# LEDSubMatrixHighDensity.net
KiCad netlist of a schematic drawn in EAGLE
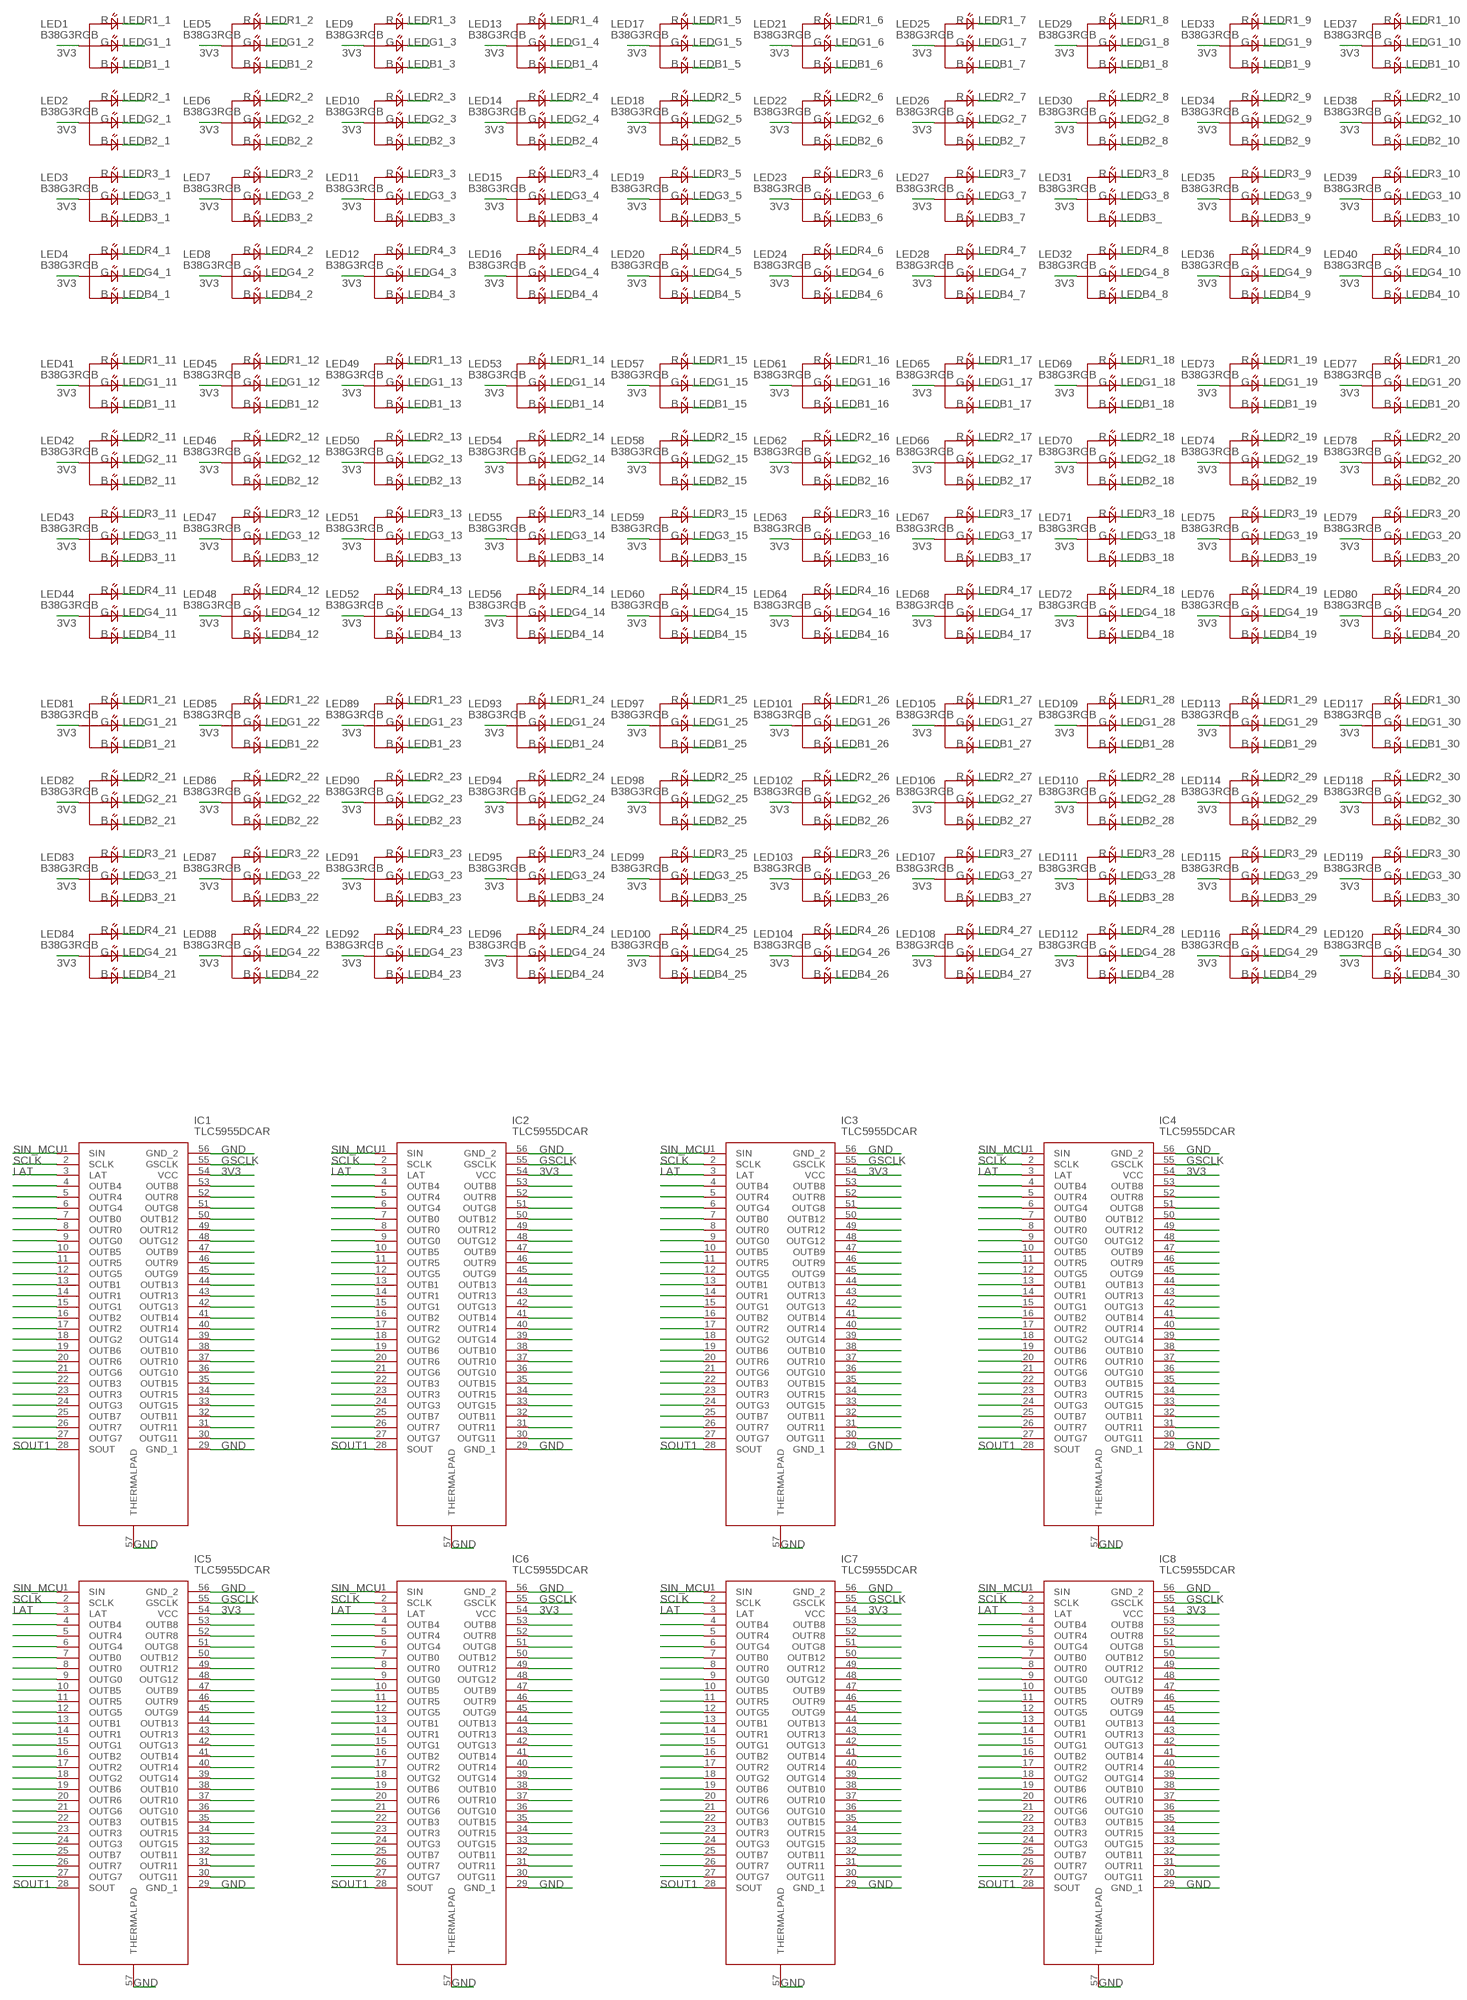
[diagram p0: schematic, sheet 1]

(export (version "E")
  (design (tool "Eeschema 10.0.6"))
  (components
    (comp (ref "IC1")
      (value "TLC5955DCAR")
      (footprint "eagle-import:SOP50P810X120-57N")
      (fields (field (name "MOUSER_PART_NUMBER") "595-TLC5955DCAR"))
      (libsource (lib "eagle-import") (part "TLC5955DCAR"))
    )
    (comp (ref "IC2")
      (value "TLC5955DCAR")
      (footprint "eagle-import:SOP50P810X120-57N")
      (fields (field (name "MOUSER_PART_NUMBER") "595-TLC5955DCAR"))
      (libsource (lib "eagle-import") (part "TLC5955DCAR"))
    )
    (comp (ref "IC3")
      (value "TLC5955DCAR")
      (footprint "eagle-import:SOP50P810X120-57N")
      (fields (field (name "MOUSER_PART_NUMBER") "595-TLC5955DCAR"))
      (libsource (lib "eagle-import") (part "TLC5955DCAR"))
    )
    (comp (ref "IC4")
      (value "TLC5955DCAR")
      (footprint "eagle-import:SOP50P810X120-57N")
      (fields (field (name "MOUSER_PART_NUMBER") "595-TLC5955DCAR"))
      (libsource (lib "eagle-import") (part "TLC5955DCAR"))
    )
    (comp (ref "IC5")
      (value "TLC5955DCAR")
      (footprint "eagle-import:SOP50P810X120-57N")
      (fields (field (name "MOUSER_PART_NUMBER") "595-TLC5955DCAR"))
      (libsource (lib "eagle-import") (part "TLC5955DCAR"))
    )
    (comp (ref "IC6")
      (value "TLC5955DCAR")
      (footprint "eagle-import:SOP50P810X120-57N")
      (fields (field (name "MOUSER_PART_NUMBER") "595-TLC5955DCAR"))
      (libsource (lib "eagle-import") (part "TLC5955DCAR"))
    )
    (comp (ref "IC7")
      (value "TLC5955DCAR")
      (footprint "eagle-import:SOP50P810X120-57N")
      (fields (field (name "MOUSER_PART_NUMBER") "595-TLC5955DCAR"))
      (libsource (lib "eagle-import") (part "TLC5955DCAR"))
    )
    (comp (ref "IC8")
      (value "TLC5955DCAR")
      (footprint "eagle-import:SOP50P810X120-57N")
      (fields (field (name "MOUSER_PART_NUMBER") "595-TLC5955DCAR"))
      (libsource (lib "eagle-import") (part "TLC5955DCAR"))
    )
    (comp (ref "LED1")
      (value "B38G3RGB")
      (footprint "eagle-import:B38G3RGB")
      (fields
        (field (name "ARROW_PART_NUMBER") "SML-LX0606IGC-TR")
        (field (name "MOUSER_PART_NUMBER") "696-SML-0606IGCTR")
      )
      (libsource (lib "eagle-import") (part "B38G3RGB"))
    )
    (comp (ref "LED2")
      (value "B38G3RGB")
      (footprint "eagle-import:B38G3RGB")
      (fields
        (field (name "ARROW_PART_NUMBER") "SML-LX0606IGC-TR")
        (field (name "MOUSER_PART_NUMBER") "696-SML-0606IGCTR")
      )
      (libsource (lib "eagle-import") (part "B38G3RGB"))
    )
    (comp (ref "LED3")
      (value "B38G3RGB")
      (footprint "eagle-import:B38G3RGB")
      (fields
        (field (name "ARROW_PART_NUMBER") "SML-LX0606IGC-TR")
        (field (name "MOUSER_PART_NUMBER") "696-SML-0606IGCTR")
      )
      (libsource (lib "eagle-import") (part "B38G3RGB"))
    )
    (comp (ref "LED4")
      (value "B38G3RGB")
      (footprint "eagle-import:B38G3RGB")
      (fields
        (field (name "ARROW_PART_NUMBER") "SML-LX0606IGC-TR")
        (field (name "MOUSER_PART_NUMBER") "696-SML-0606IGCTR")
      )
      (libsource (lib "eagle-import") (part "B38G3RGB"))
    )
    (comp (ref "LED5")
      (value "B38G3RGB")
      (footprint "eagle-import:B38G3RGB")
      (fields
        (field (name "ARROW_PART_NUMBER") "SML-LX0606IGC-TR")
        (field (name "MOUSER_PART_NUMBER") "696-SML-0606IGCTR")
      )
      (libsource (lib "eagle-import") (part "B38G3RGB"))
    )
    (comp (ref "LED6")
      (value "B38G3RGB")
      (footprint "eagle-import:B38G3RGB")
      (fields
        (field (name "ARROW_PART_NUMBER") "SML-LX0606IGC-TR")
        (field (name "MOUSER_PART_NUMBER") "696-SML-0606IGCTR")
      )
      (libsource (lib "eagle-import") (part "B38G3RGB"))
    )
    (comp (ref "LED7")
      (value "B38G3RGB")
      (footprint "eagle-import:B38G3RGB")
      (fields
        (field (name "ARROW_PART_NUMBER") "SML-LX0606IGC-TR")
        (field (name "MOUSER_PART_NUMBER") "696-SML-0606IGCTR")
      )
      (libsource (lib "eagle-import") (part "B38G3RGB"))
    )
    (comp (ref "LED8")
      (value "B38G3RGB")
      (footprint "eagle-import:B38G3RGB")
      (fields
        (field (name "ARROW_PART_NUMBER") "SML-LX0606IGC-TR")
        (field (name "MOUSER_PART_NUMBER") "696-SML-0606IGCTR")
      )
      (libsource (lib "eagle-import") (part "B38G3RGB"))
    )
    (comp (ref "LED9")
      (value "B38G3RGB")
      (footprint "eagle-import:B38G3RGB")
      (fields
        (field (name "ARROW_PART_NUMBER") "SML-LX0606IGC-TR")
        (field (name "MOUSER_PART_NUMBER") "696-SML-0606IGCTR")
      )
      (libsource (lib "eagle-import") (part "B38G3RGB"))
    )
    (comp (ref "LED10")
      (value "B38G3RGB")
      (footprint "eagle-import:B38G3RGB")
      (fields
        (field (name "ARROW_PART_NUMBER") "SML-LX0606IGC-TR")
        (field (name "MOUSER_PART_NUMBER") "696-SML-0606IGCTR")
      )
      (libsource (lib "eagle-import") (part "B38G3RGB"))
    )
    (comp (ref "LED11")
      (value "B38G3RGB")
      (footprint "eagle-import:B38G3RGB")
      (fields
        (field (name "ARROW_PART_NUMBER") "SML-LX0606IGC-TR")
        (field (name "MOUSER_PART_NUMBER") "696-SML-0606IGCTR")
      )
      (libsource (lib "eagle-import") (part "B38G3RGB"))
    )
    (comp (ref "LED12")
      (value "B38G3RGB")
      (footprint "eagle-import:B38G3RGB")
      (fields
        (field (name "ARROW_PART_NUMBER") "SML-LX0606IGC-TR")
        (field (name "MOUSER_PART_NUMBER") "696-SML-0606IGCTR")
      )
      (libsource (lib "eagle-import") (part "B38G3RGB"))
    )
    (comp (ref "LED13")
      (value "B38G3RGB")
      (footprint "eagle-import:B38G3RGB")
      (fields
        (field (name "ARROW_PART_NUMBER") "SML-LX0606IGC-TR")
        (field (name "MOUSER_PART_NUMBER") "696-SML-0606IGCTR")
      )
      (libsource (lib "eagle-import") (part "B38G3RGB"))
    )
    (comp (ref "LED14")
      (value "B38G3RGB")
      (footprint "eagle-import:B38G3RGB")
      (fields
        (field (name "ARROW_PART_NUMBER") "SML-LX0606IGC-TR")
        (field (name "MOUSER_PART_NUMBER") "696-SML-0606IGCTR")
      )
      (libsource (lib "eagle-import") (part "B38G3RGB"))
    )
    (comp (ref "LED15")
      (value "B38G3RGB")
      (footprint "eagle-import:B38G3RGB")
      (fields
        (field (name "ARROW_PART_NUMBER") "SML-LX0606IGC-TR")
        (field (name "MOUSER_PART_NUMBER") "696-SML-0606IGCTR")
      )
      (libsource (lib "eagle-import") (part "B38G3RGB"))
    )
    (comp (ref "LED16")
      (value "B38G3RGB")
      (footprint "eagle-import:B38G3RGB")
      (fields
        (field (name "ARROW_PART_NUMBER") "SML-LX0606IGC-TR")
        (field (name "MOUSER_PART_NUMBER") "696-SML-0606IGCTR")
      )
      (libsource (lib "eagle-import") (part "B38G3RGB"))
    )
    (comp (ref "LED17")
      (value "B38G3RGB")
      (footprint "eagle-import:B38G3RGB")
      (fields
        (field (name "ARROW_PART_NUMBER") "SML-LX0606IGC-TR")
        (field (name "MOUSER_PART_NUMBER") "696-SML-0606IGCTR")
      )
      (libsource (lib "eagle-import") (part "B38G3RGB"))
    )
    (comp (ref "LED18")
      (value "B38G3RGB")
      (footprint "eagle-import:B38G3RGB")
      (fields
        (field (name "ARROW_PART_NUMBER") "SML-LX0606IGC-TR")
        (field (name "MOUSER_PART_NUMBER") "696-SML-0606IGCTR")
      )
      (libsource (lib "eagle-import") (part "B38G3RGB"))
    )
    (comp (ref "LED19")
      (value "B38G3RGB")
      (footprint "eagle-import:B38G3RGB")
      (fields
        (field (name "ARROW_PART_NUMBER") "SML-LX0606IGC-TR")
        (field (name "MOUSER_PART_NUMBER") "696-SML-0606IGCTR")
      )
      (libsource (lib "eagle-import") (part "B38G3RGB"))
    )
    (comp (ref "LED20")
      (value "B38G3RGB")
      (footprint "eagle-import:B38G3RGB")
      (fields
        (field (name "ARROW_PART_NUMBER") "SML-LX0606IGC-TR")
        (field (name "MOUSER_PART_NUMBER") "696-SML-0606IGCTR")
      )
      (libsource (lib "eagle-import") (part "B38G3RGB"))
    )
    (comp (ref "LED21")
      (value "B38G3RGB")
      (footprint "eagle-import:B38G3RGB")
      (fields
        (field (name "ARROW_PART_NUMBER") "SML-LX0606IGC-TR")
        (field (name "MOUSER_PART_NUMBER") "696-SML-0606IGCTR")
      )
      (libsource (lib "eagle-import") (part "B38G3RGB"))
    )
    (comp (ref "LED22")
      (value "B38G3RGB")
      (footprint "eagle-import:B38G3RGB")
      (fields
        (field (name "ARROW_PART_NUMBER") "SML-LX0606IGC-TR")
        (field (name "MOUSER_PART_NUMBER") "696-SML-0606IGCTR")
      )
      (libsource (lib "eagle-import") (part "B38G3RGB"))
    )
    (comp (ref "LED23")
      (value "B38G3RGB")
      (footprint "eagle-import:B38G3RGB")
      (fields
        (field (name "ARROW_PART_NUMBER") "SML-LX0606IGC-TR")
        (field (name "MOUSER_PART_NUMBER") "696-SML-0606IGCTR")
      )
      (libsource (lib "eagle-import") (part "B38G3RGB"))
    )
    (comp (ref "LED24")
      (value "B38G3RGB")
      (footprint "eagle-import:B38G3RGB")
      (fields
        (field (name "ARROW_PART_NUMBER") "SML-LX0606IGC-TR")
        (field (name "MOUSER_PART_NUMBER") "696-SML-0606IGCTR")
      )
      (libsource (lib "eagle-import") (part "B38G3RGB"))
    )
    (comp (ref "LED25")
      (value "B38G3RGB")
      (footprint "eagle-import:B38G3RGB")
      (fields
        (field (name "ARROW_PART_NUMBER") "SML-LX0606IGC-TR")
        (field (name "MOUSER_PART_NUMBER") "696-SML-0606IGCTR")
      )
      (libsource (lib "eagle-import") (part "B38G3RGB"))
    )
    (comp (ref "LED26")
      (value "B38G3RGB")
      (footprint "eagle-import:B38G3RGB")
      (fields
        (field (name "ARROW_PART_NUMBER") "SML-LX0606IGC-TR")
        (field (name "MOUSER_PART_NUMBER") "696-SML-0606IGCTR")
      )
      (libsource (lib "eagle-import") (part "B38G3RGB"))
    )
    (comp (ref "LED27")
      (value "B38G3RGB")
      (footprint "eagle-import:B38G3RGB")
      (fields
        (field (name "ARROW_PART_NUMBER") "SML-LX0606IGC-TR")
        (field (name "MOUSER_PART_NUMBER") "696-SML-0606IGCTR")
      )
      (libsource (lib "eagle-import") (part "B38G3RGB"))
    )
    (comp (ref "LED28")
      (value "B38G3RGB")
      (footprint "eagle-import:B38G3RGB")
      (fields
        (field (name "ARROW_PART_NUMBER") "SML-LX0606IGC-TR")
        (field (name "MOUSER_PART_NUMBER") "696-SML-0606IGCTR")
      )
      (libsource (lib "eagle-import") (part "B38G3RGB"))
    )
    (comp (ref "LED29")
      (value "B38G3RGB")
      (footprint "eagle-import:B38G3RGB")
      (fields
        (field (name "ARROW_PART_NUMBER") "SML-LX0606IGC-TR")
        (field (name "MOUSER_PART_NUMBER") "696-SML-0606IGCTR")
      )
      (libsource (lib "eagle-import") (part "B38G3RGB"))
    )
    (comp (ref "LED30")
      (value "B38G3RGB")
      (footprint "eagle-import:B38G3RGB")
      (fields
        (field (name "ARROW_PART_NUMBER") "SML-LX0606IGC-TR")
        (field (name "MOUSER_PART_NUMBER") "696-SML-0606IGCTR")
      )
      (libsource (lib "eagle-import") (part "B38G3RGB"))
    )
    (comp (ref "LED31")
      (value "B38G3RGB")
      (footprint "eagle-import:B38G3RGB")
      (fields
        (field (name "ARROW_PART_NUMBER") "SML-LX0606IGC-TR")
        (field (name "MOUSER_PART_NUMBER") "696-SML-0606IGCTR")
      )
      (libsource (lib "eagle-import") (part "B38G3RGB"))
    )
    (comp (ref "LED32")
      (value "B38G3RGB")
      (footprint "eagle-import:B38G3RGB")
      (fields
        (field (name "ARROW_PART_NUMBER") "SML-LX0606IGC-TR")
        (field (name "MOUSER_PART_NUMBER") "696-SML-0606IGCTR")
      )
      (libsource (lib "eagle-import") (part "B38G3RGB"))
    )
    (comp (ref "LED33")
      (value "B38G3RGB")
      (footprint "eagle-import:B38G3RGB")
      (fields
        (field (name "ARROW_PART_NUMBER") "SML-LX0606IGC-TR")
        (field (name "MOUSER_PART_NUMBER") "696-SML-0606IGCTR")
      )
      (libsource (lib "eagle-import") (part "B38G3RGB"))
    )
    (comp (ref "LED34")
      (value "B38G3RGB")
      (footprint "eagle-import:B38G3RGB")
      (fields
        (field (name "ARROW_PART_NUMBER") "SML-LX0606IGC-TR")
        (field (name "MOUSER_PART_NUMBER") "696-SML-0606IGCTR")
      )
      (libsource (lib "eagle-import") (part "B38G3RGB"))
    )
    (comp (ref "LED35")
      (value "B38G3RGB")
      (footprint "eagle-import:B38G3RGB")
      (fields
        (field (name "ARROW_PART_NUMBER") "SML-LX0606IGC-TR")
        (field (name "MOUSER_PART_NUMBER") "696-SML-0606IGCTR")
      )
      (libsource (lib "eagle-import") (part "B38G3RGB"))
    )
    (comp (ref "LED36")
      (value "B38G3RGB")
      (footprint "eagle-import:B38G3RGB")
      (fields
        (field (name "ARROW_PART_NUMBER") "SML-LX0606IGC-TR")
        (field (name "MOUSER_PART_NUMBER") "696-SML-0606IGCTR")
      )
      (libsource (lib "eagle-import") (part "B38G3RGB"))
    )
    (comp (ref "LED37")
      (value "B38G3RGB")
      (footprint "eagle-import:B38G3RGB")
      (fields
        (field (name "ARROW_PART_NUMBER") "SML-LX0606IGC-TR")
        (field (name "MOUSER_PART_NUMBER") "696-SML-0606IGCTR")
      )
      (libsource (lib "eagle-import") (part "B38G3RGB"))
    )
    (comp (ref "LED38")
      (value "B38G3RGB")
      (footprint "eagle-import:B38G3RGB")
      (fields
        (field (name "ARROW_PART_NUMBER") "SML-LX0606IGC-TR")
        (field (name "MOUSER_PART_NUMBER") "696-SML-0606IGCTR")
      )
      (libsource (lib "eagle-import") (part "B38G3RGB"))
    )
    (comp (ref "LED39")
      (value "B38G3RGB")
      (footprint "eagle-import:B38G3RGB")
      (fields
        (field (name "ARROW_PART_NUMBER") "SML-LX0606IGC-TR")
        (field (name "MOUSER_PART_NUMBER") "696-SML-0606IGCTR")
      )
      (libsource (lib "eagle-import") (part "B38G3RGB"))
    )
    (comp (ref "LED40")
      (value "B38G3RGB")
      (footprint "eagle-import:B38G3RGB")
      (fields
        (field (name "ARROW_PART_NUMBER") "SML-LX0606IGC-TR")
        (field (name "MOUSER_PART_NUMBER") "696-SML-0606IGCTR")
      )
      (libsource (lib "eagle-import") (part "B38G3RGB"))
    )
    (comp (ref "LED41")
      (value "B38G3RGB")
      (footprint "eagle-import:B38G3RGB")
      (fields
        (field (name "ARROW_PART_NUMBER") "SML-LX0606IGC-TR")
        (field (name "MOUSER_PART_NUMBER") "696-SML-0606IGCTR")
      )
      (libsource (lib "eagle-import") (part "B38G3RGB"))
    )
    (comp (ref "LED42")
      (value "B38G3RGB")
      (footprint "eagle-import:B38G3RGB")
      (fields
        (field (name "ARROW_PART_NUMBER") "SML-LX0606IGC-TR")
        (field (name "MOUSER_PART_NUMBER") "696-SML-0606IGCTR")
      )
      (libsource (lib "eagle-import") (part "B38G3RGB"))
    )
    (comp (ref "LED43")
      (value "B38G3RGB")
      (footprint "eagle-import:B38G3RGB")
      (fields
        (field (name "ARROW_PART_NUMBER") "SML-LX0606IGC-TR")
        (field (name "MOUSER_PART_NUMBER") "696-SML-0606IGCTR")
      )
      (libsource (lib "eagle-import") (part "B38G3RGB"))
    )
    (comp (ref "LED44")
      (value "B38G3RGB")
      (footprint "eagle-import:B38G3RGB")
      (fields
        (field (name "ARROW_PART_NUMBER") "SML-LX0606IGC-TR")
        (field (name "MOUSER_PART_NUMBER") "696-SML-0606IGCTR")
      )
      (libsource (lib "eagle-import") (part "B38G3RGB"))
    )
    (comp (ref "LED45")
      (value "B38G3RGB")
      (footprint "eagle-import:B38G3RGB")
      (fields
        (field (name "ARROW_PART_NUMBER") "SML-LX0606IGC-TR")
        (field (name "MOUSER_PART_NUMBER") "696-SML-0606IGCTR")
      )
      (libsource (lib "eagle-import") (part "B38G3RGB"))
    )
    (comp (ref "LED46")
      (value "B38G3RGB")
      (footprint "eagle-import:B38G3RGB")
      (fields
        (field (name "ARROW_PART_NUMBER") "SML-LX0606IGC-TR")
        (field (name "MOUSER_PART_NUMBER") "696-SML-0606IGCTR")
      )
      (libsource (lib "eagle-import") (part "B38G3RGB"))
    )
    (comp (ref "LED47")
      (value "B38G3RGB")
      (footprint "eagle-import:B38G3RGB")
      (fields
        (field (name "ARROW_PART_NUMBER") "SML-LX0606IGC-TR")
        (field (name "MOUSER_PART_NUMBER") "696-SML-0606IGCTR")
      )
      (libsource (lib "eagle-import") (part "B38G3RGB"))
    )
    (comp (ref "LED48")
      (value "B38G3RGB")
      (footprint "eagle-import:B38G3RGB")
      (fields
        (field (name "ARROW_PART_NUMBER") "SML-LX0606IGC-TR")
        (field (name "MOUSER_PART_NUMBER") "696-SML-0606IGCTR")
      )
      (libsource (lib "eagle-import") (part "B38G3RGB"))
    )
    (comp (ref "LED49")
      (value "B38G3RGB")
      (footprint "eagle-import:B38G3RGB")
      (fields
        (field (name "ARROW_PART_NUMBER") "SML-LX0606IGC-TR")
        (field (name "MOUSER_PART_NUMBER") "696-SML-0606IGCTR")
      )
      (libsource (lib "eagle-import") (part "B38G3RGB"))
    )
    (comp (ref "LED50")
      (value "B38G3RGB")
      (footprint "eagle-import:B38G3RGB")
      (fields
        (field (name "ARROW_PART_NUMBER") "SML-LX0606IGC-TR")
        (field (name "MOUSER_PART_NUMBER") "696-SML-0606IGCTR")
      )
      (libsource (lib "eagle-import") (part "B38G3RGB"))
    )
    (comp (ref "LED51")
      (value "B38G3RGB")
      (footprint "eagle-import:B38G3RGB")
      (fields
        (field (name "ARROW_PART_NUMBER") "SML-LX0606IGC-TR")
        (field (name "MOUSER_PART_NUMBER") "696-SML-0606IGCTR")
      )
      (libsource (lib "eagle-import") (part "B38G3RGB"))
    )
    (comp (ref "LED52")
      (value "B38G3RGB")
      (footprint "eagle-import:B38G3RGB")
      (fields
        (field (name "ARROW_PART_NUMBER") "SML-LX0606IGC-TR")
        (field (name "MOUSER_PART_NUMBER") "696-SML-0606IGCTR")
      )
      (libsource (lib "eagle-import") (part "B38G3RGB"))
    )
    (comp (ref "LED53")
      (value "B38G3RGB")
      (footprint "eagle-import:B38G3RGB")
      (fields
        (field (name "ARROW_PART_NUMBER") "SML-LX0606IGC-TR")
        (field (name "MOUSER_PART_NUMBER") "696-SML-0606IGCTR")
      )
      (libsource (lib "eagle-import") (part "B38G3RGB"))
    )
    (comp (ref "LED54")
      (value "B38G3RGB")
      (footprint "eagle-import:B38G3RGB")
      (fields
        (field (name "ARROW_PART_NUMBER") "SML-LX0606IGC-TR")
        (field (name "MOUSER_PART_NUMBER") "696-SML-0606IGCTR")
      )
      (libsource (lib "eagle-import") (part "B38G3RGB"))
    )
    (comp (ref "LED55")
      (value "B38G3RGB")
      (footprint "eagle-import:B38G3RGB")
      (fields
        (field (name "ARROW_PART_NUMBER") "SML-LX0606IGC-TR")
        (field (name "MOUSER_PART_NUMBER") "696-SML-0606IGCTR")
      )
      (libsource (lib "eagle-import") (part "B38G3RGB"))
    )
    (comp (ref "LED56")
      (value "B38G3RGB")
      (footprint "eagle-import:B38G3RGB")
      (fields
        (field (name "ARROW_PART_NUMBER") "SML-LX0606IGC-TR")
        (field (name "MOUSER_PART_NUMBER") "696-SML-0606IGCTR")
      )
      (libsource (lib "eagle-import") (part "B38G3RGB"))
    )
    (comp (ref "LED57")
      (value "B38G3RGB")
      (footprint "eagle-import:B38G3RGB")
      (fields
        (field (name "ARROW_PART_NUMBER") "SML-LX0606IGC-TR")
        (field (name "MOUSER_PART_NUMBER") "696-SML-0606IGCTR")
      )
      (libsource (lib "eagle-import") (part "B38G3RGB"))
    )
    (comp (ref "LED58")
      (value "B38G3RGB")
      (footprint "eagle-import:B38G3RGB")
      (fields
        (field (name "ARROW_PART_NUMBER") "SML-LX0606IGC-TR")
        (field (name "MOUSER_PART_NUMBER") "696-SML-0606IGCTR")
      )
      (libsource (lib "eagle-import") (part "B38G3RGB"))
    )
    (comp (ref "LED59")
      (value "B38G3RGB")
      (footprint "eagle-import:B38G3RGB")
      (fields
        (field (name "ARROW_PART_NUMBER") "SML-LX0606IGC-TR")
        (field (name "MOUSER_PART_NUMBER") "696-SML-0606IGCTR")
      )
      (libsource (lib "eagle-import") (part "B38G3RGB"))
    )
    (comp (ref "LED60")
      (value "B38G3RGB")
      (footprint "eagle-import:B38G3RGB")
      (fields
        (field (name "ARROW_PART_NUMBER") "SML-LX0606IGC-TR")
        (field (name "MOUSER_PART_NUMBER") "696-SML-0606IGCTR")
      )
      (libsource (lib "eagle-import") (part "B38G3RGB"))
    )
    (comp (ref "LED61")
      (value "B38G3RGB")
      (footprint "eagle-import:B38G3RGB")
      (fields
        (field (name "ARROW_PART_NUMBER") "SML-LX0606IGC-TR")
        (field (name "MOUSER_PART_NUMBER") "696-SML-0606IGCTR")
      )
      (libsource (lib "eagle-import") (part "B38G3RGB"))
    )
    (comp (ref "LED62")
      (value "B38G3RGB")
      (footprint "eagle-import:B38G3RGB")
      (fields
        (field (name "ARROW_PART_NUMBER") "SML-LX0606IGC-TR")
        (field (name "MOUSER_PART_NUMBER") "696-SML-0606IGCTR")
      )
      (libsource (lib "eagle-import") (part "B38G3RGB"))
    )
    (comp (ref "LED63")
      (value "B38G3RGB")
      (footprint "eagle-import:B38G3RGB")
      (fields
        (field (name "ARROW_PART_NUMBER") "SML-LX0606IGC-TR")
        (field (name "MOUSER_PART_NUMBER") "696-SML-0606IGCTR")
      )
      (libsource (lib "eagle-import") (part "B38G3RGB"))
    )
    (comp (ref "LED64")
      (value "B38G3RGB")
      (footprint "eagle-import:B38G3RGB")
      (fields
        (field (name "ARROW_PART_NUMBER") "SML-LX0606IGC-TR")
        (field (name "MOUSER_PART_NUMBER") "696-SML-0606IGCTR")
      )
      (libsource (lib "eagle-import") (part "B38G3RGB"))
    )
    (comp (ref "LED65")
      (value "B38G3RGB")
      (footprint "eagle-import:B38G3RGB")
      (fields
        (field (name "ARROW_PART_NUMBER") "SML-LX0606IGC-TR")
        (field (name "MOUSER_PART_NUMBER") "696-SML-0606IGCTR")
      )
      (libsource (lib "eagle-import") (part "B38G3RGB"))
    )
    (comp (ref "LED66")
      (value "B38G3RGB")
      (footprint "eagle-import:B38G3RGB")
      (fields
        (field (name "ARROW_PART_NUMBER") "SML-LX0606IGC-TR")
        (field (name "MOUSER_PART_NUMBER") "696-SML-0606IGCTR")
      )
      (libsource (lib "eagle-import") (part "B38G3RGB"))
    )
    (comp (ref "LED67")
      (value "B38G3RGB")
      (footprint "eagle-import:B38G3RGB")
      (fields
        (field (name "ARROW_PART_NUMBER") "SML-LX0606IGC-TR")
        (field (name "MOUSER_PART_NUMBER") "696-SML-0606IGCTR")
      )
      (libsource (lib "eagle-import") (part "B38G3RGB"))
    )
    (comp (ref "LED68")
      (value "B38G3RGB")
      (footprint "eagle-import:B38G3RGB")
      (fields
        (field (name "ARROW_PART_NUMBER") "SML-LX0606IGC-TR")
        (field (name "MOUSER_PART_NUMBER") "696-SML-0606IGCTR")
      )
      (libsource (lib "eagle-import") (part "B38G3RGB"))
    )
    (comp (ref "LED69")
      (value "B38G3RGB")
      (footprint "eagle-import:B38G3RGB")
      (fields
        (field (name "ARROW_PART_NUMBER") "SML-LX0606IGC-TR")
        (field (name "MOUSER_PART_NUMBER") "696-SML-0606IGCTR")
      )
      (libsource (lib "eagle-import") (part "B38G3RGB"))
    )
    (comp (ref "LED70")
      (value "B38G3RGB")
      (footprint "eagle-import:B38G3RGB")
      (fields
        (field (name "ARROW_PART_NUMBER") "SML-LX0606IGC-TR")
        (field (name "MOUSER_PART_NUMBER") "696-SML-0606IGCTR")
      )
      (libsource (lib "eagle-import") (part "B38G3RGB"))
    )
    (comp (ref "LED71")
      (value "B38G3RGB")
      (footprint "eagle-import:B38G3RGB")
      (fields
        (field (name "ARROW_PART_NUMBER") "SML-LX0606IGC-TR")
        (field (name "MOUSER_PART_NUMBER") "696-SML-0606IGCTR")
      )
      (libsource (lib "eagle-import") (part "B38G3RGB"))
    )
    (comp (ref "LED72")
      (value "B38G3RGB")
      (footprint "eagle-import:B38G3RGB")
      (fields
        (field (name "ARROW_PART_NUMBER") "SML-LX0606IGC-TR")
        (field (name "MOUSER_PART_NUMBER") "696-SML-0606IGCTR")
      )
      (libsource (lib "eagle-import") (part "B38G3RGB"))
    )
    (comp (ref "LED73")
      (value "B38G3RGB")
      (footprint "eagle-import:B38G3RGB")
      (fields
        (field (name "ARROW_PART_NUMBER") "SML-LX0606IGC-TR")
        (field (name "MOUSER_PART_NUMBER") "696-SML-0606IGCTR")
      )
      (libsource (lib "eagle-import") (part "B38G3RGB"))
    )
    (comp (ref "LED74")
      (value "B38G3RGB")
      (footprint "eagle-import:B38G3RGB")
      (fields
        (field (name "ARROW_PART_NUMBER") "SML-LX0606IGC-TR")
        (field (name "MOUSER_PART_NUMBER") "696-SML-0606IGCTR")
      )
      (libsource (lib "eagle-import") (part "B38G3RGB"))
    )
    (comp (ref "LED75")
      (value "B38G3RGB")
      (footprint "eagle-import:B38G3RGB")
      (fields
        (field (name "ARROW_PART_NUMBER") "SML-LX0606IGC-TR")
        (field (name "MOUSER_PART_NUMBER") "696-SML-0606IGCTR")
      )
      (libsource (lib "eagle-import") (part "B38G3RGB"))
    )
    (comp (ref "LED76")
      (value "B38G3RGB")
      (footprint "eagle-import:B38G3RGB")
      (fields
        (field (name "ARROW_PART_NUMBER") "SML-LX0606IGC-TR")
        (field (name "MOUSER_PART_NUMBER") "696-SML-0606IGCTR")
      )
      (libsource (lib "eagle-import") (part "B38G3RGB"))
    )
    (comp (ref "LED77")
      (value "B38G3RGB")
      (footprint "eagle-import:B38G3RGB")
      (fields
        (field (name "ARROW_PART_NUMBER") "SML-LX0606IGC-TR")
        (field (name "MOUSER_PART_NUMBER") "696-SML-0606IGCTR")
      )
      (libsource (lib "eagle-import") (part "B38G3RGB"))
    )
    (comp (ref "LED78")
      (value "B38G3RGB")
      (footprint "eagle-import:B38G3RGB")
      (fields
        (field (name "ARROW_PART_NUMBER") "SML-LX0606IGC-TR")
        (field (name "MOUSER_PART_NUMBER") "696-SML-0606IGCTR")
      )
      (libsource (lib "eagle-import") (part "B38G3RGB"))
    )
    (comp (ref "LED79")
      (value "B38G3RGB")
      (footprint "eagle-import:B38G3RGB")
      (fields
        (field (name "ARROW_PART_NUMBER") "SML-LX0606IGC-TR")
        (field (name "MOUSER_PART_NUMBER") "696-SML-0606IGCTR")
      )
      (libsource (lib "eagle-import") (part "B38G3RGB"))
    )
    (comp (ref "LED80")
      (value "B38G3RGB")
      (footprint "eagle-import:B38G3RGB")
      (fields
        (field (name "ARROW_PART_NUMBER") "SML-LX0606IGC-TR")
        (field (name "MOUSER_PART_NUMBER") "696-SML-0606IGCTR")
      )
      (libsource (lib "eagle-import") (part "B38G3RGB"))
    )
    (comp (ref "LED81")
      (value "B38G3RGB")
      (footprint "eagle-import:B38G3RGB")
      (fields
        (field (name "ARROW_PART_NUMBER") "SML-LX0606IGC-TR")
        (field (name "MOUSER_PART_NUMBER") "696-SML-0606IGCTR")
      )
      (libsource (lib "eagle-import") (part "B38G3RGB"))
    )
    (comp (ref "LED82")
      (value "B38G3RGB")
      (footprint "eagle-import:B38G3RGB")
      (fields
        (field (name "ARROW_PART_NUMBER") "SML-LX0606IGC-TR")
        (field (name "MOUSER_PART_NUMBER") "696-SML-0606IGCTR")
      )
      (libsource (lib "eagle-import") (part "B38G3RGB"))
    )
    (comp (ref "LED83")
      (value "B38G3RGB")
      (footprint "eagle-import:B38G3RGB")
      (fields
        (field (name "ARROW_PART_NUMBER") "SML-LX0606IGC-TR")
        (field (name "MOUSER_PART_NUMBER") "696-SML-0606IGCTR")
      )
      (libsource (lib "eagle-import") (part "B38G3RGB"))
    )
    (comp (ref "LED84")
      (value "B38G3RGB")
      (footprint "eagle-import:B38G3RGB")
      (fields
        (field (name "ARROW_PART_NUMBER") "SML-LX0606IGC-TR")
        (field (name "MOUSER_PART_NUMBER") "696-SML-0606IGCTR")
      )
      (libsource (lib "eagle-import") (part "B38G3RGB"))
    )
    (comp (ref "LED85")
      (value "B38G3RGB")
      (footprint "eagle-import:B38G3RGB")
      (fields
        (field (name "ARROW_PART_NUMBER") "SML-LX0606IGC-TR")
        (field (name "MOUSER_PART_NUMBER") "696-SML-0606IGCTR")
      )
      (libsource (lib "eagle-import") (part "B38G3RGB"))
    )
    (comp (ref "LED86")
      (value "B38G3RGB")
      (footprint "eagle-import:B38G3RGB")
      (fields
        (field (name "ARROW_PART_NUMBER") "SML-LX0606IGC-TR")
        (field (name "MOUSER_PART_NUMBER") "696-SML-0606IGCTR")
      )
      (libsource (lib "eagle-import") (part "B38G3RGB"))
    )
    (comp (ref "LED87")
      (value "B38G3RGB")
      (footprint "eagle-import:B38G3RGB")
      (fields
        (field (name "ARROW_PART_NUMBER") "SML-LX0606IGC-TR")
        (field (name "MOUSER_PART_NUMBER") "696-SML-0606IGCTR")
      )
      (libsource (lib "eagle-import") (part "B38G3RGB"))
    )
    (comp (ref "LED88")
      (value "B38G3RGB")
      (footprint "eagle-import:B38G3RGB")
      (fields
        (field (name "ARROW_PART_NUMBER") "SML-LX0606IGC-TR")
        (field (name "MOUSER_PART_NUMBER") "696-SML-0606IGCTR")
      )
      (libsource (lib "eagle-import") (part "B38G3RGB"))
    )
    (comp (ref "LED89")
      (value "B38G3RGB")
      (footprint "eagle-import:B38G3RGB")
      (fields
        (field (name "ARROW_PART_NUMBER") "SML-LX0606IGC-TR")
        (field (name "MOUSER_PART_NUMBER") "696-SML-0606IGCTR")
      )
      (libsource (lib "eagle-import") (part "B38G3RGB"))
    )
    (comp (ref "LED90")
      (value "B38G3RGB")
      (footprint "eagle-import:B38G3RGB")
      (fields
        (field (name "ARROW_PART_NUMBER") "SML-LX0606IGC-TR")
        (field (name "MOUSER_PART_NUMBER") "696-SML-0606IGCTR")
      )
      (libsource (lib "eagle-import") (part "B38G3RGB"))
    )
    (comp (ref "LED91")
      (value "B38G3RGB")
      (footprint "eagle-import:B38G3RGB")
      (fields
        (field (name "ARROW_PART_NUMBER") "SML-LX0606IGC-TR")
        (field (name "MOUSER_PART_NUMBER") "696-SML-0606IGCTR")
      )
      (libsource (lib "eagle-import") (part "B38G3RGB"))
    )
    (comp (ref "LED92")
      (value "B38G3RGB")
      (footprint "eagle-import:B38G3RGB")
      (fields
        (field (name "ARROW_PART_NUMBER") "SML-LX0606IGC-TR")
        (field (name "MOUSER_PART_NUMBER") "696-SML-0606IGCTR")
      )
      (libsource (lib "eagle-import") (part "B38G3RGB"))
    )
    (comp (ref "LED93")
      (value "B38G3RGB")
      (footprint "eagle-import:B38G3RGB")
      (fields
        (field (name "ARROW_PART_NUMBER") "SML-LX0606IGC-TR")
        (field (name "MOUSER_PART_NUMBER") "696-SML-0606IGCTR")
      )
      (libsource (lib "eagle-import") (part "B38G3RGB"))
    )
    (comp (ref "LED94")
      (value "B38G3RGB")
      (footprint "eagle-import:B38G3RGB")
      (fields
        (field (name "ARROW_PART_NUMBER") "SML-LX0606IGC-TR")
        (field (name "MOUSER_PART_NUMBER") "696-SML-0606IGCTR")
      )
      (libsource (lib "eagle-import") (part "B38G3RGB"))
    )
    (comp (ref "LED95")
      (value "B38G3RGB")
      (footprint "eagle-import:B38G3RGB")
      (fields
        (field (name "ARROW_PART_NUMBER") "SML-LX0606IGC-TR")
        (field (name "MOUSER_PART_NUMBER") "696-SML-0606IGCTR")
      )
      (libsource (lib "eagle-import") (part "B38G3RGB"))
    )
    (comp (ref "LED96")
      (value "B38G3RGB")
      (footprint "eagle-import:B38G3RGB")
      (fields
        (field (name "ARROW_PART_NUMBER") "SML-LX0606IGC-TR")
        (field (name "MOUSER_PART_NUMBER") "696-SML-0606IGCTR")
      )
      (libsource (lib "eagle-import") (part "B38G3RGB"))
    )
    (comp (ref "LED97")
      (value "B38G3RGB")
      (footprint "eagle-import:B38G3RGB")
      (fields
        (field (name "ARROW_PART_NUMBER") "SML-LX0606IGC-TR")
        (field (name "MOUSER_PART_NUMBER") "696-SML-0606IGCTR")
      )
      (libsource (lib "eagle-import") (part "B38G3RGB"))
    )
    (comp (ref "LED98")
      (value "B38G3RGB")
      (footprint "eagle-import:B38G3RGB")
      (fields
        (field (name "ARROW_PART_NUMBER") "SML-LX0606IGC-TR")
        (field (name "MOUSER_PART_NUMBER") "696-SML-0606IGCTR")
      )
      (libsource (lib "eagle-import") (part "B38G3RGB"))
    )
    (comp (ref "LED99")
      (value "B38G3RGB")
      (footprint "eagle-import:B38G3RGB")
      (fields
        (field (name "ARROW_PART_NUMBER") "SML-LX0606IGC-TR")
        (field (name "MOUSER_PART_NUMBER") "696-SML-0606IGCTR")
      )
      (libsource (lib "eagle-import") (part "B38G3RGB"))
    )
    (comp (ref "LED100")
      (value "B38G3RGB")
      (footprint "eagle-import:B38G3RGB")
      (fields
        (field (name "ARROW_PART_NUMBER") "SML-LX0606IGC-TR")
        (field (name "MOUSER_PART_NUMBER") "696-SML-0606IGCTR")
      )
      (libsource (lib "eagle-import") (part "B38G3RGB"))
    )
    (comp (ref "LED101")
      (value "B38G3RGB")
      (footprint "eagle-import:B38G3RGB")
      (fields
        (field (name "ARROW_PART_NUMBER") "SML-LX0606IGC-TR")
        (field (name "MOUSER_PART_NUMBER") "696-SML-0606IGCTR")
      )
      (libsource (lib "eagle-import") (part "B38G3RGB"))
    )
    (comp (ref "LED102")
      (value "B38G3RGB")
      (footprint "eagle-import:B38G3RGB")
      (fields
        (field (name "ARROW_PART_NUMBER") "SML-LX0606IGC-TR")
        (field (name "MOUSER_PART_NUMBER") "696-SML-0606IGCTR")
      )
      (libsource (lib "eagle-import") (part "B38G3RGB"))
    )
    (comp (ref "LED103")
      (value "B38G3RGB")
      (footprint "eagle-import:B38G3RGB")
      (fields
        (field (name "ARROW_PART_NUMBER") "SML-LX0606IGC-TR")
        (field (name "MOUSER_PART_NUMBER") "696-SML-0606IGCTR")
      )
      (libsource (lib "eagle-import") (part "B38G3RGB"))
    )
    (comp (ref "LED104")
      (value "B38G3RGB")
      (footprint "eagle-import:B38G3RGB")
      (fields
        (field (name "ARROW_PART_NUMBER") "SML-LX0606IGC-TR")
        (field (name "MOUSER_PART_NUMBER") "696-SML-0606IGCTR")
      )
      (libsource (lib "eagle-import") (part "B38G3RGB"))
    )
    (comp (ref "LED105")
      (value "B38G3RGB")
      (footprint "eagle-import:B38G3RGB")
      (fields
        (field (name "ARROW_PART_NUMBER") "SML-LX0606IGC-TR")
        (field (name "MOUSER_PART_NUMBER") "696-SML-0606IGCTR")
      )
      (libsource (lib "eagle-import") (part "B38G3RGB"))
    )
    (comp (ref "LED106")
      (value "B38G3RGB")
      (footprint "eagle-import:B38G3RGB")
      (fields
        (field (name "ARROW_PART_NUMBER") "SML-LX0606IGC-TR")
        (field (name "MOUSER_PART_NUMBER") "696-SML-0606IGCTR")
      )
      (libsource (lib "eagle-import") (part "B38G3RGB"))
    )
    (comp (ref "LED107")
      (value "B38G3RGB")
      (footprint "eagle-import:B38G3RGB")
      (fields
        (field (name "ARROW_PART_NUMBER") "SML-LX0606IGC-TR")
        (field (name "MOUSER_PART_NUMBER") "696-SML-0606IGCTR")
      )
      (libsource (lib "eagle-import") (part "B38G3RGB"))
    )
    (comp (ref "LED108")
      (value "B38G3RGB")
      (footprint "eagle-import:B38G3RGB")
      (fields
        (field (name "ARROW_PART_NUMBER") "SML-LX0606IGC-TR")
        (field (name "MOUSER_PART_NUMBER") "696-SML-0606IGCTR")
      )
      (libsource (lib "eagle-import") (part "B38G3RGB"))
    )
    (comp (ref "LED109")
      (value "B38G3RGB")
      (footprint "eagle-import:B38G3RGB")
      (fields
        (field (name "ARROW_PART_NUMBER") "SML-LX0606IGC-TR")
        (field (name "MOUSER_PART_NUMBER") "696-SML-0606IGCTR")
      )
      (libsource (lib "eagle-import") (part "B38G3RGB"))
    )
    (comp (ref "LED110")
      (value "B38G3RGB")
      (footprint "eagle-import:B38G3RGB")
      (fields
        (field (name "ARROW_PART_NUMBER") "SML-LX0606IGC-TR")
        (field (name "MOUSER_PART_NUMBER") "696-SML-0606IGCTR")
      )
      (libsource (lib "eagle-import") (part "B38G3RGB"))
    )
    (comp (ref "LED111")
      (value "B38G3RGB")
      (footprint "eagle-import:B38G3RGB")
      (fields
        (field (name "ARROW_PART_NUMBER") "SML-LX0606IGC-TR")
        (field (name "MOUSER_PART_NUMBER") "696-SML-0606IGCTR")
      )
      (libsource (lib "eagle-import") (part "B38G3RGB"))
    )
    (comp (ref "LED112")
      (value "B38G3RGB")
      (footprint "eagle-import:B38G3RGB")
      (fields
        (field (name "ARROW_PART_NUMBER") "SML-LX0606IGC-TR")
        (field (name "MOUSER_PART_NUMBER") "696-SML-0606IGCTR")
      )
      (libsource (lib "eagle-import") (part "B38G3RGB"))
    )
    (comp (ref "LED113")
      (value "B38G3RGB")
      (footprint "eagle-import:B38G3RGB")
      (fields
        (field (name "ARROW_PART_NUMBER") "SML-LX0606IGC-TR")
        (field (name "MOUSER_PART_NUMBER") "696-SML-0606IGCTR")
      )
      (libsource (lib "eagle-import") (part "B38G3RGB"))
    )
    (comp (ref "LED114")
      (value "B38G3RGB")
      (footprint "eagle-import:B38G3RGB")
      (fields
        (field (name "ARROW_PART_NUMBER") "SML-LX0606IGC-TR")
        (field (name "MOUSER_PART_NUMBER") "696-SML-0606IGCTR")
      )
      (libsource (lib "eagle-import") (part "B38G3RGB"))
    )
    (comp (ref "LED115")
      (value "B38G3RGB")
      (footprint "eagle-import:B38G3RGB")
      (fields
        (field (name "ARROW_PART_NUMBER") "SML-LX0606IGC-TR")
        (field (name "MOUSER_PART_NUMBER") "696-SML-0606IGCTR")
      )
      (libsource (lib "eagle-import") (part "B38G3RGB"))
    )
    (comp (ref "LED116")
      (value "B38G3RGB")
      (footprint "eagle-import:B38G3RGB")
      (fields
        (field (name "ARROW_PART_NUMBER") "SML-LX0606IGC-TR")
        (field (name "MOUSER_PART_NUMBER") "696-SML-0606IGCTR")
      )
      (libsource (lib "eagle-import") (part "B38G3RGB"))
    )
    (comp (ref "LED117")
      (value "B38G3RGB")
      (footprint "eagle-import:B38G3RGB")
      (fields
        (field (name "ARROW_PART_NUMBER") "SML-LX0606IGC-TR")
        (field (name "MOUSER_PART_NUMBER") "696-SML-0606IGCTR")
      )
      (libsource (lib "eagle-import") (part "B38G3RGB"))
    )
    (comp (ref "LED118")
      (value "B38G3RGB")
      (footprint "eagle-import:B38G3RGB")
      (fields
        (field (name "ARROW_PART_NUMBER") "SML-LX0606IGC-TR")
        (field (name "MOUSER_PART_NUMBER") "696-SML-0606IGCTR")
      )
      (libsource (lib "eagle-import") (part "B38G3RGB"))
    )
    (comp (ref "LED119")
      (value "B38G3RGB")
      (footprint "eagle-import:B38G3RGB")
      (fields
        (field (name "ARROW_PART_NUMBER") "SML-LX0606IGC-TR")
        (field (name "MOUSER_PART_NUMBER") "696-SML-0606IGCTR")
      )
      (libsource (lib "eagle-import") (part "B38G3RGB"))
    )
    (comp (ref "LED120")
      (value "B38G3RGB")
      (footprint "eagle-import:B38G3RGB")
      (fields
        (field (name "ARROW_PART_NUMBER") "SML-LX0606IGC-TR")
        (field (name "MOUSER_PART_NUMBER") "696-SML-0606IGCTR")
      )
      (libsource (lib "eagle-import") (part "B38G3RGB"))
    )
  )
  (nets
    (net (code "1") (name "/3V3") (class "Default")
      (node (ref "IC1") (pin "54") (pinfunction "VCC_54") (pintype "bidirectional"))
      (node (ref "IC2") (pin "54") (pinfunction "VCC_54") (pintype "bidirectional"))
      (node (ref "IC3") (pin "54") (pinfunction "VCC_54") (pintype "bidirectional"))
      (node (ref "IC4") (pin "54") (pinfunction "VCC_54") (pintype "bidirectional"))
      (node (ref "IC5") (pin "54") (pinfunction "VCC_54") (pintype "bidirectional"))
      (node (ref "IC6") (pin "54") (pinfunction "VCC_54") (pintype "bidirectional"))
      (node (ref "IC7") (pin "54") (pinfunction "VCC_54") (pintype "bidirectional"))
      (node (ref "IC8") (pin "54") (pinfunction "VCC_54") (pintype "bidirectional"))
      (node (ref "LED1") (pin "3") (pinfunction "COM_3") (pintype "bidirectional"))
      (node (ref "LED10") (pin "3") (pinfunction "COM_3") (pintype "bidirectional"))
      (node (ref "LED100") (pin "3") (pinfunction "COM_3") (pintype "bidirectional"))
      (node (ref "LED101") (pin "3") (pinfunction "COM_3") (pintype "bidirectional"))
      (node (ref "LED102") (pin "3") (pinfunction "COM_3") (pintype "bidirectional"))
      (node (ref "LED103") (pin "3") (pinfunction "COM_3") (pintype "bidirectional"))
      (node (ref "LED104") (pin "3") (pinfunction "COM_3") (pintype "bidirectional"))
      (node (ref "LED105") (pin "3") (pinfunction "COM_3") (pintype "bidirectional"))
      (node (ref "LED106") (pin "3") (pinfunction "COM_3") (pintype "bidirectional"))
      (node (ref "LED107") (pin "3") (pinfunction "COM_3") (pintype "bidirectional"))
      (node (ref "LED108") (pin "3") (pinfunction "COM_3") (pintype "bidirectional"))
      (node (ref "LED109") (pin "3") (pinfunction "COM_3") (pintype "bidirectional"))
      (node (ref "LED11") (pin "3") (pinfunction "COM_3") (pintype "bidirectional"))
      (node (ref "LED110") (pin "3") (pinfunction "COM_3") (pintype "bidirectional"))
      (node (ref "LED111") (pin "3") (pinfunction "COM_3") (pintype "bidirectional"))
      (node (ref "LED112") (pin "3") (pinfunction "COM_3") (pintype "bidirectional"))
      (node (ref "LED113") (pin "3") (pinfunction "COM_3") (pintype "bidirectional"))
      (node (ref "LED114") (pin "3") (pinfunction "COM_3") (pintype "bidirectional"))
      (node (ref "LED115") (pin "3") (pinfunction "COM_3") (pintype "bidirectional"))
      (node (ref "LED116") (pin "3") (pinfunction "COM_3") (pintype "bidirectional"))
      (node (ref "LED117") (pin "3") (pinfunction "COM_3") (pintype "bidirectional"))
      (node (ref "LED118") (pin "3") (pinfunction "COM_3") (pintype "bidirectional"))
      (node (ref "LED119") (pin "3") (pinfunction "COM_3") (pintype "bidirectional"))
      (node (ref "LED12") (pin "3") (pinfunction "COM_3") (pintype "bidirectional"))
      (node (ref "LED120") (pin "3") (pinfunction "COM_3") (pintype "bidirectional"))
      (node (ref "LED13") (pin "3") (pinfunction "COM_3") (pintype "bidirectional"))
      (node (ref "LED14") (pin "3") (pinfunction "COM_3") (pintype "bidirectional"))
      (node (ref "LED15") (pin "3") (pinfunction "COM_3") (pintype "bidirectional"))
      (node (ref "LED16") (pin "3") (pinfunction "COM_3") (pintype "bidirectional"))
      (node (ref "LED17") (pin "3") (pinfunction "COM_3") (pintype "bidirectional"))
      (node (ref "LED18") (pin "3") (pinfunction "COM_3") (pintype "bidirectional"))
      (node (ref "LED19") (pin "3") (pinfunction "COM_3") (pintype "bidirectional"))
      (node (ref "LED2") (pin "3") (pinfunction "COM_3") (pintype "bidirectional"))
      (node (ref "LED20") (pin "3") (pinfunction "COM_3") (pintype "bidirectional"))
      (node (ref "LED21") (pin "3") (pinfunction "COM_3") (pintype "bidirectional"))
      (node (ref "LED22") (pin "3") (pinfunction "COM_3") (pintype "bidirectional"))
      (node (ref "LED23") (pin "3") (pinfunction "COM_3") (pintype "bidirectional"))
      (node (ref "LED24") (pin "3") (pinfunction "COM_3") (pintype "bidirectional"))
      (node (ref "LED25") (pin "3") (pinfunction "COM_3") (pintype "bidirectional"))
      (node (ref "LED26") (pin "3") (pinfunction "COM_3") (pintype "bidirectional"))
      (node (ref "LED27") (pin "3") (pinfunction "COM_3") (pintype "bidirectional"))
      (node (ref "LED28") (pin "3") (pinfunction "COM_3") (pintype "bidirectional"))
      (node (ref "LED29") (pin "3") (pinfunction "COM_3") (pintype "bidirectional"))
      (node (ref "LED3") (pin "3") (pinfunction "COM_3") (pintype "bidirectional"))
      (node (ref "LED30") (pin "3") (pinfunction "COM_3") (pintype "bidirectional"))
      (node (ref "LED31") (pin "3") (pinfunction "COM_3") (pintype "bidirectional"))
      (node (ref "LED32") (pin "3") (pinfunction "COM_3") (pintype "bidirectional"))
      (node (ref "LED33") (pin "3") (pinfunction "COM_3") (pintype "bidirectional"))
      (node (ref "LED34") (pin "3") (pinfunction "COM_3") (pintype "bidirectional"))
      (node (ref "LED35") (pin "3") (pinfunction "COM_3") (pintype "bidirectional"))
      (node (ref "LED36") (pin "3") (pinfunction "COM_3") (pintype "bidirectional"))
      (node (ref "LED37") (pin "3") (pinfunction "COM_3") (pintype "bidirectional"))
      (node (ref "LED38") (pin "3") (pinfunction "COM_3") (pintype "bidirectional"))
      (node (ref "LED39") (pin "3") (pinfunction "COM_3") (pintype "bidirectional"))
      (node (ref "LED4") (pin "3") (pinfunction "COM_3") (pintype "bidirectional"))
      (node (ref "LED40") (pin "3") (pinfunction "COM_3") (pintype "bidirectional"))
      (node (ref "LED41") (pin "3") (pinfunction "COM_3") (pintype "bidirectional"))
      (node (ref "LED42") (pin "3") (pinfunction "COM_3") (pintype "bidirectional"))
      (node (ref "LED43") (pin "3") (pinfunction "COM_3") (pintype "bidirectional"))
      (node (ref "LED44") (pin "3") (pinfunction "COM_3") (pintype "bidirectional"))
      (node (ref "LED45") (pin "3") (pinfunction "COM_3") (pintype "bidirectional"))
      (node (ref "LED46") (pin "3") (pinfunction "COM_3") (pintype "bidirectional"))
      (node (ref "LED47") (pin "3") (pinfunction "COM_3") (pintype "bidirectional"))
      (node (ref "LED48") (pin "3") (pinfunction "COM_3") (pintype "bidirectional"))
      (node (ref "LED49") (pin "3") (pinfunction "COM_3") (pintype "bidirectional"))
      (node (ref "LED5") (pin "3") (pinfunction "COM_3") (pintype "bidirectional"))
      (node (ref "LED50") (pin "3") (pinfunction "COM_3") (pintype "bidirectional"))
      (node (ref "LED51") (pin "3") (pinfunction "COM_3") (pintype "bidirectional"))
      (node (ref "LED52") (pin "3") (pinfunction "COM_3") (pintype "bidirectional"))
      (node (ref "LED53") (pin "3") (pinfunction "COM_3") (pintype "bidirectional"))
      (node (ref "LED54") (pin "3") (pinfunction "COM_3") (pintype "bidirectional"))
      (node (ref "LED55") (pin "3") (pinfunction "COM_3") (pintype "bidirectional"))
      (node (ref "LED56") (pin "3") (pinfunction "COM_3") (pintype "bidirectional"))
      (node (ref "LED57") (pin "3") (pinfunction "COM_3") (pintype "bidirectional"))
      (node (ref "LED58") (pin "3") (pinfunction "COM_3") (pintype "bidirectional"))
      (node (ref "LED59") (pin "3") (pinfunction "COM_3") (pintype "bidirectional"))
      (node (ref "LED6") (pin "3") (pinfunction "COM_3") (pintype "bidirectional"))
      (node (ref "LED60") (pin "3") (pinfunction "COM_3") (pintype "bidirectional"))
      (node (ref "LED61") (pin "3") (pinfunction "COM_3") (pintype "bidirectional"))
      (node (ref "LED62") (pin "3") (pinfunction "COM_3") (pintype "bidirectional"))
      (node (ref "LED63") (pin "3") (pinfunction "COM_3") (pintype "bidirectional"))
      (node (ref "LED64") (pin "3") (pinfunction "COM_3") (pintype "bidirectional"))
      (node (ref "LED65") (pin "3") (pinfunction "COM_3") (pintype "bidirectional"))
      (node (ref "LED66") (pin "3") (pinfunction "COM_3") (pintype "bidirectional"))
      (node (ref "LED67") (pin "3") (pinfunction "COM_3") (pintype "bidirectional"))
      (node (ref "LED68") (pin "3") (pinfunction "COM_3") (pintype "bidirectional"))
      (node (ref "LED69") (pin "3") (pinfunction "COM_3") (pintype "bidirectional"))
      (node (ref "LED7") (pin "3") (pinfunction "COM_3") (pintype "bidirectional"))
      (node (ref "LED70") (pin "3") (pinfunction "COM_3") (pintype "bidirectional"))
      (node (ref "LED71") (pin "3") (pinfunction "COM_3") (pintype "bidirectional"))
      (node (ref "LED72") (pin "3") (pinfunction "COM_3") (pintype "bidirectional"))
      (node (ref "LED73") (pin "3") (pinfunction "COM_3") (pintype "bidirectional"))
      (node (ref "LED74") (pin "3") (pinfunction "COM_3") (pintype "bidirectional"))
      (node (ref "LED75") (pin "3") (pinfunction "COM_3") (pintype "bidirectional"))
      (node (ref "LED76") (pin "3") (pinfunction "COM_3") (pintype "bidirectional"))
      (node (ref "LED77") (pin "3") (pinfunction "COM_3") (pintype "bidirectional"))
      (node (ref "LED78") (pin "3") (pinfunction "COM_3") (pintype "bidirectional"))
      (node (ref "LED79") (pin "3") (pinfunction "COM_3") (pintype "bidirectional"))
      (node (ref "LED8") (pin "3") (pinfunction "COM_3") (pintype "bidirectional"))
      (node (ref "LED80") (pin "3") (pinfunction "COM_3") (pintype "bidirectional"))
      (node (ref "LED81") (pin "3") (pinfunction "COM_3") (pintype "bidirectional"))
      (node (ref "LED82") (pin "3") (pinfunction "COM_3") (pintype "bidirectional"))
      (node (ref "LED83") (pin "3") (pinfunction "COM_3") (pintype "bidirectional"))
      (node (ref "LED84") (pin "3") (pinfunction "COM_3") (pintype "bidirectional"))
      (node (ref "LED85") (pin "3") (pinfunction "COM_3") (pintype "bidirectional"))
      (node (ref "LED86") (pin "3") (pinfunction "COM_3") (pintype "bidirectional"))
      (node (ref "LED87") (pin "3") (pinfunction "COM_3") (pintype "bidirectional"))
      (node (ref "LED88") (pin "3") (pinfunction "COM_3") (pintype "bidirectional"))
      (node (ref "LED89") (pin "3") (pinfunction "COM_3") (pintype "bidirectional"))
      (node (ref "LED9") (pin "3") (pinfunction "COM_3") (pintype "bidirectional"))
      (node (ref "LED90") (pin "3") (pinfunction "COM_3") (pintype "bidirectional"))
      (node (ref "LED91") (pin "3") (pinfunction "COM_3") (pintype "bidirectional"))
      (node (ref "LED92") (pin "3") (pinfunction "COM_3") (pintype "bidirectional"))
      (node (ref "LED93") (pin "3") (pinfunction "COM_3") (pintype "bidirectional"))
      (node (ref "LED94") (pin "3") (pinfunction "COM_3") (pintype "bidirectional"))
      (node (ref "LED95") (pin "3") (pinfunction "COM_3") (pintype "bidirectional"))
      (node (ref "LED96") (pin "3") (pinfunction "COM_3") (pintype "bidirectional"))
      (node (ref "LED97") (pin "3") (pinfunction "COM_3") (pintype "bidirectional"))
      (node (ref "LED98") (pin "3") (pinfunction "COM_3") (pintype "bidirectional"))
      (node (ref "LED99") (pin "3") (pinfunction "COM_3") (pintype "bidirectional"))
    )
    (net (code "2") (name "/GND") (class "Default")
      (node (ref "IC1") (pin "29") (pinfunction "GND_1_29") (pintype "bidirectional"))
      (node (ref "IC1") (pin "56") (pinfunction "GND_2_56") (pintype "bidirectional"))
      (node (ref "IC1") (pin "57") (pinfunction "THERMALPAD_57") (pintype "bidirectional"))
      (node (ref "IC2") (pin "29") (pinfunction "GND_1_29") (pintype "bidirectional"))
      (node (ref "IC2") (pin "56") (pinfunction "GND_2_56") (pintype "bidirectional"))
      (node (ref "IC2") (pin "57") (pinfunction "THERMALPAD_57") (pintype "bidirectional"))
      (node (ref "IC3") (pin "29") (pinfunction "GND_1_29") (pintype "bidirectional"))
      (node (ref "IC3") (pin "56") (pinfunction "GND_2_56") (pintype "bidirectional"))
      (node (ref "IC3") (pin "57") (pinfunction "THERMALPAD_57") (pintype "bidirectional"))
      (node (ref "IC4") (pin "29") (pinfunction "GND_1_29") (pintype "bidirectional"))
      (node (ref "IC4") (pin "56") (pinfunction "GND_2_56") (pintype "bidirectional"))
      (node (ref "IC4") (pin "57") (pinfunction "THERMALPAD_57") (pintype "bidirectional"))
      (node (ref "IC5") (pin "29") (pinfunction "GND_1_29") (pintype "bidirectional"))
      (node (ref "IC5") (pin "56") (pinfunction "GND_2_56") (pintype "bidirectional"))
      (node (ref "IC5") (pin "57") (pinfunction "THERMALPAD_57") (pintype "bidirectional"))
      (node (ref "IC6") (pin "29") (pinfunction "GND_1_29") (pintype "bidirectional"))
      (node (ref "IC6") (pin "56") (pinfunction "GND_2_56") (pintype "bidirectional"))
      (node (ref "IC6") (pin "57") (pinfunction "THERMALPAD_57") (pintype "bidirectional"))
      (node (ref "IC7") (pin "29") (pinfunction "GND_1_29") (pintype "bidirectional"))
      (node (ref "IC7") (pin "56") (pinfunction "GND_2_56") (pintype "bidirectional"))
      (node (ref "IC7") (pin "57") (pinfunction "THERMALPAD_57") (pintype "bidirectional"))
      (node (ref "IC8") (pin "29") (pinfunction "GND_1_29") (pintype "bidirectional"))
      (node (ref "IC8") (pin "56") (pinfunction "GND_2_56") (pintype "bidirectional"))
      (node (ref "IC8") (pin "57") (pinfunction "THERMALPAD_57") (pintype "bidirectional"))
    )
    (net (code "3") (name "/GSCLK") (class "Default")
      (node (ref "IC1") (pin "55") (pinfunction "GSCLK_55") (pintype "bidirectional"))
      (node (ref "IC2") (pin "55") (pinfunction "GSCLK_55") (pintype "bidirectional"))
      (node (ref "IC3") (pin "55") (pinfunction "GSCLK_55") (pintype "bidirectional"))
      (node (ref "IC4") (pin "55") (pinfunction "GSCLK_55") (pintype "bidirectional"))
      (node (ref "IC5") (pin "55") (pinfunction "GSCLK_55") (pintype "bidirectional"))
      (node (ref "IC6") (pin "55") (pinfunction "GSCLK_55") (pintype "bidirectional"))
      (node (ref "IC7") (pin "55") (pinfunction "GSCLK_55") (pintype "bidirectional"))
      (node (ref "IC8") (pin "55") (pinfunction "GSCLK_55") (pintype "bidirectional"))
    )
    (net (code "4") (name "/LAT") (class "Default")
      (node (ref "IC1") (pin "3") (pinfunction "LAT_3") (pintype "bidirectional"))
      (node (ref "IC2") (pin "3") (pinfunction "LAT_3") (pintype "bidirectional"))
      (node (ref "IC3") (pin "3") (pinfunction "LAT_3") (pintype "bidirectional"))
      (node (ref "IC4") (pin "3") (pinfunction "LAT_3") (pintype "bidirectional"))
      (node (ref "IC5") (pin "3") (pinfunction "LAT_3") (pintype "bidirectional"))
      (node (ref "IC6") (pin "3") (pinfunction "LAT_3") (pintype "bidirectional"))
      (node (ref "IC7") (pin "3") (pinfunction "LAT_3") (pintype "bidirectional"))
      (node (ref "IC8") (pin "3") (pinfunction "LAT_3") (pintype "bidirectional"))
    )
    (net (code "5") (name "/LEDB1_1") (class "Default")
      (node (ref "LED1") (pin "2") (pinfunction "BLUE_2") (pintype "bidirectional"))
    )
    (net (code "6") (name "/LEDB1_2") (class "Default")
      (node (ref "LED5") (pin "2") (pinfunction "BLUE_2") (pintype "bidirectional"))
    )
    (net (code "7") (name "/LEDB1_3") (class "Default")
      (node (ref "LED9") (pin "2") (pinfunction "BLUE_2") (pintype "bidirectional"))
    )
    (net (code "8") (name "/LEDB1_4") (class "Default")
      (node (ref "LED13") (pin "2") (pinfunction "BLUE_2") (pintype "bidirectional"))
    )
    (net (code "9") (name "/LEDB1_5") (class "Default")
      (node (ref "LED17") (pin "2") (pinfunction "BLUE_2") (pintype "bidirectional"))
    )
    (net (code "10") (name "/LEDB1_6") (class "Default")
      (node (ref "LED21") (pin "2") (pinfunction "BLUE_2") (pintype "bidirectional"))
    )
    (net (code "11") (name "/LEDB1_7") (class "Default")
      (node (ref "LED25") (pin "2") (pinfunction "BLUE_2") (pintype "bidirectional"))
    )
    (net (code "12") (name "/LEDB1_8") (class "Default")
      (node (ref "LED29") (pin "2") (pinfunction "BLUE_2") (pintype "bidirectional"))
    )
    (net (code "13") (name "/LEDB1_9") (class "Default")
      (node (ref "LED33") (pin "2") (pinfunction "BLUE_2") (pintype "bidirectional"))
    )
    (net (code "14") (name "/LEDB1_10") (class "Default")
      (node (ref "LED37") (pin "2") (pinfunction "BLUE_2") (pintype "bidirectional"))
    )
    (net (code "15") (name "/LEDB1_11") (class "Default")
      (node (ref "LED41") (pin "2") (pinfunction "BLUE_2") (pintype "bidirectional"))
    )
    (net (code "16") (name "/LEDB1_12") (class "Default")
      (node (ref "LED45") (pin "2") (pinfunction "BLUE_2") (pintype "bidirectional"))
    )
    (net (code "17") (name "/LEDB1_13") (class "Default")
      (node (ref "LED49") (pin "2") (pinfunction "BLUE_2") (pintype "bidirectional"))
    )
    (net (code "18") (name "/LEDB1_14") (class "Default")
      (node (ref "LED53") (pin "2") (pinfunction "BLUE_2") (pintype "bidirectional"))
    )
    (net (code "19") (name "/LEDB1_15") (class "Default")
      (node (ref "LED57") (pin "2") (pinfunction "BLUE_2") (pintype "bidirectional"))
    )
    (net (code "20") (name "/LEDB1_16") (class "Default")
      (node (ref "LED61") (pin "2") (pinfunction "BLUE_2") (pintype "bidirectional"))
    )
    (net (code "21") (name "/LEDB1_17") (class "Default")
      (node (ref "LED65") (pin "2") (pinfunction "BLUE_2") (pintype "bidirectional"))
    )
    (net (code "22") (name "/LEDB1_18") (class "Default")
      (node (ref "LED69") (pin "2") (pinfunction "BLUE_2") (pintype "bidirectional"))
    )
    (net (code "23") (name "/LEDB1_19") (class "Default")
      (node (ref "LED73") (pin "2") (pinfunction "BLUE_2") (pintype "bidirectional"))
    )
    (net (code "24") (name "/LEDB1_20") (class "Default")
      (node (ref "LED77") (pin "2") (pinfunction "BLUE_2") (pintype "bidirectional"))
    )
    (net (code "25") (name "/LEDB1_21") (class "Default")
      (node (ref "LED81") (pin "2") (pinfunction "BLUE_2") (pintype "bidirectional"))
    )
    (net (code "26") (name "/LEDB1_22") (class "Default")
      (node (ref "LED85") (pin "2") (pinfunction "BLUE_2") (pintype "bidirectional"))
    )
    (net (code "27") (name "/LEDB1_23") (class "Default")
      (node (ref "LED89") (pin "2") (pinfunction "BLUE_2") (pintype "bidirectional"))
    )
    (net (code "28") (name "/LEDB1_24") (class "Default")
      (node (ref "LED93") (pin "2") (pinfunction "BLUE_2") (pintype "bidirectional"))
    )
    (net (code "29") (name "/LEDB1_25") (class "Default")
      (node (ref "LED97") (pin "2") (pinfunction "BLUE_2") (pintype "bidirectional"))
    )
    (net (code "30") (name "/LEDB1_26") (class "Default")
      (node (ref "LED101") (pin "2") (pinfunction "BLUE_2") (pintype "bidirectional"))
    )
    (net (code "31") (name "/LEDB1_27") (class "Default")
      (node (ref "LED105") (pin "2") (pinfunction "BLUE_2") (pintype "bidirectional"))
    )
    (net (code "32") (name "/LEDB1_28") (class "Default")
      (node (ref "LED109") (pin "2") (pinfunction "BLUE_2") (pintype "bidirectional"))
    )
    (net (code "33") (name "/LEDB1_29") (class "Default")
      (node (ref "LED113") (pin "2") (pinfunction "BLUE_2") (pintype "bidirectional"))
    )
    (net (code "34") (name "/LEDB1_30") (class "Default")
      (node (ref "LED117") (pin "2") (pinfunction "BLUE_2") (pintype "bidirectional"))
    )
    (net (code "35") (name "/LEDB2_1") (class "Default")
      (node (ref "LED2") (pin "2") (pinfunction "BLUE_2") (pintype "bidirectional"))
    )
    (net (code "36") (name "/LEDB2_2") (class "Default")
      (node (ref "LED6") (pin "2") (pinfunction "BLUE_2") (pintype "bidirectional"))
    )
    (net (code "37") (name "/LEDB2_3") (class "Default")
      (node (ref "LED10") (pin "2") (pinfunction "BLUE_2") (pintype "bidirectional"))
    )
    (net (code "38") (name "/LEDB2_4") (class "Default")
      (node (ref "LED14") (pin "2") (pinfunction "BLUE_2") (pintype "bidirectional"))
    )
    (net (code "39") (name "/LEDB2_5") (class "Default")
      (node (ref "LED18") (pin "2") (pinfunction "BLUE_2") (pintype "bidirectional"))
    )
    (net (code "40") (name "/LEDB2_6") (class "Default")
      (node (ref "LED22") (pin "2") (pinfunction "BLUE_2") (pintype "bidirectional"))
    )
    (net (code "41") (name "/LEDB2_7") (class "Default")
      (node (ref "LED26") (pin "2") (pinfunction "BLUE_2") (pintype "bidirectional"))
    )
    (net (code "42") (name "/LEDB2_8") (class "Default")
      (node (ref "LED30") (pin "2") (pinfunction "BLUE_2") (pintype "bidirectional"))
    )
    (net (code "43") (name "/LEDB2_9") (class "Default")
      (node (ref "LED34") (pin "2") (pinfunction "BLUE_2") (pintype "bidirectional"))
    )
    (net (code "44") (name "/LEDB2_10") (class "Default")
      (node (ref "LED38") (pin "2") (pinfunction "BLUE_2") (pintype "bidirectional"))
    )
    (net (code "45") (name "/LEDB2_11") (class "Default")
      (node (ref "LED42") (pin "2") (pinfunction "BLUE_2") (pintype "bidirectional"))
    )
    (net (code "46") (name "/LEDB2_12") (class "Default")
      (node (ref "LED46") (pin "2") (pinfunction "BLUE_2") (pintype "bidirectional"))
    )
    (net (code "47") (name "/LEDB2_13") (class "Default")
      (node (ref "LED50") (pin "2") (pinfunction "BLUE_2") (pintype "bidirectional"))
    )
    (net (code "48") (name "/LEDB2_14") (class "Default")
      (node (ref "LED54") (pin "2") (pinfunction "BLUE_2") (pintype "bidirectional"))
    )
    (net (code "49") (name "/LEDB2_15") (class "Default")
      (node (ref "LED58") (pin "2") (pinfunction "BLUE_2") (pintype "bidirectional"))
    )
    (net (code "50") (name "/LEDB2_16") (class "Default")
      (node (ref "LED62") (pin "2") (pinfunction "BLUE_2") (pintype "bidirectional"))
    )
    (net (code "51") (name "/LEDB2_17") (class "Default")
      (node (ref "LED66") (pin "2") (pinfunction "BLUE_2") (pintype "bidirectional"))
    )
    (net (code "52") (name "/LEDB2_18") (class "Default")
      (node (ref "LED70") (pin "2") (pinfunction "BLUE_2") (pintype "bidirectional"))
    )
    (net (code "53") (name "/LEDB2_19") (class "Default")
      (node (ref "LED74") (pin "2") (pinfunction "BLUE_2") (pintype "bidirectional"))
    )
    (net (code "54") (name "/LEDB2_20") (class "Default")
      (node (ref "LED78") (pin "2") (pinfunction "BLUE_2") (pintype "bidirectional"))
    )
    (net (code "55") (name "/LEDB2_21") (class "Default")
      (node (ref "LED82") (pin "2") (pinfunction "BLUE_2") (pintype "bidirectional"))
    )
    (net (code "56") (name "/LEDB2_22") (class "Default")
      (node (ref "LED86") (pin "2") (pinfunction "BLUE_2") (pintype "bidirectional"))
    )
    (net (code "57") (name "/LEDB2_23") (class "Default")
      (node (ref "LED90") (pin "2") (pinfunction "BLUE_2") (pintype "bidirectional"))
    )
    (net (code "58") (name "/LEDB2_24") (class "Default")
      (node (ref "LED94") (pin "2") (pinfunction "BLUE_2") (pintype "bidirectional"))
    )
    (net (code "59") (name "/LEDB2_25") (class "Default")
      (node (ref "LED98") (pin "2") (pinfunction "BLUE_2") (pintype "bidirectional"))
    )
    (net (code "60") (name "/LEDB2_26") (class "Default")
      (node (ref "LED102") (pin "2") (pinfunction "BLUE_2") (pintype "bidirectional"))
    )
    (net (code "61") (name "/LEDB2_27") (class "Default")
      (node (ref "LED106") (pin "2") (pinfunction "BLUE_2") (pintype "bidirectional"))
    )
    (net (code "62") (name "/LEDB2_28") (class "Default")
      (node (ref "LED110") (pin "2") (pinfunction "BLUE_2") (pintype "bidirectional"))
    )
    (net (code "63") (name "/LEDB2_29") (class "Default")
      (node (ref "LED114") (pin "2") (pinfunction "BLUE_2") (pintype "bidirectional"))
    )
    (net (code "64") (name "/LEDB2_30") (class "Default")
      (node (ref "LED118") (pin "2") (pinfunction "BLUE_2") (pintype "bidirectional"))
    )
    (net (code "65") (name "/LEDB3_") (class "Default")
      (node (ref "LED31") (pin "2") (pinfunction "BLUE_2") (pintype "bidirectional"))
    )
    (net (code "66") (name "/LEDB3_1") (class "Default")
      (node (ref "LED3") (pin "2") (pinfunction "BLUE_2") (pintype "bidirectional"))
    )
    (net (code "67") (name "/LEDB3_2") (class "Default")
      (node (ref "LED7") (pin "2") (pinfunction "BLUE_2") (pintype "bidirectional"))
    )
    (net (code "68") (name "/LEDB3_3") (class "Default")
      (node (ref "LED11") (pin "2") (pinfunction "BLUE_2") (pintype "bidirectional"))
    )
    (net (code "69") (name "/LEDB3_4") (class "Default")
      (node (ref "LED15") (pin "2") (pinfunction "BLUE_2") (pintype "bidirectional"))
    )
    (net (code "70") (name "/LEDB3_5") (class "Default")
      (node (ref "LED19") (pin "2") (pinfunction "BLUE_2") (pintype "bidirectional"))
    )
    (net (code "71") (name "/LEDB3_6") (class "Default")
      (node (ref "LED23") (pin "2") (pinfunction "BLUE_2") (pintype "bidirectional"))
    )
    (net (code "72") (name "/LEDB3_7") (class "Default")
      (node (ref "LED27") (pin "2") (pinfunction "BLUE_2") (pintype "bidirectional"))
    )
    (net (code "73") (name "/LEDB3_9") (class "Default")
      (node (ref "LED35") (pin "2") (pinfunction "BLUE_2") (pintype "bidirectional"))
    )
    (net (code "74") (name "/LEDB3_10") (class "Default")
      (node (ref "LED39") (pin "2") (pinfunction "BLUE_2") (pintype "bidirectional"))
    )
    (net (code "75") (name "/LEDB3_11") (class "Default")
      (node (ref "LED43") (pin "2") (pinfunction "BLUE_2") (pintype "bidirectional"))
    )
    (net (code "76") (name "/LEDB3_12") (class "Default")
      (node (ref "LED47") (pin "2") (pinfunction "BLUE_2") (pintype "bidirectional"))
    )
    (net (code "77") (name "/LEDB3_13") (class "Default")
      (node (ref "LED51") (pin "2") (pinfunction "BLUE_2") (pintype "bidirectional"))
    )
    (net (code "78") (name "/LEDB3_14") (class "Default")
      (node (ref "LED55") (pin "2") (pinfunction "BLUE_2") (pintype "bidirectional"))
    )
    (net (code "79") (name "/LEDB3_15") (class "Default")
      (node (ref "LED59") (pin "2") (pinfunction "BLUE_2") (pintype "bidirectional"))
    )
    (net (code "80") (name "/LEDB3_16") (class "Default")
      (node (ref "LED63") (pin "2") (pinfunction "BLUE_2") (pintype "bidirectional"))
    )
    (net (code "81") (name "/LEDB3_17") (class "Default")
      (node (ref "LED67") (pin "2") (pinfunction "BLUE_2") (pintype "bidirectional"))
    )
    (net (code "82") (name "/LEDB3_18") (class "Default")
      (node (ref "LED71") (pin "2") (pinfunction "BLUE_2") (pintype "bidirectional"))
    )
    (net (code "83") (name "/LEDB3_19") (class "Default")
      (node (ref "LED75") (pin "2") (pinfunction "BLUE_2") (pintype "bidirectional"))
    )
    (net (code "84") (name "/LEDB3_20") (class "Default")
      (node (ref "LED79") (pin "2") (pinfunction "BLUE_2") (pintype "bidirectional"))
    )
    (net (code "85") (name "/LEDB3_21") (class "Default")
      (node (ref "LED83") (pin "2") (pinfunction "BLUE_2") (pintype "bidirectional"))
    )
    (net (code "86") (name "/LEDB3_22") (class "Default")
      (node (ref "LED87") (pin "2") (pinfunction "BLUE_2") (pintype "bidirectional"))
    )
    (net (code "87") (name "/LEDB3_23") (class "Default")
      (node (ref "LED91") (pin "2") (pinfunction "BLUE_2") (pintype "bidirectional"))
    )
    (net (code "88") (name "/LEDB3_24") (class "Default")
      (node (ref "LED95") (pin "2") (pinfunction "BLUE_2") (pintype "bidirectional"))
    )
    (net (code "89") (name "/LEDB3_25") (class "Default")
      (node (ref "LED99") (pin "2") (pinfunction "BLUE_2") (pintype "bidirectional"))
    )
    (net (code "90") (name "/LEDB3_26") (class "Default")
      (node (ref "LED103") (pin "2") (pinfunction "BLUE_2") (pintype "bidirectional"))
    )
    (net (code "91") (name "/LEDB3_27") (class "Default")
      (node (ref "LED107") (pin "2") (pinfunction "BLUE_2") (pintype "bidirectional"))
    )
    (net (code "92") (name "/LEDB3_28") (class "Default")
      (node (ref "LED111") (pin "2") (pinfunction "BLUE_2") (pintype "bidirectional"))
    )
    (net (code "93") (name "/LEDB3_29") (class "Default")
      (node (ref "LED115") (pin "2") (pinfunction "BLUE_2") (pintype "bidirectional"))
    )
    (net (code "94") (name "/LEDB3_30") (class "Default")
      (node (ref "LED119") (pin "2") (pinfunction "BLUE_2") (pintype "bidirectional"))
    )
    (net (code "95") (name "/LEDB4_1") (class "Default")
      (node (ref "LED4") (pin "2") (pinfunction "BLUE_2") (pintype "bidirectional"))
    )
    (net (code "96") (name "/LEDB4_2") (class "Default")
      (node (ref "LED8") (pin "2") (pinfunction "BLUE_2") (pintype "bidirectional"))
    )
    (net (code "97") (name "/LEDB4_3") (class "Default")
      (node (ref "LED12") (pin "2") (pinfunction "BLUE_2") (pintype "bidirectional"))
    )
    (net (code "98") (name "/LEDB4_4") (class "Default")
      (node (ref "LED16") (pin "2") (pinfunction "BLUE_2") (pintype "bidirectional"))
    )
    (net (code "99") (name "/LEDB4_5") (class "Default")
      (node (ref "LED20") (pin "2") (pinfunction "BLUE_2") (pintype "bidirectional"))
    )
    (net (code "100") (name "/LEDB4_6") (class "Default")
      (node (ref "LED24") (pin "2") (pinfunction "BLUE_2") (pintype "bidirectional"))
    )
    (net (code "101") (name "/LEDB4_7") (class "Default")
      (node (ref "LED28") (pin "2") (pinfunction "BLUE_2") (pintype "bidirectional"))
    )
    (net (code "102") (name "/LEDB4_8") (class "Default")
      (node (ref "LED32") (pin "2") (pinfunction "BLUE_2") (pintype "bidirectional"))
    )
    (net (code "103") (name "/LEDB4_9") (class "Default")
      (node (ref "LED36") (pin "2") (pinfunction "BLUE_2") (pintype "bidirectional"))
    )
    (net (code "104") (name "/LEDB4_10") (class "Default")
      (node (ref "LED40") (pin "2") (pinfunction "BLUE_2") (pintype "bidirectional"))
    )
    (net (code "105") (name "/LEDB4_11") (class "Default")
      (node (ref "LED44") (pin "2") (pinfunction "BLUE_2") (pintype "bidirectional"))
    )
    (net (code "106") (name "/LEDB4_12") (class "Default")
      (node (ref "LED48") (pin "2") (pinfunction "BLUE_2") (pintype "bidirectional"))
    )
    (net (code "107") (name "/LEDB4_13") (class "Default")
      (node (ref "LED52") (pin "2") (pinfunction "BLUE_2") (pintype "bidirectional"))
    )
    (net (code "108") (name "/LEDB4_14") (class "Default")
      (node (ref "LED56") (pin "2") (pinfunction "BLUE_2") (pintype "bidirectional"))
    )
    (net (code "109") (name "/LEDB4_15") (class "Default")
      (node (ref "LED60") (pin "2") (pinfunction "BLUE_2") (pintype "bidirectional"))
    )
    (net (code "110") (name "/LEDB4_16") (class "Default")
      (node (ref "LED64") (pin "2") (pinfunction "BLUE_2") (pintype "bidirectional"))
    )
    (net (code "111") (name "/LEDB4_17") (class "Default")
      (node (ref "LED68") (pin "2") (pinfunction "BLUE_2") (pintype "bidirectional"))
    )
    (net (code "112") (name "/LEDB4_18") (class "Default")
      (node (ref "LED72") (pin "2") (pinfunction "BLUE_2") (pintype "bidirectional"))
    )
    (net (code "113") (name "/LEDB4_19") (class "Default")
      (node (ref "LED76") (pin "2") (pinfunction "BLUE_2") (pintype "bidirectional"))
    )
    (net (code "114") (name "/LEDB4_20") (class "Default")
      (node (ref "LED80") (pin "2") (pinfunction "BLUE_2") (pintype "bidirectional"))
    )
    (net (code "115") (name "/LEDB4_21") (class "Default")
      (node (ref "LED84") (pin "2") (pinfunction "BLUE_2") (pintype "bidirectional"))
    )
    (net (code "116") (name "/LEDB4_22") (class "Default")
      (node (ref "LED88") (pin "2") (pinfunction "BLUE_2") (pintype "bidirectional"))
    )
    (net (code "117") (name "/LEDB4_23") (class "Default")
      (node (ref "LED92") (pin "2") (pinfunction "BLUE_2") (pintype "bidirectional"))
    )
    (net (code "118") (name "/LEDB4_24") (class "Default")
      (node (ref "LED96") (pin "2") (pinfunction "BLUE_2") (pintype "bidirectional"))
    )
    (net (code "119") (name "/LEDB4_25") (class "Default")
      (node (ref "LED100") (pin "2") (pinfunction "BLUE_2") (pintype "bidirectional"))
    )
    (net (code "120") (name "/LEDB4_26") (class "Default")
      (node (ref "LED104") (pin "2") (pinfunction "BLUE_2") (pintype "bidirectional"))
    )
    (net (code "121") (name "/LEDB4_27") (class "Default")
      (node (ref "LED108") (pin "2") (pinfunction "BLUE_2") (pintype "bidirectional"))
    )
    (net (code "122") (name "/LEDB4_28") (class "Default")
      (node (ref "LED112") (pin "2") (pinfunction "BLUE_2") (pintype "bidirectional"))
    )
    (net (code "123") (name "/LEDB4_29") (class "Default")
      (node (ref "LED116") (pin "2") (pinfunction "BLUE_2") (pintype "bidirectional"))
    )
    (net (code "124") (name "/LEDB4_30") (class "Default")
      (node (ref "LED120") (pin "2") (pinfunction "BLUE_2") (pintype "bidirectional"))
    )
    (net (code "125") (name "/LEDG1_1") (class "Default")
      (node (ref "LED1") (pin "1") (pinfunction "GREEN_1") (pintype "bidirectional"))
    )
    (net (code "126") (name "/LEDG1_2") (class "Default")
      (node (ref "LED5") (pin "1") (pinfunction "GREEN_1") (pintype "bidirectional"))
    )
    (net (code "127") (name "/LEDG1_3") (class "Default")
      (node (ref "LED9") (pin "1") (pinfunction "GREEN_1") (pintype "bidirectional"))
    )
    (net (code "128") (name "/LEDG1_4") (class "Default")
      (node (ref "LED13") (pin "1") (pinfunction "GREEN_1") (pintype "bidirectional"))
    )
    (net (code "129") (name "/LEDG1_5") (class "Default")
      (node (ref "LED17") (pin "1") (pinfunction "GREEN_1") (pintype "bidirectional"))
    )
    (net (code "130") (name "/LEDG1_6") (class "Default")
      (node (ref "LED21") (pin "1") (pinfunction "GREEN_1") (pintype "bidirectional"))
    )
    (net (code "131") (name "/LEDG1_7") (class "Default")
      (node (ref "LED25") (pin "1") (pinfunction "GREEN_1") (pintype "bidirectional"))
    )
    (net (code "132") (name "/LEDG1_8") (class "Default")
      (node (ref "LED29") (pin "1") (pinfunction "GREEN_1") (pintype "bidirectional"))
    )
    (net (code "133") (name "/LEDG1_9") (class "Default")
      (node (ref "LED33") (pin "1") (pinfunction "GREEN_1") (pintype "bidirectional"))
    )
    (net (code "134") (name "/LEDG1_10") (class "Default")
      (node (ref "LED37") (pin "1") (pinfunction "GREEN_1") (pintype "bidirectional"))
    )
    (net (code "135") (name "/LEDG1_11") (class "Default")
      (node (ref "LED41") (pin "1") (pinfunction "GREEN_1") (pintype "bidirectional"))
    )
    (net (code "136") (name "/LEDG1_12") (class "Default")
      (node (ref "LED45") (pin "1") (pinfunction "GREEN_1") (pintype "bidirectional"))
    )
    (net (code "137") (name "/LEDG1_13") (class "Default")
      (node (ref "LED49") (pin "1") (pinfunction "GREEN_1") (pintype "bidirectional"))
    )
    (net (code "138") (name "/LEDG1_14") (class "Default")
      (node (ref "LED53") (pin "1") (pinfunction "GREEN_1") (pintype "bidirectional"))
    )
    (net (code "139") (name "/LEDG1_15") (class "Default")
      (node (ref "LED57") (pin "1") (pinfunction "GREEN_1") (pintype "bidirectional"))
    )
    (net (code "140") (name "/LEDG1_16") (class "Default")
      (node (ref "LED61") (pin "1") (pinfunction "GREEN_1") (pintype "bidirectional"))
    )
    (net (code "141") (name "/LEDG1_17") (class "Default")
      (node (ref "LED65") (pin "1") (pinfunction "GREEN_1") (pintype "bidirectional"))
    )
    (net (code "142") (name "/LEDG1_18") (class "Default")
      (node (ref "LED69") (pin "1") (pinfunction "GREEN_1") (pintype "bidirectional"))
    )
    (net (code "143") (name "/LEDG1_19") (class "Default")
      (node (ref "LED73") (pin "1") (pinfunction "GREEN_1") (pintype "bidirectional"))
    )
    (net (code "144") (name "/LEDG1_20") (class "Default")
      (node (ref "LED77") (pin "1") (pinfunction "GREEN_1") (pintype "bidirectional"))
    )
    (net (code "145") (name "/LEDG1_21") (class "Default")
      (node (ref "LED81") (pin "1") (pinfunction "GREEN_1") (pintype "bidirectional"))
    )
    (net (code "146") (name "/LEDG1_22") (class "Default")
      (node (ref "LED85") (pin "1") (pinfunction "GREEN_1") (pintype "bidirectional"))
    )
    (net (code "147") (name "/LEDG1_23") (class "Default")
      (node (ref "LED89") (pin "1") (pinfunction "GREEN_1") (pintype "bidirectional"))
    )
    (net (code "148") (name "/LEDG1_24") (class "Default")
      (node (ref "LED93") (pin "1") (pinfunction "GREEN_1") (pintype "bidirectional"))
    )
    (net (code "149") (name "/LEDG1_25") (class "Default")
      (node (ref "LED97") (pin "1") (pinfunction "GREEN_1") (pintype "bidirectional"))
    )
    (net (code "150") (name "/LEDG1_26") (class "Default")
      (node (ref "LED101") (pin "1") (pinfunction "GREEN_1") (pintype "bidirectional"))
    )
    (net (code "151") (name "/LEDG1_27") (class "Default")
      (node (ref "LED105") (pin "1") (pinfunction "GREEN_1") (pintype "bidirectional"))
    )
    (net (code "152") (name "/LEDG1_28") (class "Default")
      (node (ref "LED109") (pin "1") (pinfunction "GREEN_1") (pintype "bidirectional"))
    )
    (net (code "153") (name "/LEDG1_29") (class "Default")
      (node (ref "LED113") (pin "1") (pinfunction "GREEN_1") (pintype "bidirectional"))
    )
    (net (code "154") (name "/LEDG1_30") (class "Default")
      (node (ref "LED117") (pin "1") (pinfunction "GREEN_1") (pintype "bidirectional"))
    )
    (net (code "155") (name "/LEDG2_1") (class "Default")
      (node (ref "LED2") (pin "1") (pinfunction "GREEN_1") (pintype "bidirectional"))
    )
    (net (code "156") (name "/LEDG2_2") (class "Default")
      (node (ref "LED6") (pin "1") (pinfunction "GREEN_1") (pintype "bidirectional"))
    )
    (net (code "157") (name "/LEDG2_3") (class "Default")
      (node (ref "LED10") (pin "1") (pinfunction "GREEN_1") (pintype "bidirectional"))
    )
    (net (code "158") (name "/LEDG2_4") (class "Default")
      (node (ref "LED14") (pin "1") (pinfunction "GREEN_1") (pintype "bidirectional"))
    )
    (net (code "159") (name "/LEDG2_5") (class "Default")
      (node (ref "LED18") (pin "1") (pinfunction "GREEN_1") (pintype "bidirectional"))
    )
    (net (code "160") (name "/LEDG2_6") (class "Default")
      (node (ref "LED22") (pin "1") (pinfunction "GREEN_1") (pintype "bidirectional"))
    )
    (net (code "161") (name "/LEDG2_7") (class "Default")
      (node (ref "LED26") (pin "1") (pinfunction "GREEN_1") (pintype "bidirectional"))
    )
    (net (code "162") (name "/LEDG2_8") (class "Default")
      (node (ref "LED30") (pin "1") (pinfunction "GREEN_1") (pintype "bidirectional"))
    )
    (net (code "163") (name "/LEDG2_9") (class "Default")
      (node (ref "LED34") (pin "1") (pinfunction "GREEN_1") (pintype "bidirectional"))
    )
    (net (code "164") (name "/LEDG2_10") (class "Default")
      (node (ref "LED38") (pin "1") (pinfunction "GREEN_1") (pintype "bidirectional"))
    )
    (net (code "165") (name "/LEDG2_11") (class "Default")
      (node (ref "LED42") (pin "1") (pinfunction "GREEN_1") (pintype "bidirectional"))
    )
    (net (code "166") (name "/LEDG2_12") (class "Default")
      (node (ref "LED46") (pin "1") (pinfunction "GREEN_1") (pintype "bidirectional"))
    )
    (net (code "167") (name "/LEDG2_13") (class "Default")
      (node (ref "LED50") (pin "1") (pinfunction "GREEN_1") (pintype "bidirectional"))
    )
    (net (code "168") (name "/LEDG2_14") (class "Default")
      (node (ref "LED54") (pin "1") (pinfunction "GREEN_1") (pintype "bidirectional"))
    )
    (net (code "169") (name "/LEDG2_15") (class "Default")
      (node (ref "LED58") (pin "1") (pinfunction "GREEN_1") (pintype "bidirectional"))
    )
    (net (code "170") (name "/LEDG2_16") (class "Default")
      (node (ref "LED62") (pin "1") (pinfunction "GREEN_1") (pintype "bidirectional"))
    )
    (net (code "171") (name "/LEDG2_17") (class "Default")
      (node (ref "LED66") (pin "1") (pinfunction "GREEN_1") (pintype "bidirectional"))
    )
    (net (code "172") (name "/LEDG2_18") (class "Default")
      (node (ref "LED70") (pin "1") (pinfunction "GREEN_1") (pintype "bidirectional"))
    )
    (net (code "173") (name "/LEDG2_19") (class "Default")
      (node (ref "LED74") (pin "1") (pinfunction "GREEN_1") (pintype "bidirectional"))
    )
    (net (code "174") (name "/LEDG2_20") (class "Default")
      (node (ref "LED78") (pin "1") (pinfunction "GREEN_1") (pintype "bidirectional"))
    )
    (net (code "175") (name "/LEDG2_21") (class "Default")
      (node (ref "LED82") (pin "1") (pinfunction "GREEN_1") (pintype "bidirectional"))
    )
    (net (code "176") (name "/LEDG2_22") (class "Default")
      (node (ref "LED86") (pin "1") (pinfunction "GREEN_1") (pintype "bidirectional"))
    )
    (net (code "177") (name "/LEDG2_23") (class "Default")
      (node (ref "LED90") (pin "1") (pinfunction "GREEN_1") (pintype "bidirectional"))
    )
    (net (code "178") (name "/LEDG2_24") (class "Default")
      (node (ref "LED94") (pin "1") (pinfunction "GREEN_1") (pintype "bidirectional"))
    )
    (net (code "179") (name "/LEDG2_25") (class "Default")
      (node (ref "LED98") (pin "1") (pinfunction "GREEN_1") (pintype "bidirectional"))
    )
    (net (code "180") (name "/LEDG2_26") (class "Default")
      (node (ref "LED102") (pin "1") (pinfunction "GREEN_1") (pintype "bidirectional"))
    )
    (net (code "181") (name "/LEDG2_27") (class "Default")
      (node (ref "LED106") (pin "1") (pinfunction "GREEN_1") (pintype "bidirectional"))
    )
    (net (code "182") (name "/LEDG2_28") (class "Default")
      (node (ref "LED110") (pin "1") (pinfunction "GREEN_1") (pintype "bidirectional"))
    )
    (net (code "183") (name "/LEDG2_29") (class "Default")
      (node (ref "LED114") (pin "1") (pinfunction "GREEN_1") (pintype "bidirectional"))
    )
    (net (code "184") (name "/LEDG2_30") (class "Default")
      (node (ref "LED118") (pin "1") (pinfunction "GREEN_1") (pintype "bidirectional"))
    )
    (net (code "185") (name "/LEDG3_1") (class "Default")
      (node (ref "LED3") (pin "1") (pinfunction "GREEN_1") (pintype "bidirectional"))
    )
    (net (code "186") (name "/LEDG3_2") (class "Default")
      (node (ref "LED7") (pin "1") (pinfunction "GREEN_1") (pintype "bidirectional"))
    )
    (net (code "187") (name "/LEDG3_3") (class "Default")
      (node (ref "LED11") (pin "1") (pinfunction "GREEN_1") (pintype "bidirectional"))
    )
    (net (code "188") (name "/LEDG3_4") (class "Default")
      (node (ref "LED15") (pin "1") (pinfunction "GREEN_1") (pintype "bidirectional"))
    )
    (net (code "189") (name "/LEDG3_5") (class "Default")
      (node (ref "LED19") (pin "1") (pinfunction "GREEN_1") (pintype "bidirectional"))
    )
    (net (code "190") (name "/LEDG3_6") (class "Default")
      (node (ref "LED23") (pin "1") (pinfunction "GREEN_1") (pintype "bidirectional"))
    )
    (net (code "191") (name "/LEDG3_7") (class "Default")
      (node (ref "LED27") (pin "1") (pinfunction "GREEN_1") (pintype "bidirectional"))
    )
    (net (code "192") (name "/LEDG3_8") (class "Default")
      (node (ref "LED31") (pin "1") (pinfunction "GREEN_1") (pintype "bidirectional"))
    )
    (net (code "193") (name "/LEDG3_9") (class "Default")
      (node (ref "LED35") (pin "1") (pinfunction "GREEN_1") (pintype "bidirectional"))
    )
    (net (code "194") (name "/LEDG3_10") (class "Default")
      (node (ref "LED39") (pin "1") (pinfunction "GREEN_1") (pintype "bidirectional"))
    )
    (net (code "195") (name "/LEDG3_11") (class "Default")
      (node (ref "LED43") (pin "1") (pinfunction "GREEN_1") (pintype "bidirectional"))
    )
    (net (code "196") (name "/LEDG3_12") (class "Default")
      (node (ref "LED47") (pin "1") (pinfunction "GREEN_1") (pintype "bidirectional"))
    )
    (net (code "197") (name "/LEDG3_13") (class "Default")
      (node (ref "LED51") (pin "1") (pinfunction "GREEN_1") (pintype "bidirectional"))
    )
    (net (code "198") (name "/LEDG3_14") (class "Default")
      (node (ref "LED55") (pin "1") (pinfunction "GREEN_1") (pintype "bidirectional"))
    )
    (net (code "199") (name "/LEDG3_15") (class "Default")
      (node (ref "LED59") (pin "1") (pinfunction "GREEN_1") (pintype "bidirectional"))
    )
    (net (code "200") (name "/LEDG3_16") (class "Default")
      (node (ref "LED63") (pin "1") (pinfunction "GREEN_1") (pintype "bidirectional"))
    )
    (net (code "201") (name "/LEDG3_17") (class "Default")
      (node (ref "LED67") (pin "1") (pinfunction "GREEN_1") (pintype "bidirectional"))
    )
    (net (code "202") (name "/LEDG3_18") (class "Default")
      (node (ref "LED71") (pin "1") (pinfunction "GREEN_1") (pintype "bidirectional"))
    )
    (net (code "203") (name "/LEDG3_19") (class "Default")
      (node (ref "LED75") (pin "1") (pinfunction "GREEN_1") (pintype "bidirectional"))
    )
    (net (code "204") (name "/LEDG3_20") (class "Default")
      (node (ref "LED79") (pin "1") (pinfunction "GREEN_1") (pintype "bidirectional"))
    )
    (net (code "205") (name "/LEDG3_21") (class "Default")
      (node (ref "LED83") (pin "1") (pinfunction "GREEN_1") (pintype "bidirectional"))
    )
    (net (code "206") (name "/LEDG3_22") (class "Default")
      (node (ref "LED87") (pin "1") (pinfunction "GREEN_1") (pintype "bidirectional"))
    )
    (net (code "207") (name "/LEDG3_23") (class "Default")
      (node (ref "LED91") (pin "1") (pinfunction "GREEN_1") (pintype "bidirectional"))
    )
    (net (code "208") (name "/LEDG3_24") (class "Default")
      (node (ref "LED95") (pin "1") (pinfunction "GREEN_1") (pintype "bidirectional"))
    )
    (net (code "209") (name "/LEDG3_25") (class "Default")
      (node (ref "LED99") (pin "1") (pinfunction "GREEN_1") (pintype "bidirectional"))
    )
    (net (code "210") (name "/LEDG3_26") (class "Default")
      (node (ref "LED103") (pin "1") (pinfunction "GREEN_1") (pintype "bidirectional"))
    )
    (net (code "211") (name "/LEDG3_27") (class "Default")
      (node (ref "LED107") (pin "1") (pinfunction "GREEN_1") (pintype "bidirectional"))
    )
    (net (code "212") (name "/LEDG3_28") (class "Default")
      (node (ref "LED111") (pin "1") (pinfunction "GREEN_1") (pintype "bidirectional"))
    )
    (net (code "213") (name "/LEDG3_29") (class "Default")
      (node (ref "LED115") (pin "1") (pinfunction "GREEN_1") (pintype "bidirectional"))
    )
    (net (code "214") (name "/LEDG3_30") (class "Default")
      (node (ref "LED119") (pin "1") (pinfunction "GREEN_1") (pintype "bidirectional"))
    )
    (net (code "215") (name "/LEDG4_1") (class "Default")
      (node (ref "LED4") (pin "1") (pinfunction "GREEN_1") (pintype "bidirectional"))
    )
    (net (code "216") (name "/LEDG4_2") (class "Default")
      (node (ref "LED8") (pin "1") (pinfunction "GREEN_1") (pintype "bidirectional"))
    )
    (net (code "217") (name "/LEDG4_3") (class "Default")
      (node (ref "LED12") (pin "1") (pinfunction "GREEN_1") (pintype "bidirectional"))
    )
    (net (code "218") (name "/LEDG4_4") (class "Default")
      (node (ref "LED16") (pin "1") (pinfunction "GREEN_1") (pintype "bidirectional"))
    )
    (net (code "219") (name "/LEDG4_5") (class "Default")
      (node (ref "LED20") (pin "1") (pinfunction "GREEN_1") (pintype "bidirectional"))
    )
    (net (code "220") (name "/LEDG4_6") (class "Default")
      (node (ref "LED24") (pin "1") (pinfunction "GREEN_1") (pintype "bidirectional"))
    )
    (net (code "221") (name "/LEDG4_7") (class "Default")
      (node (ref "LED28") (pin "1") (pinfunction "GREEN_1") (pintype "bidirectional"))
    )
    (net (code "222") (name "/LEDG4_8") (class "Default")
      (node (ref "LED32") (pin "1") (pinfunction "GREEN_1") (pintype "bidirectional"))
    )
    (net (code "223") (name "/LEDG4_9") (class "Default")
      (node (ref "LED36") (pin "1") (pinfunction "GREEN_1") (pintype "bidirectional"))
    )
    (net (code "224") (name "/LEDG4_10") (class "Default")
      (node (ref "LED40") (pin "1") (pinfunction "GREEN_1") (pintype "bidirectional"))
    )
    (net (code "225") (name "/LEDG4_11") (class "Default")
      (node (ref "LED44") (pin "1") (pinfunction "GREEN_1") (pintype "bidirectional"))
    )
    (net (code "226") (name "/LEDG4_12") (class "Default")
      (node (ref "LED48") (pin "1") (pinfunction "GREEN_1") (pintype "bidirectional"))
    )
    (net (code "227") (name "/LEDG4_13") (class "Default")
      (node (ref "LED52") (pin "1") (pinfunction "GREEN_1") (pintype "bidirectional"))
    )
    (net (code "228") (name "/LEDG4_14") (class "Default")
      (node (ref "LED56") (pin "1") (pinfunction "GREEN_1") (pintype "bidirectional"))
    )
    (net (code "229") (name "/LEDG4_15") (class "Default")
      (node (ref "LED60") (pin "1") (pinfunction "GREEN_1") (pintype "bidirectional"))
    )
    (net (code "230") (name "/LEDG4_16") (class "Default")
      (node (ref "LED64") (pin "1") (pinfunction "GREEN_1") (pintype "bidirectional"))
    )
    (net (code "231") (name "/LEDG4_17") (class "Default")
      (node (ref "LED68") (pin "1") (pinfunction "GREEN_1") (pintype "bidirectional"))
    )
    (net (code "232") (name "/LEDG4_18") (class "Default")
      (node (ref "LED72") (pin "1") (pinfunction "GREEN_1") (pintype "bidirectional"))
    )
    (net (code "233") (name "/LEDG4_19") (class "Default")
      (node (ref "LED76") (pin "1") (pinfunction "GREEN_1") (pintype "bidirectional"))
    )
    (net (code "234") (name "/LEDG4_20") (class "Default")
      (node (ref "LED80") (pin "1") (pinfunction "GREEN_1") (pintype "bidirectional"))
    )
    (net (code "235") (name "/LEDG4_21") (class "Default")
      (node (ref "LED84") (pin "1") (pinfunction "GREEN_1") (pintype "bidirectional"))
    )
    (net (code "236") (name "/LEDG4_22") (class "Default")
      (node (ref "LED88") (pin "1") (pinfunction "GREEN_1") (pintype "bidirectional"))
    )
    (net (code "237") (name "/LEDG4_23") (class "Default")
      (node (ref "LED92") (pin "1") (pinfunction "GREEN_1") (pintype "bidirectional"))
    )
    (net (code "238") (name "/LEDG4_24") (class "Default")
      (node (ref "LED96") (pin "1") (pinfunction "GREEN_1") (pintype "bidirectional"))
    )
    (net (code "239") (name "/LEDG4_25") (class "Default")
      (node (ref "LED100") (pin "1") (pinfunction "GREEN_1") (pintype "bidirectional"))
    )
    (net (code "240") (name "/LEDG4_26") (class "Default")
      (node (ref "LED104") (pin "1") (pinfunction "GREEN_1") (pintype "bidirectional"))
    )
    (net (code "241") (name "/LEDG4_27") (class "Default")
      (node (ref "LED108") (pin "1") (pinfunction "GREEN_1") (pintype "bidirectional"))
    )
    (net (code "242") (name "/LEDG4_28") (class "Default")
      (node (ref "LED112") (pin "1") (pinfunction "GREEN_1") (pintype "bidirectional"))
    )
    (net (code "243") (name "/LEDG4_29") (class "Default")
      (node (ref "LED116") (pin "1") (pinfunction "GREEN_1") (pintype "bidirectional"))
    )
    (net (code "244") (name "/LEDG4_30") (class "Default")
      (node (ref "LED120") (pin "1") (pinfunction "GREEN_1") (pintype "bidirectional"))
    )
    (net (code "245") (name "/LEDR1_1") (class "Default")
      (node (ref "LED1") (pin "4") (pinfunction "RED_4") (pintype "bidirectional"))
    )
    (net (code "246") (name "/LEDR1_2") (class "Default")
      (node (ref "LED5") (pin "4") (pinfunction "RED_4") (pintype "bidirectional"))
    )
    (net (code "247") (name "/LEDR1_3") (class "Default")
      (node (ref "LED9") (pin "4") (pinfunction "RED_4") (pintype "bidirectional"))
    )
    (net (code "248") (name "/LEDR1_4") (class "Default")
      (node (ref "LED13") (pin "4") (pinfunction "RED_4") (pintype "bidirectional"))
    )
    (net (code "249") (name "/LEDR1_5") (class "Default")
      (node (ref "LED17") (pin "4") (pinfunction "RED_4") (pintype "bidirectional"))
    )
    (net (code "250") (name "/LEDR1_6") (class "Default")
      (node (ref "LED21") (pin "4") (pinfunction "RED_4") (pintype "bidirectional"))
    )
    (net (code "251") (name "/LEDR1_7") (class "Default")
      (node (ref "LED25") (pin "4") (pinfunction "RED_4") (pintype "bidirectional"))
    )
    (net (code "252") (name "/LEDR1_8") (class "Default")
      (node (ref "LED29") (pin "4") (pinfunction "RED_4") (pintype "bidirectional"))
    )
    (net (code "253") (name "/LEDR1_9") (class "Default")
      (node (ref "LED33") (pin "4") (pinfunction "RED_4") (pintype "bidirectional"))
    )
    (net (code "254") (name "/LEDR1_10") (class "Default")
      (node (ref "LED37") (pin "4") (pinfunction "RED_4") (pintype "bidirectional"))
    )
    (net (code "255") (name "/LEDR1_11") (class "Default")
      (node (ref "LED41") (pin "4") (pinfunction "RED_4") (pintype "bidirectional"))
    )
    (net (code "256") (name "/LEDR1_12") (class "Default")
      (node (ref "LED45") (pin "4") (pinfunction "RED_4") (pintype "bidirectional"))
    )
    (net (code "257") (name "/LEDR1_13") (class "Default")
      (node (ref "LED49") (pin "4") (pinfunction "RED_4") (pintype "bidirectional"))
    )
    (net (code "258") (name "/LEDR1_14") (class "Default")
      (node (ref "LED53") (pin "4") (pinfunction "RED_4") (pintype "bidirectional"))
    )
    (net (code "259") (name "/LEDR1_15") (class "Default")
      (node (ref "LED57") (pin "4") (pinfunction "RED_4") (pintype "bidirectional"))
    )
    (net (code "260") (name "/LEDR1_16") (class "Default")
      (node (ref "LED61") (pin "4") (pinfunction "RED_4") (pintype "bidirectional"))
    )
    (net (code "261") (name "/LEDR1_17") (class "Default")
      (node (ref "LED65") (pin "4") (pinfunction "RED_4") (pintype "bidirectional"))
    )
    (net (code "262") (name "/LEDR1_18") (class "Default")
      (node (ref "LED69") (pin "4") (pinfunction "RED_4") (pintype "bidirectional"))
    )
    (net (code "263") (name "/LEDR1_19") (class "Default")
      (node (ref "LED73") (pin "4") (pinfunction "RED_4") (pintype "bidirectional"))
    )
    (net (code "264") (name "/LEDR1_20") (class "Default")
      (node (ref "LED77") (pin "4") (pinfunction "RED_4") (pintype "bidirectional"))
    )
    (net (code "265") (name "/LEDR1_21") (class "Default")
      (node (ref "LED81") (pin "4") (pinfunction "RED_4") (pintype "bidirectional"))
    )
    (net (code "266") (name "/LEDR1_22") (class "Default")
      (node (ref "LED85") (pin "4") (pinfunction "RED_4") (pintype "bidirectional"))
    )
    (net (code "267") (name "/LEDR1_23") (class "Default")
      (node (ref "LED89") (pin "4") (pinfunction "RED_4") (pintype "bidirectional"))
    )
    (net (code "268") (name "/LEDR1_24") (class "Default")
      (node (ref "LED93") (pin "4") (pinfunction "RED_4") (pintype "bidirectional"))
    )
    (net (code "269") (name "/LEDR1_25") (class "Default")
      (node (ref "LED97") (pin "4") (pinfunction "RED_4") (pintype "bidirectional"))
    )
    (net (code "270") (name "/LEDR1_26") (class "Default")
      (node (ref "LED101") (pin "4") (pinfunction "RED_4") (pintype "bidirectional"))
    )
    (net (code "271") (name "/LEDR1_27") (class "Default")
      (node (ref "LED105") (pin "4") (pinfunction "RED_4") (pintype "bidirectional"))
    )
    (net (code "272") (name "/LEDR1_28") (class "Default")
      (node (ref "LED109") (pin "4") (pinfunction "RED_4") (pintype "bidirectional"))
    )
    (net (code "273") (name "/LEDR1_29") (class "Default")
      (node (ref "LED113") (pin "4") (pinfunction "RED_4") (pintype "bidirectional"))
    )
    (net (code "274") (name "/LEDR1_30") (class "Default")
      (node (ref "LED117") (pin "4") (pinfunction "RED_4") (pintype "bidirectional"))
    )
    (net (code "275") (name "/LEDR2_1") (class "Default")
      (node (ref "LED2") (pin "4") (pinfunction "RED_4") (pintype "bidirectional"))
    )
    (net (code "276") (name "/LEDR2_2") (class "Default")
      (node (ref "LED6") (pin "4") (pinfunction "RED_4") (pintype "bidirectional"))
    )
    (net (code "277") (name "/LEDR2_3") (class "Default")
      (node (ref "LED10") (pin "4") (pinfunction "RED_4") (pintype "bidirectional"))
    )
    (net (code "278") (name "/LEDR2_4") (class "Default")
      (node (ref "LED14") (pin "4") (pinfunction "RED_4") (pintype "bidirectional"))
    )
    (net (code "279") (name "/LEDR2_5") (class "Default")
      (node (ref "LED18") (pin "4") (pinfunction "RED_4") (pintype "bidirectional"))
    )
    (net (code "280") (name "/LEDR2_6") (class "Default")
      (node (ref "LED22") (pin "4") (pinfunction "RED_4") (pintype "bidirectional"))
    )
    (net (code "281") (name "/LEDR2_7") (class "Default")
      (node (ref "LED26") (pin "4") (pinfunction "RED_4") (pintype "bidirectional"))
    )
    (net (code "282") (name "/LEDR2_8") (class "Default")
      (node (ref "LED30") (pin "4") (pinfunction "RED_4") (pintype "bidirectional"))
    )
    (net (code "283") (name "/LEDR2_9") (class "Default")
      (node (ref "LED34") (pin "4") (pinfunction "RED_4") (pintype "bidirectional"))
    )
    (net (code "284") (name "/LEDR2_10") (class "Default")
      (node (ref "LED38") (pin "4") (pinfunction "RED_4") (pintype "bidirectional"))
    )
    (net (code "285") (name "/LEDR2_11") (class "Default")
      (node (ref "LED42") (pin "4") (pinfunction "RED_4") (pintype "bidirectional"))
    )
    (net (code "286") (name "/LEDR2_12") (class "Default")
      (node (ref "LED46") (pin "4") (pinfunction "RED_4") (pintype "bidirectional"))
    )
    (net (code "287") (name "/LEDR2_13") (class "Default")
      (node (ref "LED50") (pin "4") (pinfunction "RED_4") (pintype "bidirectional"))
    )
    (net (code "288") (name "/LEDR2_14") (class "Default")
      (node (ref "LED54") (pin "4") (pinfunction "RED_4") (pintype "bidirectional"))
    )
    (net (code "289") (name "/LEDR2_15") (class "Default")
      (node (ref "LED58") (pin "4") (pinfunction "RED_4") (pintype "bidirectional"))
    )
    (net (code "290") (name "/LEDR2_16") (class "Default")
      (node (ref "LED62") (pin "4") (pinfunction "RED_4") (pintype "bidirectional"))
    )
    (net (code "291") (name "/LEDR2_17") (class "Default")
      (node (ref "LED66") (pin "4") (pinfunction "RED_4") (pintype "bidirectional"))
    )
    (net (code "292") (name "/LEDR2_18") (class "Default")
      (node (ref "LED70") (pin "4") (pinfunction "RED_4") (pintype "bidirectional"))
    )
    (net (code "293") (name "/LEDR2_19") (class "Default")
      (node (ref "LED74") (pin "4") (pinfunction "RED_4") (pintype "bidirectional"))
    )
    (net (code "294") (name "/LEDR2_20") (class "Default")
      (node (ref "LED78") (pin "4") (pinfunction "RED_4") (pintype "bidirectional"))
    )
    (net (code "295") (name "/LEDR2_21") (class "Default")
      (node (ref "LED82") (pin "4") (pinfunction "RED_4") (pintype "bidirectional"))
    )
    (net (code "296") (name "/LEDR2_22") (class "Default")
      (node (ref "LED86") (pin "4") (pinfunction "RED_4") (pintype "bidirectional"))
    )
    (net (code "297") (name "/LEDR2_23") (class "Default")
      (node (ref "LED90") (pin "4") (pinfunction "RED_4") (pintype "bidirectional"))
    )
    (net (code "298") (name "/LEDR2_24") (class "Default")
      (node (ref "LED94") (pin "4") (pinfunction "RED_4") (pintype "bidirectional"))
    )
    (net (code "299") (name "/LEDR2_25") (class "Default")
      (node (ref "LED98") (pin "4") (pinfunction "RED_4") (pintype "bidirectional"))
    )
    (net (code "300") (name "/LEDR2_26") (class "Default")
      (node (ref "LED102") (pin "4") (pinfunction "RED_4") (pintype "bidirectional"))
    )
    (net (code "301") (name "/LEDR2_27") (class "Default")
      (node (ref "LED106") (pin "4") (pinfunction "RED_4") (pintype "bidirectional"))
    )
    (net (code "302") (name "/LEDR2_28") (class "Default")
      (node (ref "LED110") (pin "4") (pinfunction "RED_4") (pintype "bidirectional"))
    )
    (net (code "303") (name "/LEDR2_29") (class "Default")
      (node (ref "LED114") (pin "4") (pinfunction "RED_4") (pintype "bidirectional"))
    )
    (net (code "304") (name "/LEDR2_30") (class "Default")
      (node (ref "LED118") (pin "4") (pinfunction "RED_4") (pintype "bidirectional"))
    )
    (net (code "305") (name "/LEDR3_1") (class "Default")
      (node (ref "LED3") (pin "4") (pinfunction "RED_4") (pintype "bidirectional"))
    )
    (net (code "306") (name "/LEDR3_2") (class "Default")
      (node (ref "LED7") (pin "4") (pinfunction "RED_4") (pintype "bidirectional"))
    )
    (net (code "307") (name "/LEDR3_3") (class "Default")
      (node (ref "LED11") (pin "4") (pinfunction "RED_4") (pintype "bidirectional"))
    )
    (net (code "308") (name "/LEDR3_4") (class "Default")
      (node (ref "LED15") (pin "4") (pinfunction "RED_4") (pintype "bidirectional"))
    )
    (net (code "309") (name "/LEDR3_5") (class "Default")
      (node (ref "LED19") (pin "4") (pinfunction "RED_4") (pintype "bidirectional"))
    )
    (net (code "310") (name "/LEDR3_6") (class "Default")
      (node (ref "LED23") (pin "4") (pinfunction "RED_4") (pintype "bidirectional"))
    )
    (net (code "311") (name "/LEDR3_7") (class "Default")
      (node (ref "LED27") (pin "4") (pinfunction "RED_4") (pintype "bidirectional"))
    )
    (net (code "312") (name "/LEDR3_8") (class "Default")
      (node (ref "LED31") (pin "4") (pinfunction "RED_4") (pintype "bidirectional"))
    )
    (net (code "313") (name "/LEDR3_9") (class "Default")
      (node (ref "LED35") (pin "4") (pinfunction "RED_4") (pintype "bidirectional"))
    )
    (net (code "314") (name "/LEDR3_10") (class "Default")
      (node (ref "LED39") (pin "4") (pinfunction "RED_4") (pintype "bidirectional"))
    )
    (net (code "315") (name "/LEDR3_11") (class "Default")
      (node (ref "LED43") (pin "4") (pinfunction "RED_4") (pintype "bidirectional"))
    )
    (net (code "316") (name "/LEDR3_12") (class "Default")
      (node (ref "LED47") (pin "4") (pinfunction "RED_4") (pintype "bidirectional"))
    )
    (net (code "317") (name "/LEDR3_13") (class "Default")
      (node (ref "LED51") (pin "4") (pinfunction "RED_4") (pintype "bidirectional"))
    )
    (net (code "318") (name "/LEDR3_14") (class "Default")
      (node (ref "LED55") (pin "4") (pinfunction "RED_4") (pintype "bidirectional"))
    )
    (net (code "319") (name "/LEDR3_15") (class "Default")
      (node (ref "LED59") (pin "4") (pinfunction "RED_4") (pintype "bidirectional"))
    )
    (net (code "320") (name "/LEDR3_16") (class "Default")
      (node (ref "LED63") (pin "4") (pinfunction "RED_4") (pintype "bidirectional"))
    )
    (net (code "321") (name "/LEDR3_17") (class "Default")
      (node (ref "LED67") (pin "4") (pinfunction "RED_4") (pintype "bidirectional"))
    )
    (net (code "322") (name "/LEDR3_18") (class "Default")
      (node (ref "LED71") (pin "4") (pinfunction "RED_4") (pintype "bidirectional"))
    )
    (net (code "323") (name "/LEDR3_19") (class "Default")
      (node (ref "LED75") (pin "4") (pinfunction "RED_4") (pintype "bidirectional"))
    )
    (net (code "324") (name "/LEDR3_20") (class "Default")
      (node (ref "LED79") (pin "4") (pinfunction "RED_4") (pintype "bidirectional"))
    )
    (net (code "325") (name "/LEDR3_21") (class "Default")
      (node (ref "LED83") (pin "4") (pinfunction "RED_4") (pintype "bidirectional"))
    )
    (net (code "326") (name "/LEDR3_22") (class "Default")
      (node (ref "LED87") (pin "4") (pinfunction "RED_4") (pintype "bidirectional"))
    )
    (net (code "327") (name "/LEDR3_23") (class "Default")
      (node (ref "LED91") (pin "4") (pinfunction "RED_4") (pintype "bidirectional"))
    )
    (net (code "328") (name "/LEDR3_24") (class "Default")
      (node (ref "LED95") (pin "4") (pinfunction "RED_4") (pintype "bidirectional"))
    )
    (net (code "329") (name "/LEDR3_25") (class "Default")
      (node (ref "LED99") (pin "4") (pinfunction "RED_4") (pintype "bidirectional"))
    )
    (net (code "330") (name "/LEDR3_26") (class "Default")
      (node (ref "LED103") (pin "4") (pinfunction "RED_4") (pintype "bidirectional"))
    )
    (net (code "331") (name "/LEDR3_27") (class "Default")
      (node (ref "LED107") (pin "4") (pinfunction "RED_4") (pintype "bidirectional"))
    )
    (net (code "332") (name "/LEDR3_28") (class "Default")
      (node (ref "LED111") (pin "4") (pinfunction "RED_4") (pintype "bidirectional"))
    )
    (net (code "333") (name "/LEDR3_29") (class "Default")
      (node (ref "LED115") (pin "4") (pinfunction "RED_4") (pintype "bidirectional"))
    )
    (net (code "334") (name "/LEDR3_30") (class "Default")
      (node (ref "LED119") (pin "4") (pinfunction "RED_4") (pintype "bidirectional"))
    )
    (net (code "335") (name "/LEDR4_1") (class "Default")
      (node (ref "LED4") (pin "4") (pinfunction "RED_4") (pintype "bidirectional"))
    )
    (net (code "336") (name "/LEDR4_2") (class "Default")
      (node (ref "LED8") (pin "4") (pinfunction "RED_4") (pintype "bidirectional"))
    )
    (net (code "337") (name "/LEDR4_3") (class "Default")
      (node (ref "LED12") (pin "4") (pinfunction "RED_4") (pintype "bidirectional"))
    )
    (net (code "338") (name "/LEDR4_4") (class "Default")
      (node (ref "LED16") (pin "4") (pinfunction "RED_4") (pintype "bidirectional"))
    )
    (net (code "339") (name "/LEDR4_5") (class "Default")
      (node (ref "LED20") (pin "4") (pinfunction "RED_4") (pintype "bidirectional"))
    )
    (net (code "340") (name "/LEDR4_6") (class "Default")
      (node (ref "LED24") (pin "4") (pinfunction "RED_4") (pintype "bidirectional"))
    )
    (net (code "341") (name "/LEDR4_7") (class "Default")
      (node (ref "LED28") (pin "4") (pinfunction "RED_4") (pintype "bidirectional"))
    )
    (net (code "342") (name "/LEDR4_8") (class "Default")
      (node (ref "LED32") (pin "4") (pinfunction "RED_4") (pintype "bidirectional"))
    )
    (net (code "343") (name "/LEDR4_9") (class "Default")
      (node (ref "LED36") (pin "4") (pinfunction "RED_4") (pintype "bidirectional"))
    )
    (net (code "344") (name "/LEDR4_10") (class "Default")
      (node (ref "LED40") (pin "4") (pinfunction "RED_4") (pintype "bidirectional"))
    )
    (net (code "345") (name "/LEDR4_11") (class "Default")
      (node (ref "LED44") (pin "4") (pinfunction "RED_4") (pintype "bidirectional"))
    )
    (net (code "346") (name "/LEDR4_12") (class "Default")
      (node (ref "LED48") (pin "4") (pinfunction "RED_4") (pintype "bidirectional"))
    )
    (net (code "347") (name "/LEDR4_13") (class "Default")
      (node (ref "LED52") (pin "4") (pinfunction "RED_4") (pintype "bidirectional"))
    )
    (net (code "348") (name "/LEDR4_14") (class "Default")
      (node (ref "LED56") (pin "4") (pinfunction "RED_4") (pintype "bidirectional"))
    )
    (net (code "349") (name "/LEDR4_15") (class "Default")
      (node (ref "LED60") (pin "4") (pinfunction "RED_4") (pintype "bidirectional"))
    )
    (net (code "350") (name "/LEDR4_16") (class "Default")
      (node (ref "LED64") (pin "4") (pinfunction "RED_4") (pintype "bidirectional"))
    )
    (net (code "351") (name "/LEDR4_17") (class "Default")
      (node (ref "LED68") (pin "4") (pinfunction "RED_4") (pintype "bidirectional"))
    )
    (net (code "352") (name "/LEDR4_18") (class "Default")
      (node (ref "LED72") (pin "4") (pinfunction "RED_4") (pintype "bidirectional"))
    )
    (net (code "353") (name "/LEDR4_19") (class "Default")
      (node (ref "LED76") (pin "4") (pinfunction "RED_4") (pintype "bidirectional"))
    )
    (net (code "354") (name "/LEDR4_20") (class "Default")
      (node (ref "LED80") (pin "4") (pinfunction "RED_4") (pintype "bidirectional"))
    )
    (net (code "355") (name "/LEDR4_21") (class "Default")
      (node (ref "LED84") (pin "4") (pinfunction "RED_4") (pintype "bidirectional"))
    )
    (net (code "356") (name "/LEDR4_22") (class "Default")
      (node (ref "LED88") (pin "4") (pinfunction "RED_4") (pintype "bidirectional"))
    )
    (net (code "357") (name "/LEDR4_23") (class "Default")
      (node (ref "LED92") (pin "4") (pinfunction "RED_4") (pintype "bidirectional"))
    )
    (net (code "358") (name "/LEDR4_24") (class "Default")
      (node (ref "LED96") (pin "4") (pinfunction "RED_4") (pintype "bidirectional"))
    )
    (net (code "359") (name "/LEDR4_25") (class "Default")
      (node (ref "LED100") (pin "4") (pinfunction "RED_4") (pintype "bidirectional"))
    )
    (net (code "360") (name "/LEDR4_26") (class "Default")
      (node (ref "LED104") (pin "4") (pinfunction "RED_4") (pintype "bidirectional"))
    )
    (net (code "361") (name "/LEDR4_27") (class "Default")
      (node (ref "LED108") (pin "4") (pinfunction "RED_4") (pintype "bidirectional"))
    )
    (net (code "362") (name "/LEDR4_28") (class "Default")
      (node (ref "LED112") (pin "4") (pinfunction "RED_4") (pintype "bidirectional"))
    )
    (net (code "363") (name "/LEDR4_29") (class "Default")
      (node (ref "LED116") (pin "4") (pinfunction "RED_4") (pintype "bidirectional"))
    )
    (net (code "364") (name "/LEDR4_30") (class "Default")
      (node (ref "LED120") (pin "4") (pinfunction "RED_4") (pintype "bidirectional"))
    )
    (net (code "365") (name "/SCLK") (class "Default")
      (node (ref "IC1") (pin "2") (pinfunction "SCLK_2") (pintype "bidirectional"))
      (node (ref "IC2") (pin "2") (pinfunction "SCLK_2") (pintype "bidirectional"))
      (node (ref "IC3") (pin "2") (pinfunction "SCLK_2") (pintype "bidirectional"))
      (node (ref "IC4") (pin "2") (pinfunction "SCLK_2") (pintype "bidirectional"))
      (node (ref "IC5") (pin "2") (pinfunction "SCLK_2") (pintype "bidirectional"))
      (node (ref "IC6") (pin "2") (pinfunction "SCLK_2") (pintype "bidirectional"))
      (node (ref "IC7") (pin "2") (pinfunction "SCLK_2") (pintype "bidirectional"))
      (node (ref "IC8") (pin "2") (pinfunction "SCLK_2") (pintype "bidirectional"))
    )
    (net (code "366") (name "/SIN_MCU") (class "Default")
      (node (ref "IC1") (pin "1") (pinfunction "SIN_1") (pintype "bidirectional"))
      (node (ref "IC2") (pin "1") (pinfunction "SIN_1") (pintype "bidirectional"))
      (node (ref "IC3") (pin "1") (pinfunction "SIN_1") (pintype "bidirectional"))
      (node (ref "IC4") (pin "1") (pinfunction "SIN_1") (pintype "bidirectional"))
      (node (ref "IC5") (pin "1") (pinfunction "SIN_1") (pintype "bidirectional"))
      (node (ref "IC6") (pin "1") (pinfunction "SIN_1") (pintype "bidirectional"))
      (node (ref "IC7") (pin "1") (pinfunction "SIN_1") (pintype "bidirectional"))
      (node (ref "IC8") (pin "1") (pinfunction "SIN_1") (pintype "bidirectional"))
    )
    (net (code "367") (name "/SOUT1") (class "Default")
      (node (ref "IC1") (pin "28") (pinfunction "SOUT_28") (pintype "bidirectional"))
      (node (ref "IC2") (pin "28") (pinfunction "SOUT_28") (pintype "bidirectional"))
      (node (ref "IC3") (pin "28") (pinfunction "SOUT_28") (pintype "bidirectional"))
      (node (ref "IC4") (pin "28") (pinfunction "SOUT_28") (pintype "bidirectional"))
      (node (ref "IC5") (pin "28") (pinfunction "SOUT_28") (pintype "bidirectional"))
      (node (ref "IC6") (pin "28") (pinfunction "SOUT_28") (pintype "bidirectional"))
      (node (ref "IC7") (pin "28") (pinfunction "SOUT_28") (pintype "bidirectional"))
      (node (ref "IC8") (pin "28") (pinfunction "SOUT_28") (pintype "bidirectional"))
    )
    (net (code "368") (name "unconnected-(IC1-OUTB0-Pad7)") (class "Default")
      (node (ref "IC1") (pin "7") (pinfunction "OUTB0_7") (pintype "bidirectional"))
    )
    (net (code "369") (name "unconnected-(IC1-OUTB1-Pad13)") (class "Default")
      (node (ref "IC1") (pin "13") (pinfunction "OUTB1_13") (pintype "bidirectional"))
    )
    (net (code "370") (name "unconnected-(IC1-OUTB2-Pad16)") (class "Default")
      (node (ref "IC1") (pin "16") (pinfunction "OUTB2_16") (pintype "bidirectional"))
    )
    (net (code "371") (name "unconnected-(IC1-OUTB3-Pad22)") (class "Default")
      (node (ref "IC1") (pin "22") (pinfunction "OUTB3_22") (pintype "bidirectional"))
    )
    (net (code "372") (name "unconnected-(IC1-OUTB4-Pad4)") (class "Default")
      (node (ref "IC1") (pin "4") (pinfunction "OUTB4_4") (pintype "bidirectional"))
    )
    (net (code "373") (name "unconnected-(IC1-OUTB5-Pad10)") (class "Default")
      (node (ref "IC1") (pin "10") (pinfunction "OUTB5_10") (pintype "bidirectional"))
    )
    (net (code "374") (name "unconnected-(IC1-OUTB6-Pad19)") (class "Default")
      (node (ref "IC1") (pin "19") (pinfunction "OUTB6_19") (pintype "bidirectional"))
    )
    (net (code "375") (name "unconnected-(IC1-OUTB7-Pad25)") (class "Default")
      (node (ref "IC1") (pin "25") (pinfunction "OUTB7_25") (pintype "bidirectional"))
    )
    (net (code "376") (name "unconnected-(IC1-OUTB8-Pad53)") (class "Default")
      (node (ref "IC1") (pin "53") (pinfunction "OUTB8_53") (pintype "bidirectional"))
    )
    (net (code "377") (name "unconnected-(IC1-OUTB9-Pad47)") (class "Default")
      (node (ref "IC1") (pin "47") (pinfunction "OUTB9_47") (pintype "bidirectional"))
    )
    (net (code "378") (name "unconnected-(IC1-OUTB10-Pad38)") (class "Default")
      (node (ref "IC1") (pin "38") (pinfunction "OUTB10_38") (pintype "bidirectional"))
    )
    (net (code "379") (name "unconnected-(IC1-OUTB11-Pad32)") (class "Default")
      (node (ref "IC1") (pin "32") (pinfunction "OUTB11_32") (pintype "bidirectional"))
    )
    (net (code "380") (name "unconnected-(IC1-OUTB12-Pad50)") (class "Default")
      (node (ref "IC1") (pin "50") (pinfunction "OUTB12_50") (pintype "bidirectional"))
    )
    (net (code "381") (name "unconnected-(IC1-OUTB13-Pad44)") (class "Default")
      (node (ref "IC1") (pin "44") (pinfunction "OUTB13_44") (pintype "bidirectional"))
    )
    (net (code "382") (name "unconnected-(IC1-OUTB14-Pad41)") (class "Default")
      (node (ref "IC1") (pin "41") (pinfunction "OUTB14_41") (pintype "bidirectional"))
    )
    (net (code "383") (name "unconnected-(IC1-OUTB15-Pad35)") (class "Default")
      (node (ref "IC1") (pin "35") (pinfunction "OUTB15_35") (pintype "bidirectional"))
    )
    (net (code "384") (name "unconnected-(IC1-OUTG0-Pad9)") (class "Default")
      (node (ref "IC1") (pin "9") (pinfunction "OUTG0_9") (pintype "bidirectional"))
    )
    (net (code "385") (name "unconnected-(IC1-OUTG1-Pad15)") (class "Default")
      (node (ref "IC1") (pin "15") (pinfunction "OUTG1_15") (pintype "bidirectional"))
    )
    (net (code "386") (name "unconnected-(IC1-OUTG2-Pad18)") (class "Default")
      (node (ref "IC1") (pin "18") (pinfunction "OUTG2_18") (pintype "bidirectional"))
    )
    (net (code "387") (name "unconnected-(IC1-OUTG3-Pad24)") (class "Default")
      (node (ref "IC1") (pin "24") (pinfunction "OUTG3_24") (pintype "bidirectional"))
    )
    (net (code "388") (name "unconnected-(IC1-OUTG4-Pad6)") (class "Default")
      (node (ref "IC1") (pin "6") (pinfunction "OUTG4_6") (pintype "bidirectional"))
    )
    (net (code "389") (name "unconnected-(IC1-OUTG5-Pad12)") (class "Default")
      (node (ref "IC1") (pin "12") (pinfunction "OUTG5_12") (pintype "bidirectional"))
    )
    (net (code "390") (name "unconnected-(IC1-OUTG6-Pad21)") (class "Default")
      (node (ref "IC1") (pin "21") (pinfunction "OUTG6_21") (pintype "bidirectional"))
    )
    (net (code "391") (name "unconnected-(IC1-OUTG7-Pad27)") (class "Default")
      (node (ref "IC1") (pin "27") (pinfunction "OUTG7_27") (pintype "bidirectional"))
    )
    (net (code "392") (name "unconnected-(IC1-OUTG8-Pad51)") (class "Default")
      (node (ref "IC1") (pin "51") (pinfunction "OUTG8_51") (pintype "bidirectional"))
    )
    (net (code "393") (name "unconnected-(IC1-OUTG9-Pad45)") (class "Default")
      (node (ref "IC1") (pin "45") (pinfunction "OUTG9_45") (pintype "bidirectional"))
    )
    (net (code "394") (name "unconnected-(IC1-OUTG10-Pad36)") (class "Default")
      (node (ref "IC1") (pin "36") (pinfunction "OUTG10_36") (pintype "bidirectional"))
    )
    (net (code "395") (name "unconnected-(IC1-OUTG11-Pad30)") (class "Default")
      (node (ref "IC1") (pin "30") (pinfunction "OUTG11_30") (pintype "bidirectional"))
    )
    (net (code "396") (name "unconnected-(IC1-OUTG12-Pad48)") (class "Default")
      (node (ref "IC1") (pin "48") (pinfunction "OUTG12_48") (pintype "bidirectional"))
    )
    (net (code "397") (name "unconnected-(IC1-OUTG13-Pad42)") (class "Default")
      (node (ref "IC1") (pin "42") (pinfunction "OUTG13_42") (pintype "bidirectional"))
    )
    (net (code "398") (name "unconnected-(IC1-OUTG14-Pad39)") (class "Default")
      (node (ref "IC1") (pin "39") (pinfunction "OUTG14_39") (pintype "bidirectional"))
    )
    (net (code "399") (name "unconnected-(IC1-OUTG15-Pad33)") (class "Default")
      (node (ref "IC1") (pin "33") (pinfunction "OUTG15_33") (pintype "bidirectional"))
    )
    (net (code "400") (name "unconnected-(IC1-OUTR0-Pad8)") (class "Default")
      (node (ref "IC1") (pin "8") (pinfunction "OUTR0_8") (pintype "bidirectional"))
    )
    (net (code "401") (name "unconnected-(IC1-OUTR1-Pad14)") (class "Default")
      (node (ref "IC1") (pin "14") (pinfunction "OUTR1_14") (pintype "bidirectional"))
    )
    (net (code "402") (name "unconnected-(IC1-OUTR2-Pad17)") (class "Default")
      (node (ref "IC1") (pin "17") (pinfunction "OUTR2_17") (pintype "bidirectional"))
    )
    (net (code "403") (name "unconnected-(IC1-OUTR3-Pad23)") (class "Default")
      (node (ref "IC1") (pin "23") (pinfunction "OUTR3_23") (pintype "bidirectional"))
    )
    (net (code "404") (name "unconnected-(IC1-OUTR4-Pad5)") (class "Default")
      (node (ref "IC1") (pin "5") (pinfunction "OUTR4_5") (pintype "bidirectional"))
    )
    (net (code "405") (name "unconnected-(IC1-OUTR5-Pad11)") (class "Default")
      (node (ref "IC1") (pin "11") (pinfunction "OUTR5_11") (pintype "bidirectional"))
    )
    (net (code "406") (name "unconnected-(IC1-OUTR6-Pad20)") (class "Default")
      (node (ref "IC1") (pin "20") (pinfunction "OUTR6_20") (pintype "bidirectional"))
    )
    (net (code "407") (name "unconnected-(IC1-OUTR7-Pad26)") (class "Default")
      (node (ref "IC1") (pin "26") (pinfunction "OUTR7_26") (pintype "bidirectional"))
    )
    (net (code "408") (name "unconnected-(IC1-OUTR8-Pad52)") (class "Default")
      (node (ref "IC1") (pin "52") (pinfunction "OUTR8_52") (pintype "bidirectional"))
    )
    (net (code "409") (name "unconnected-(IC1-OUTR9-Pad46)") (class "Default")
      (node (ref "IC1") (pin "46") (pinfunction "OUTR9_46") (pintype "bidirectional"))
    )
    (net (code "410") (name "unconnected-(IC1-OUTR10-Pad37)") (class "Default")
      (node (ref "IC1") (pin "37") (pinfunction "OUTR10_37") (pintype "bidirectional"))
    )
    (net (code "411") (name "unconnected-(IC1-OUTR11-Pad31)") (class "Default")
      (node (ref "IC1") (pin "31") (pinfunction "OUTR11_31") (pintype "bidirectional"))
    )
    (net (code "412") (name "unconnected-(IC1-OUTR12-Pad49)") (class "Default")
      (node (ref "IC1") (pin "49") (pinfunction "OUTR12_49") (pintype "bidirectional"))
    )
    (net (code "413") (name "unconnected-(IC1-OUTR13-Pad43)") (class "Default")
      (node (ref "IC1") (pin "43") (pinfunction "OUTR13_43") (pintype "bidirectional"))
    )
    (net (code "414") (name "unconnected-(IC1-OUTR14-Pad40)") (class "Default")
      (node (ref "IC1") (pin "40") (pinfunction "OUTR14_40") (pintype "bidirectional"))
    )
    (net (code "415") (name "unconnected-(IC1-OUTR15-Pad34)") (class "Default")
      (node (ref "IC1") (pin "34") (pinfunction "OUTR15_34") (pintype "bidirectional"))
    )
    (net (code "416") (name "unconnected-(IC2-OUTB0-Pad7)") (class "Default")
      (node (ref "IC2") (pin "7") (pinfunction "OUTB0_7") (pintype "bidirectional"))
    )
    (net (code "417") (name "unconnected-(IC2-OUTB1-Pad13)") (class "Default")
      (node (ref "IC2") (pin "13") (pinfunction "OUTB1_13") (pintype "bidirectional"))
    )
    (net (code "418") (name "unconnected-(IC2-OUTB2-Pad16)") (class "Default")
      (node (ref "IC2") (pin "16") (pinfunction "OUTB2_16") (pintype "bidirectional"))
    )
    (net (code "419") (name "unconnected-(IC2-OUTB3-Pad22)") (class "Default")
      (node (ref "IC2") (pin "22") (pinfunction "OUTB3_22") (pintype "bidirectional"))
    )
    (net (code "420") (name "unconnected-(IC2-OUTB4-Pad4)") (class "Default")
      (node (ref "IC2") (pin "4") (pinfunction "OUTB4_4") (pintype "bidirectional"))
    )
    (net (code "421") (name "unconnected-(IC2-OUTB5-Pad10)") (class "Default")
      (node (ref "IC2") (pin "10") (pinfunction "OUTB5_10") (pintype "bidirectional"))
    )
    (net (code "422") (name "unconnected-(IC2-OUTB6-Pad19)") (class "Default")
      (node (ref "IC2") (pin "19") (pinfunction "OUTB6_19") (pintype "bidirectional"))
    )
    (net (code "423") (name "unconnected-(IC2-OUTB7-Pad25)") (class "Default")
      (node (ref "IC2") (pin "25") (pinfunction "OUTB7_25") (pintype "bidirectional"))
    )
    (net (code "424") (name "unconnected-(IC2-OUTB8-Pad53)") (class "Default")
      (node (ref "IC2") (pin "53") (pinfunction "OUTB8_53") (pintype "bidirectional"))
    )
    (net (code "425") (name "unconnected-(IC2-OUTB9-Pad47)") (class "Default")
      (node (ref "IC2") (pin "47") (pinfunction "OUTB9_47") (pintype "bidirectional"))
    )
    (net (code "426") (name "unconnected-(IC2-OUTB10-Pad38)") (class "Default")
      (node (ref "IC2") (pin "38") (pinfunction "OUTB10_38") (pintype "bidirectional"))
    )
    (net (code "427") (name "unconnected-(IC2-OUTB11-Pad32)") (class "Default")
      (node (ref "IC2") (pin "32") (pinfunction "OUTB11_32") (pintype "bidirectional"))
    )
    (net (code "428") (name "unconnected-(IC2-OUTB12-Pad50)") (class "Default")
      (node (ref "IC2") (pin "50") (pinfunction "OUTB12_50") (pintype "bidirectional"))
    )
    (net (code "429") (name "unconnected-(IC2-OUTB13-Pad44)") (class "Default")
      (node (ref "IC2") (pin "44") (pinfunction "OUTB13_44") (pintype "bidirectional"))
    )
    (net (code "430") (name "unconnected-(IC2-OUTB14-Pad41)") (class "Default")
      (node (ref "IC2") (pin "41") (pinfunction "OUTB14_41") (pintype "bidirectional"))
    )
    (net (code "431") (name "unconnected-(IC2-OUTB15-Pad35)") (class "Default")
      (node (ref "IC2") (pin "35") (pinfunction "OUTB15_35") (pintype "bidirectional"))
    )
    (net (code "432") (name "unconnected-(IC2-OUTG0-Pad9)") (class "Default")
      (node (ref "IC2") (pin "9") (pinfunction "OUTG0_9") (pintype "bidirectional"))
    )
    (net (code "433") (name "unconnected-(IC2-OUTG1-Pad15)") (class "Default")
      (node (ref "IC2") (pin "15") (pinfunction "OUTG1_15") (pintype "bidirectional"))
    )
    (net (code "434") (name "unconnected-(IC2-OUTG2-Pad18)") (class "Default")
      (node (ref "IC2") (pin "18") (pinfunction "OUTG2_18") (pintype "bidirectional"))
    )
    (net (code "435") (name "unconnected-(IC2-OUTG3-Pad24)") (class "Default")
      (node (ref "IC2") (pin "24") (pinfunction "OUTG3_24") (pintype "bidirectional"))
    )
    (net (code "436") (name "unconnected-(IC2-OUTG4-Pad6)") (class "Default")
      (node (ref "IC2") (pin "6") (pinfunction "OUTG4_6") (pintype "bidirectional"))
    )
    (net (code "437") (name "unconnected-(IC2-OUTG5-Pad12)") (class "Default")
      (node (ref "IC2") (pin "12") (pinfunction "OUTG5_12") (pintype "bidirectional"))
    )
    (net (code "438") (name "unconnected-(IC2-OUTG6-Pad21)") (class "Default")
      (node (ref "IC2") (pin "21") (pinfunction "OUTG6_21") (pintype "bidirectional"))
    )
    (net (code "439") (name "unconnected-(IC2-OUTG7-Pad27)") (class "Default")
      (node (ref "IC2") (pin "27") (pinfunction "OUTG7_27") (pintype "bidirectional"))
    )
    (net (code "440") (name "unconnected-(IC2-OUTG8-Pad51)") (class "Default")
      (node (ref "IC2") (pin "51") (pinfunction "OUTG8_51") (pintype "bidirectional"))
    )
    (net (code "441") (name "unconnected-(IC2-OUTG9-Pad45)") (class "Default")
      (node (ref "IC2") (pin "45") (pinfunction "OUTG9_45") (pintype "bidirectional"))
    )
    (net (code "442") (name "unconnected-(IC2-OUTG10-Pad36)") (class "Default")
      (node (ref "IC2") (pin "36") (pinfunction "OUTG10_36") (pintype "bidirectional"))
    )
    (net (code "443") (name "unconnected-(IC2-OUTG11-Pad30)") (class "Default")
      (node (ref "IC2") (pin "30") (pinfunction "OUTG11_30") (pintype "bidirectional"))
    )
    (net (code "444") (name "unconnected-(IC2-OUTG12-Pad48)") (class "Default")
      (node (ref "IC2") (pin "48") (pinfunction "OUTG12_48") (pintype "bidirectional"))
    )
    (net (code "445") (name "unconnected-(IC2-OUTG13-Pad42)") (class "Default")
      (node (ref "IC2") (pin "42") (pinfunction "OUTG13_42") (pintype "bidirectional"))
    )
    (net (code "446") (name "unconnected-(IC2-OUTG14-Pad39)") (class "Default")
      (node (ref "IC2") (pin "39") (pinfunction "OUTG14_39") (pintype "bidirectional"))
    )
    (net (code "447") (name "unconnected-(IC2-OUTG15-Pad33)") (class "Default")
      (node (ref "IC2") (pin "33") (pinfunction "OUTG15_33") (pintype "bidirectional"))
    )
    (net (code "448") (name "unconnected-(IC2-OUTR0-Pad8)") (class "Default")
      (node (ref "IC2") (pin "8") (pinfunction "OUTR0_8") (pintype "bidirectional"))
    )
    (net (code "449") (name "unconnected-(IC2-OUTR1-Pad14)") (class "Default")
      (node (ref "IC2") (pin "14") (pinfunction "OUTR1_14") (pintype "bidirectional"))
    )
    (net (code "450") (name "unconnected-(IC2-OUTR2-Pad17)") (class "Default")
      (node (ref "IC2") (pin "17") (pinfunction "OUTR2_17") (pintype "bidirectional"))
    )
    (net (code "451") (name "unconnected-(IC2-OUTR3-Pad23)") (class "Default")
      (node (ref "IC2") (pin "23") (pinfunction "OUTR3_23") (pintype "bidirectional"))
    )
    (net (code "452") (name "unconnected-(IC2-OUTR4-Pad5)") (class "Default")
      (node (ref "IC2") (pin "5") (pinfunction "OUTR4_5") (pintype "bidirectional"))
    )
    (net (code "453") (name "unconnected-(IC2-OUTR5-Pad11)") (class "Default")
      (node (ref "IC2") (pin "11") (pinfunction "OUTR5_11") (pintype "bidirectional"))
    )
    (net (code "454") (name "unconnected-(IC2-OUTR6-Pad20)") (class "Default")
      (node (ref "IC2") (pin "20") (pinfunction "OUTR6_20") (pintype "bidirectional"))
    )
    (net (code "455") (name "unconnected-(IC2-OUTR7-Pad26)") (class "Default")
      (node (ref "IC2") (pin "26") (pinfunction "OUTR7_26") (pintype "bidirectional"))
    )
    (net (code "456") (name "unconnected-(IC2-OUTR8-Pad52)") (class "Default")
      (node (ref "IC2") (pin "52") (pinfunction "OUTR8_52") (pintype "bidirectional"))
    )
    (net (code "457") (name "unconnected-(IC2-OUTR9-Pad46)") (class "Default")
      (node (ref "IC2") (pin "46") (pinfunction "OUTR9_46") (pintype "bidirectional"))
    )
    (net (code "458") (name "unconnected-(IC2-OUTR10-Pad37)") (class "Default")
      (node (ref "IC2") (pin "37") (pinfunction "OUTR10_37") (pintype "bidirectional"))
    )
    (net (code "459") (name "unconnected-(IC2-OUTR11-Pad31)") (class "Default")
      (node (ref "IC2") (pin "31") (pinfunction "OUTR11_31") (pintype "bidirectional"))
    )
    (net (code "460") (name "unconnected-(IC2-OUTR12-Pad49)") (class "Default")
      (node (ref "IC2") (pin "49") (pinfunction "OUTR12_49") (pintype "bidirectional"))
    )
    (net (code "461") (name "unconnected-(IC2-OUTR13-Pad43)") (class "Default")
      (node (ref "IC2") (pin "43") (pinfunction "OUTR13_43") (pintype "bidirectional"))
    )
    (net (code "462") (name "unconnected-(IC2-OUTR14-Pad40)") (class "Default")
      (node (ref "IC2") (pin "40") (pinfunction "OUTR14_40") (pintype "bidirectional"))
    )
    (net (code "463") (name "unconnected-(IC2-OUTR15-Pad34)") (class "Default")
      (node (ref "IC2") (pin "34") (pinfunction "OUTR15_34") (pintype "bidirectional"))
    )
    (net (code "464") (name "unconnected-(IC3-OUTB0-Pad7)") (class "Default")
      (node (ref "IC3") (pin "7") (pinfunction "OUTB0_7") (pintype "bidirectional"))
    )
    (net (code "465") (name "unconnected-(IC3-OUTB1-Pad13)") (class "Default")
      (node (ref "IC3") (pin "13") (pinfunction "OUTB1_13") (pintype "bidirectional"))
    )
    (net (code "466") (name "unconnected-(IC3-OUTB2-Pad16)") (class "Default")
      (node (ref "IC3") (pin "16") (pinfunction "OUTB2_16") (pintype "bidirectional"))
    )
    (net (code "467") (name "unconnected-(IC3-OUTB3-Pad22)") (class "Default")
      (node (ref "IC3") (pin "22") (pinfunction "OUTB3_22") (pintype "bidirectional"))
    )
    (net (code "468") (name "unconnected-(IC3-OUTB4-Pad4)") (class "Default")
      (node (ref "IC3") (pin "4") (pinfunction "OUTB4_4") (pintype "bidirectional"))
    )
    (net (code "469") (name "unconnected-(IC3-OUTB5-Pad10)") (class "Default")
      (node (ref "IC3") (pin "10") (pinfunction "OUTB5_10") (pintype "bidirectional"))
    )
    (net (code "470") (name "unconnected-(IC3-OUTB6-Pad19)") (class "Default")
      (node (ref "IC3") (pin "19") (pinfunction "OUTB6_19") (pintype "bidirectional"))
    )
    (net (code "471") (name "unconnected-(IC3-OUTB7-Pad25)") (class "Default")
      (node (ref "IC3") (pin "25") (pinfunction "OUTB7_25") (pintype "bidirectional"))
    )
    (net (code "472") (name "unconnected-(IC3-OUTB8-Pad53)") (class "Default")
      (node (ref "IC3") (pin "53") (pinfunction "OUTB8_53") (pintype "bidirectional"))
    )
    (net (code "473") (name "unconnected-(IC3-OUTB9-Pad47)") (class "Default")
      (node (ref "IC3") (pin "47") (pinfunction "OUTB9_47") (pintype "bidirectional"))
    )
    (net (code "474") (name "unconnected-(IC3-OUTB10-Pad38)") (class "Default")
      (node (ref "IC3") (pin "38") (pinfunction "OUTB10_38") (pintype "bidirectional"))
    )
    (net (code "475") (name "unconnected-(IC3-OUTB11-Pad32)") (class "Default")
      (node (ref "IC3") (pin "32") (pinfunction "OUTB11_32") (pintype "bidirectional"))
    )
    (net (code "476") (name "unconnected-(IC3-OUTB12-Pad50)") (class "Default")
      (node (ref "IC3") (pin "50") (pinfunction "OUTB12_50") (pintype "bidirectional"))
    )
    (net (code "477") (name "unconnected-(IC3-OUTB13-Pad44)") (class "Default")
      (node (ref "IC3") (pin "44") (pinfunction "OUTB13_44") (pintype "bidirectional"))
    )
    (net (code "478") (name "unconnected-(IC3-OUTB14-Pad41)") (class "Default")
      (node (ref "IC3") (pin "41") (pinfunction "OUTB14_41") (pintype "bidirectional"))
    )
    (net (code "479") (name "unconnected-(IC3-OUTB15-Pad35)") (class "Default")
      (node (ref "IC3") (pin "35") (pinfunction "OUTB15_35") (pintype "bidirectional"))
    )
    (net (code "480") (name "unconnected-(IC3-OUTG0-Pad9)") (class "Default")
      (node (ref "IC3") (pin "9") (pinfunction "OUTG0_9") (pintype "bidirectional"))
    )
    (net (code "481") (name "unconnected-(IC3-OUTG1-Pad15)") (class "Default")
      (node (ref "IC3") (pin "15") (pinfunction "OUTG1_15") (pintype "bidirectional"))
    )
    (net (code "482") (name "unconnected-(IC3-OUTG2-Pad18)") (class "Default")
      (node (ref "IC3") (pin "18") (pinfunction "OUTG2_18") (pintype "bidirectional"))
    )
    (net (code "483") (name "unconnected-(IC3-OUTG3-Pad24)") (class "Default")
      (node (ref "IC3") (pin "24") (pinfunction "OUTG3_24") (pintype "bidirectional"))
    )
    (net (code "484") (name "unconnected-(IC3-OUTG4-Pad6)") (class "Default")
      (node (ref "IC3") (pin "6") (pinfunction "OUTG4_6") (pintype "bidirectional"))
    )
    (net (code "485") (name "unconnected-(IC3-OUTG5-Pad12)") (class "Default")
      (node (ref "IC3") (pin "12") (pinfunction "OUTG5_12") (pintype "bidirectional"))
    )
    (net (code "486") (name "unconnected-(IC3-OUTG6-Pad21)") (class "Default")
      (node (ref "IC3") (pin "21") (pinfunction "OUTG6_21") (pintype "bidirectional"))
    )
    (net (code "487") (name "unconnected-(IC3-OUTG7-Pad27)") (class "Default")
      (node (ref "IC3") (pin "27") (pinfunction "OUTG7_27") (pintype "bidirectional"))
    )
    (net (code "488") (name "unconnected-(IC3-OUTG8-Pad51)") (class "Default")
      (node (ref "IC3") (pin "51") (pinfunction "OUTG8_51") (pintype "bidirectional"))
    )
    (net (code "489") (name "unconnected-(IC3-OUTG9-Pad45)") (class "Default")
      (node (ref "IC3") (pin "45") (pinfunction "OUTG9_45") (pintype "bidirectional"))
    )
    (net (code "490") (name "unconnected-(IC3-OUTG10-Pad36)") (class "Default")
      (node (ref "IC3") (pin "36") (pinfunction "OUTG10_36") (pintype "bidirectional"))
    )
    (net (code "491") (name "unconnected-(IC3-OUTG11-Pad30)") (class "Default")
      (node (ref "IC3") (pin "30") (pinfunction "OUTG11_30") (pintype "bidirectional"))
    )
    (net (code "492") (name "unconnected-(IC3-OUTG12-Pad48)") (class "Default")
      (node (ref "IC3") (pin "48") (pinfunction "OUTG12_48") (pintype "bidirectional"))
    )
    (net (code "493") (name "unconnected-(IC3-OUTG13-Pad42)") (class "Default")
      (node (ref "IC3") (pin "42") (pinfunction "OUTG13_42") (pintype "bidirectional"))
    )
    (net (code "494") (name "unconnected-(IC3-OUTG14-Pad39)") (class "Default")
      (node (ref "IC3") (pin "39") (pinfunction "OUTG14_39") (pintype "bidirectional"))
    )
    (net (code "495") (name "unconnected-(IC3-OUTG15-Pad33)") (class "Default")
      (node (ref "IC3") (pin "33") (pinfunction "OUTG15_33") (pintype "bidirectional"))
    )
    (net (code "496") (name "unconnected-(IC3-OUTR0-Pad8)") (class "Default")
      (node (ref "IC3") (pin "8") (pinfunction "OUTR0_8") (pintype "bidirectional"))
    )
    (net (code "497") (name "unconnected-(IC3-OUTR1-Pad14)") (class "Default")
      (node (ref "IC3") (pin "14") (pinfunction "OUTR1_14") (pintype "bidirectional"))
    )
    (net (code "498") (name "unconnected-(IC3-OUTR2-Pad17)") (class "Default")
      (node (ref "IC3") (pin "17") (pinfunction "OUTR2_17") (pintype "bidirectional"))
    )
    (net (code "499") (name "unconnected-(IC3-OUTR3-Pad23)") (class "Default")
      (node (ref "IC3") (pin "23") (pinfunction "OUTR3_23") (pintype "bidirectional"))
    )
    (net (code "500") (name "unconnected-(IC3-OUTR4-Pad5)") (class "Default")
      (node (ref "IC3") (pin "5") (pinfunction "OUTR4_5") (pintype "bidirectional"))
    )
    (net (code "501") (name "unconnected-(IC3-OUTR5-Pad11)") (class "Default")
      (node (ref "IC3") (pin "11") (pinfunction "OUTR5_11") (pintype "bidirectional"))
    )
    (net (code "502") (name "unconnected-(IC3-OUTR6-Pad20)") (class "Default")
      (node (ref "IC3") (pin "20") (pinfunction "OUTR6_20") (pintype "bidirectional"))
    )
    (net (code "503") (name "unconnected-(IC3-OUTR7-Pad26)") (class "Default")
      (node (ref "IC3") (pin "26") (pinfunction "OUTR7_26") (pintype "bidirectional"))
    )
    (net (code "504") (name "unconnected-(IC3-OUTR8-Pad52)") (class "Default")
      (node (ref "IC3") (pin "52") (pinfunction "OUTR8_52") (pintype "bidirectional"))
    )
    (net (code "505") (name "unconnected-(IC3-OUTR9-Pad46)") (class "Default")
      (node (ref "IC3") (pin "46") (pinfunction "OUTR9_46") (pintype "bidirectional"))
    )
    (net (code "506") (name "unconnected-(IC3-OUTR10-Pad37)") (class "Default")
      (node (ref "IC3") (pin "37") (pinfunction "OUTR10_37") (pintype "bidirectional"))
    )
    (net (code "507") (name "unconnected-(IC3-OUTR11-Pad31)") (class "Default")
      (node (ref "IC3") (pin "31") (pinfunction "OUTR11_31") (pintype "bidirectional"))
    )
    (net (code "508") (name "unconnected-(IC3-OUTR12-Pad49)") (class "Default")
      (node (ref "IC3") (pin "49") (pinfunction "OUTR12_49") (pintype "bidirectional"))
    )
    (net (code "509") (name "unconnected-(IC3-OUTR13-Pad43)") (class "Default")
      (node (ref "IC3") (pin "43") (pinfunction "OUTR13_43") (pintype "bidirectional"))
    )
    (net (code "510") (name "unconnected-(IC3-OUTR14-Pad40)") (class "Default")
      (node (ref "IC3") (pin "40") (pinfunction "OUTR14_40") (pintype "bidirectional"))
    )
    (net (code "511") (name "unconnected-(IC3-OUTR15-Pad34)") (class "Default")
      (node (ref "IC3") (pin "34") (pinfunction "OUTR15_34") (pintype "bidirectional"))
    )
    (net (code "512") (name "unconnected-(IC4-OUTB0-Pad7)") (class "Default")
      (node (ref "IC4") (pin "7") (pinfunction "OUTB0_7") (pintype "bidirectional"))
    )
    (net (code "513") (name "unconnected-(IC4-OUTB1-Pad13)") (class "Default")
      (node (ref "IC4") (pin "13") (pinfunction "OUTB1_13") (pintype "bidirectional"))
    )
    (net (code "514") (name "unconnected-(IC4-OUTB2-Pad16)") (class "Default")
      (node (ref "IC4") (pin "16") (pinfunction "OUTB2_16") (pintype "bidirectional"))
    )
    (net (code "515") (name "unconnected-(IC4-OUTB3-Pad22)") (class "Default")
      (node (ref "IC4") (pin "22") (pinfunction "OUTB3_22") (pintype "bidirectional"))
    )
    (net (code "516") (name "unconnected-(IC4-OUTB4-Pad4)") (class "Default")
      (node (ref "IC4") (pin "4") (pinfunction "OUTB4_4") (pintype "bidirectional"))
    )
    (net (code "517") (name "unconnected-(IC4-OUTB5-Pad10)") (class "Default")
      (node (ref "IC4") (pin "10") (pinfunction "OUTB5_10") (pintype "bidirectional"))
    )
    (net (code "518") (name "unconnected-(IC4-OUTB6-Pad19)") (class "Default")
      (node (ref "IC4") (pin "19") (pinfunction "OUTB6_19") (pintype "bidirectional"))
    )
    (net (code "519") (name "unconnected-(IC4-OUTB7-Pad25)") (class "Default")
      (node (ref "IC4") (pin "25") (pinfunction "OUTB7_25") (pintype "bidirectional"))
    )
    (net (code "520") (name "unconnected-(IC4-OUTB8-Pad53)") (class "Default")
      (node (ref "IC4") (pin "53") (pinfunction "OUTB8_53") (pintype "bidirectional"))
    )
    (net (code "521") (name "unconnected-(IC4-OUTB9-Pad47)") (class "Default")
      (node (ref "IC4") (pin "47") (pinfunction "OUTB9_47") (pintype "bidirectional"))
    )
    (net (code "522") (name "unconnected-(IC4-OUTB10-Pad38)") (class "Default")
      (node (ref "IC4") (pin "38") (pinfunction "OUTB10_38") (pintype "bidirectional"))
    )
    (net (code "523") (name "unconnected-(IC4-OUTB11-Pad32)") (class "Default")
      (node (ref "IC4") (pin "32") (pinfunction "OUTB11_32") (pintype "bidirectional"))
    )
    (net (code "524") (name "unconnected-(IC4-OUTB12-Pad50)") (class "Default")
      (node (ref "IC4") (pin "50") (pinfunction "OUTB12_50") (pintype "bidirectional"))
    )
    (net (code "525") (name "unconnected-(IC4-OUTB13-Pad44)") (class "Default")
      (node (ref "IC4") (pin "44") (pinfunction "OUTB13_44") (pintype "bidirectional"))
    )
    (net (code "526") (name "unconnected-(IC4-OUTB14-Pad41)") (class "Default")
      (node (ref "IC4") (pin "41") (pinfunction "OUTB14_41") (pintype "bidirectional"))
    )
    (net (code "527") (name "unconnected-(IC4-OUTB15-Pad35)") (class "Default")
      (node (ref "IC4") (pin "35") (pinfunction "OUTB15_35") (pintype "bidirectional"))
    )
    (net (code "528") (name "unconnected-(IC4-OUTG0-Pad9)") (class "Default")
      (node (ref "IC4") (pin "9") (pinfunction "OUTG0_9") (pintype "bidirectional"))
    )
    (net (code "529") (name "unconnected-(IC4-OUTG1-Pad15)") (class "Default")
      (node (ref "IC4") (pin "15") (pinfunction "OUTG1_15") (pintype "bidirectional"))
    )
    (net (code "530") (name "unconnected-(IC4-OUTG2-Pad18)") (class "Default")
      (node (ref "IC4") (pin "18") (pinfunction "OUTG2_18") (pintype "bidirectional"))
    )
    (net (code "531") (name "unconnected-(IC4-OUTG3-Pad24)") (class "Default")
      (node (ref "IC4") (pin "24") (pinfunction "OUTG3_24") (pintype "bidirectional"))
    )
    (net (code "532") (name "unconnected-(IC4-OUTG4-Pad6)") (class "Default")
      (node (ref "IC4") (pin "6") (pinfunction "OUTG4_6") (pintype "bidirectional"))
    )
    (net (code "533") (name "unconnected-(IC4-OUTG5-Pad12)") (class "Default")
      (node (ref "IC4") (pin "12") (pinfunction "OUTG5_12") (pintype "bidirectional"))
    )
    (net (code "534") (name "unconnected-(IC4-OUTG6-Pad21)") (class "Default")
      (node (ref "IC4") (pin "21") (pinfunction "OUTG6_21") (pintype "bidirectional"))
    )
    (net (code "535") (name "unconnected-(IC4-OUTG7-Pad27)") (class "Default")
      (node (ref "IC4") (pin "27") (pinfunction "OUTG7_27") (pintype "bidirectional"))
    )
    (net (code "536") (name "unconnected-(IC4-OUTG8-Pad51)") (class "Default")
      (node (ref "IC4") (pin "51") (pinfunction "OUTG8_51") (pintype "bidirectional"))
    )
    (net (code "537") (name "unconnected-(IC4-OUTG9-Pad45)") (class "Default")
      (node (ref "IC4") (pin "45") (pinfunction "OUTG9_45") (pintype "bidirectional"))
    )
    (net (code "538") (name "unconnected-(IC4-OUTG10-Pad36)") (class "Default")
      (node (ref "IC4") (pin "36") (pinfunction "OUTG10_36") (pintype "bidirectional"))
    )
    (net (code "539") (name "unconnected-(IC4-OUTG11-Pad30)") (class "Default")
      (node (ref "IC4") (pin "30") (pinfunction "OUTG11_30") (pintype "bidirectional"))
    )
    (net (code "540") (name "unconnected-(IC4-OUTG12-Pad48)") (class "Default")
      (node (ref "IC4") (pin "48") (pinfunction "OUTG12_48") (pintype "bidirectional"))
    )
    (net (code "541") (name "unconnected-(IC4-OUTG13-Pad42)") (class "Default")
      (node (ref "IC4") (pin "42") (pinfunction "OUTG13_42") (pintype "bidirectional"))
    )
    (net (code "542") (name "unconnected-(IC4-OUTG14-Pad39)") (class "Default")
      (node (ref "IC4") (pin "39") (pinfunction "OUTG14_39") (pintype "bidirectional"))
    )
    (net (code "543") (name "unconnected-(IC4-OUTG15-Pad33)") (class "Default")
      (node (ref "IC4") (pin "33") (pinfunction "OUTG15_33") (pintype "bidirectional"))
    )
    (net (code "544") (name "unconnected-(IC4-OUTR0-Pad8)") (class "Default")
      (node (ref "IC4") (pin "8") (pinfunction "OUTR0_8") (pintype "bidirectional"))
    )
    (net (code "545") (name "unconnected-(IC4-OUTR1-Pad14)") (class "Default")
      (node (ref "IC4") (pin "14") (pinfunction "OUTR1_14") (pintype "bidirectional"))
    )
    (net (code "546") (name "unconnected-(IC4-OUTR2-Pad17)") (class "Default")
      (node (ref "IC4") (pin "17") (pinfunction "OUTR2_17") (pintype "bidirectional"))
    )
    (net (code "547") (name "unconnected-(IC4-OUTR3-Pad23)") (class "Default")
      (node (ref "IC4") (pin "23") (pinfunction "OUTR3_23") (pintype "bidirectional"))
    )
    (net (code "548") (name "unconnected-(IC4-OUTR4-Pad5)") (class "Default")
      (node (ref "IC4") (pin "5") (pinfunction "OUTR4_5") (pintype "bidirectional"))
    )
    (net (code "549") (name "unconnected-(IC4-OUTR5-Pad11)") (class "Default")
      (node (ref "IC4") (pin "11") (pinfunction "OUTR5_11") (pintype "bidirectional"))
    )
    (net (code "550") (name "unconnected-(IC4-OUTR6-Pad20)") (class "Default")
      (node (ref "IC4") (pin "20") (pinfunction "OUTR6_20") (pintype "bidirectional"))
    )
    (net (code "551") (name "unconnected-(IC4-OUTR7-Pad26)") (class "Default")
      (node (ref "IC4") (pin "26") (pinfunction "OUTR7_26") (pintype "bidirectional"))
    )
    (net (code "552") (name "unconnected-(IC4-OUTR8-Pad52)") (class "Default")
      (node (ref "IC4") (pin "52") (pinfunction "OUTR8_52") (pintype "bidirectional"))
    )
    (net (code "553") (name "unconnected-(IC4-OUTR9-Pad46)") (class "Default")
      (node (ref "IC4") (pin "46") (pinfunction "OUTR9_46") (pintype "bidirectional"))
    )
    (net (code "554") (name "unconnected-(IC4-OUTR10-Pad37)") (class "Default")
      (node (ref "IC4") (pin "37") (pinfunction "OUTR10_37") (pintype "bidirectional"))
    )
    (net (code "555") (name "unconnected-(IC4-OUTR11-Pad31)") (class "Default")
      (node (ref "IC4") (pin "31") (pinfunction "OUTR11_31") (pintype "bidirectional"))
    )
    (net (code "556") (name "unconnected-(IC4-OUTR12-Pad49)") (class "Default")
      (node (ref "IC4") (pin "49") (pinfunction "OUTR12_49") (pintype "bidirectional"))
    )
    (net (code "557") (name "unconnected-(IC4-OUTR13-Pad43)") (class "Default")
      (node (ref "IC4") (pin "43") (pinfunction "OUTR13_43") (pintype "bidirectional"))
    )
    (net (code "558") (name "unconnected-(IC4-OUTR14-Pad40)") (class "Default")
      (node (ref "IC4") (pin "40") (pinfunction "OUTR14_40") (pintype "bidirectional"))
    )
    (net (code "559") (name "unconnected-(IC4-OUTR15-Pad34)") (class "Default")
      (node (ref "IC4") (pin "34") (pinfunction "OUTR15_34") (pintype "bidirectional"))
    )
    (net (code "560") (name "unconnected-(IC5-OUTB0-Pad7)") (class "Default")
      (node (ref "IC5") (pin "7") (pinfunction "OUTB0_7") (pintype "bidirectional"))
    )
    (net (code "561") (name "unconnected-(IC5-OUTB1-Pad13)") (class "Default")
      (node (ref "IC5") (pin "13") (pinfunction "OUTB1_13") (pintype "bidirectional"))
    )
    (net (code "562") (name "unconnected-(IC5-OUTB2-Pad16)") (class "Default")
      (node (ref "IC5") (pin "16") (pinfunction "OUTB2_16") (pintype "bidirectional"))
    )
    (net (code "563") (name "unconnected-(IC5-OUTB3-Pad22)") (class "Default")
      (node (ref "IC5") (pin "22") (pinfunction "OUTB3_22") (pintype "bidirectional"))
    )
    (net (code "564") (name "unconnected-(IC5-OUTB4-Pad4)") (class "Default")
      (node (ref "IC5") (pin "4") (pinfunction "OUTB4_4") (pintype "bidirectional"))
    )
    (net (code "565") (name "unconnected-(IC5-OUTB5-Pad10)") (class "Default")
      (node (ref "IC5") (pin "10") (pinfunction "OUTB5_10") (pintype "bidirectional"))
    )
    (net (code "566") (name "unconnected-(IC5-OUTB6-Pad19)") (class "Default")
      (node (ref "IC5") (pin "19") (pinfunction "OUTB6_19") (pintype "bidirectional"))
    )
    (net (code "567") (name "unconnected-(IC5-OUTB7-Pad25)") (class "Default")
      (node (ref "IC5") (pin "25") (pinfunction "OUTB7_25") (pintype "bidirectional"))
    )
    (net (code "568") (name "unconnected-(IC5-OUTB8-Pad53)") (class "Default")
      (node (ref "IC5") (pin "53") (pinfunction "OUTB8_53") (pintype "bidirectional"))
    )
    (net (code "569") (name "unconnected-(IC5-OUTB9-Pad47)") (class "Default")
      (node (ref "IC5") (pin "47") (pinfunction "OUTB9_47") (pintype "bidirectional"))
    )
    (net (code "570") (name "unconnected-(IC5-OUTB10-Pad38)") (class "Default")
      (node (ref "IC5") (pin "38") (pinfunction "OUTB10_38") (pintype "bidirectional"))
    )
    (net (code "571") (name "unconnected-(IC5-OUTB11-Pad32)") (class "Default")
      (node (ref "IC5") (pin "32") (pinfunction "OUTB11_32") (pintype "bidirectional"))
    )
    (net (code "572") (name "unconnected-(IC5-OUTB12-Pad50)") (class "Default")
      (node (ref "IC5") (pin "50") (pinfunction "OUTB12_50") (pintype "bidirectional"))
    )
    (net (code "573") (name "unconnected-(IC5-OUTB13-Pad44)") (class "Default")
      (node (ref "IC5") (pin "44") (pinfunction "OUTB13_44") (pintype "bidirectional"))
    )
    (net (code "574") (name "unconnected-(IC5-OUTB14-Pad41)") (class "Default")
      (node (ref "IC5") (pin "41") (pinfunction "OUTB14_41") (pintype "bidirectional"))
    )
    (net (code "575") (name "unconnected-(IC5-OUTB15-Pad35)") (class "Default")
      (node (ref "IC5") (pin "35") (pinfunction "OUTB15_35") (pintype "bidirectional"))
    )
    (net (code "576") (name "unconnected-(IC5-OUTG0-Pad9)") (class "Default")
      (node (ref "IC5") (pin "9") (pinfunction "OUTG0_9") (pintype "bidirectional"))
    )
    (net (code "577") (name "unconnected-(IC5-OUTG1-Pad15)") (class "Default")
      (node (ref "IC5") (pin "15") (pinfunction "OUTG1_15") (pintype "bidirectional"))
    )
    (net (code "578") (name "unconnected-(IC5-OUTG2-Pad18)") (class "Default")
      (node (ref "IC5") (pin "18") (pinfunction "OUTG2_18") (pintype "bidirectional"))
    )
    (net (code "579") (name "unconnected-(IC5-OUTG3-Pad24)") (class "Default")
      (node (ref "IC5") (pin "24") (pinfunction "OUTG3_24") (pintype "bidirectional"))
    )
    (net (code "580") (name "unconnected-(IC5-OUTG4-Pad6)") (class "Default")
      (node (ref "IC5") (pin "6") (pinfunction "OUTG4_6") (pintype "bidirectional"))
    )
    (net (code "581") (name "unconnected-(IC5-OUTG5-Pad12)") (class "Default")
      (node (ref "IC5") (pin "12") (pinfunction "OUTG5_12") (pintype "bidirectional"))
    )
    (net (code "582") (name "unconnected-(IC5-OUTG6-Pad21)") (class "Default")
      (node (ref "IC5") (pin "21") (pinfunction "OUTG6_21") (pintype "bidirectional"))
    )
    (net (code "583") (name "unconnected-(IC5-OUTG7-Pad27)") (class "Default")
      (node (ref "IC5") (pin "27") (pinfunction "OUTG7_27") (pintype "bidirectional"))
    )
    (net (code "584") (name "unconnected-(IC5-OUTG8-Pad51)") (class "Default")
      (node (ref "IC5") (pin "51") (pinfunction "OUTG8_51") (pintype "bidirectional"))
    )
    (net (code "585") (name "unconnected-(IC5-OUTG9-Pad45)") (class "Default")
      (node (ref "IC5") (pin "45") (pinfunction "OUTG9_45") (pintype "bidirectional"))
    )
    (net (code "586") (name "unconnected-(IC5-OUTG10-Pad36)") (class "Default")
      (node (ref "IC5") (pin "36") (pinfunction "OUTG10_36") (pintype "bidirectional"))
    )
    (net (code "587") (name "unconnected-(IC5-OUTG11-Pad30)") (class "Default")
      (node (ref "IC5") (pin "30") (pinfunction "OUTG11_30") (pintype "bidirectional"))
    )
    (net (code "588") (name "unconnected-(IC5-OUTG12-Pad48)") (class "Default")
      (node (ref "IC5") (pin "48") (pinfunction "OUTG12_48") (pintype "bidirectional"))
    )
    (net (code "589") (name "unconnected-(IC5-OUTG13-Pad42)") (class "Default")
      (node (ref "IC5") (pin "42") (pinfunction "OUTG13_42") (pintype "bidirectional"))
    )
    (net (code "590") (name "unconnected-(IC5-OUTG14-Pad39)") (class "Default")
      (node (ref "IC5") (pin "39") (pinfunction "OUTG14_39") (pintype "bidirectional"))
    )
    (net (code "591") (name "unconnected-(IC5-OUTG15-Pad33)") (class "Default")
      (node (ref "IC5") (pin "33") (pinfunction "OUTG15_33") (pintype "bidirectional"))
    )
    (net (code "592") (name "unconnected-(IC5-OUTR0-Pad8)") (class "Default")
      (node (ref "IC5") (pin "8") (pinfunction "OUTR0_8") (pintype "bidirectional"))
    )
    (net (code "593") (name "unconnected-(IC5-OUTR1-Pad14)") (class "Default")
      (node (ref "IC5") (pin "14") (pinfunction "OUTR1_14") (pintype "bidirectional"))
    )
    (net (code "594") (name "unconnected-(IC5-OUTR2-Pad17)") (class "Default")
      (node (ref "IC5") (pin "17") (pinfunction "OUTR2_17") (pintype "bidirectional"))
    )
    (net (code "595") (name "unconnected-(IC5-OUTR3-Pad23)") (class "Default")
      (node (ref "IC5") (pin "23") (pinfunction "OUTR3_23") (pintype "bidirectional"))
    )
    (net (code "596") (name "unconnected-(IC5-OUTR4-Pad5)") (class "Default")
      (node (ref "IC5") (pin "5") (pinfunction "OUTR4_5") (pintype "bidirectional"))
    )
    (net (code "597") (name "unconnected-(IC5-OUTR5-Pad11)") (class "Default")
      (node (ref "IC5") (pin "11") (pinfunction "OUTR5_11") (pintype "bidirectional"))
    )
    (net (code "598") (name "unconnected-(IC5-OUTR6-Pad20)") (class "Default")
      (node (ref "IC5") (pin "20") (pinfunction "OUTR6_20") (pintype "bidirectional"))
    )
    (net (code "599") (name "unconnected-(IC5-OUTR7-Pad26)") (class "Default")
      (node (ref "IC5") (pin "26") (pinfunction "OUTR7_26") (pintype "bidirectional"))
    )
    (net (code "600") (name "unconnected-(IC5-OUTR8-Pad52)") (class "Default")
      (node (ref "IC5") (pin "52") (pinfunction "OUTR8_52") (pintype "bidirectional"))
    )
    (net (code "601") (name "unconnected-(IC5-OUTR9-Pad46)") (class "Default")
      (node (ref "IC5") (pin "46") (pinfunction "OUTR9_46") (pintype "bidirectional"))
    )
    (net (code "602") (name "unconnected-(IC5-OUTR10-Pad37)") (class "Default")
      (node (ref "IC5") (pin "37") (pinfunction "OUTR10_37") (pintype "bidirectional"))
    )
    (net (code "603") (name "unconnected-(IC5-OUTR11-Pad31)") (class "Default")
      (node (ref "IC5") (pin "31") (pinfunction "OUTR11_31") (pintype "bidirectional"))
    )
    (net (code "604") (name "unconnected-(IC5-OUTR12-Pad49)") (class "Default")
      (node (ref "IC5") (pin "49") (pinfunction "OUTR12_49") (pintype "bidirectional"))
    )
    (net (code "605") (name "unconnected-(IC5-OUTR13-Pad43)") (class "Default")
      (node (ref "IC5") (pin "43") (pinfunction "OUTR13_43") (pintype "bidirectional"))
    )
    (net (code "606") (name "unconnected-(IC5-OUTR14-Pad40)") (class "Default")
      (node (ref "IC5") (pin "40") (pinfunction "OUTR14_40") (pintype "bidirectional"))
    )
    (net (code "607") (name "unconnected-(IC5-OUTR15-Pad34)") (class "Default")
      (node (ref "IC5") (pin "34") (pinfunction "OUTR15_34") (pintype "bidirectional"))
    )
    (net (code "608") (name "unconnected-(IC6-OUTB0-Pad7)") (class "Default")
      (node (ref "IC6") (pin "7") (pinfunction "OUTB0_7") (pintype "bidirectional"))
    )
    (net (code "609") (name "unconnected-(IC6-OUTB1-Pad13)") (class "Default")
      (node (ref "IC6") (pin "13") (pinfunction "OUTB1_13") (pintype "bidirectional"))
    )
    (net (code "610") (name "unconnected-(IC6-OUTB2-Pad16)") (class "Default")
      (node (ref "IC6") (pin "16") (pinfunction "OUTB2_16") (pintype "bidirectional"))
    )
    (net (code "611") (name "unconnected-(IC6-OUTB3-Pad22)") (class "Default")
      (node (ref "IC6") (pin "22") (pinfunction "OUTB3_22") (pintype "bidirectional"))
    )
    (net (code "612") (name "unconnected-(IC6-OUTB4-Pad4)") (class "Default")
      (node (ref "IC6") (pin "4") (pinfunction "OUTB4_4") (pintype "bidirectional"))
    )
    (net (code "613") (name "unconnected-(IC6-OUTB5-Pad10)") (class "Default")
      (node (ref "IC6") (pin "10") (pinfunction "OUTB5_10") (pintype "bidirectional"))
    )
    (net (code "614") (name "unconnected-(IC6-OUTB6-Pad19)") (class "Default")
      (node (ref "IC6") (pin "19") (pinfunction "OUTB6_19") (pintype "bidirectional"))
    )
    (net (code "615") (name "unconnected-(IC6-OUTB7-Pad25)") (class "Default")
      (node (ref "IC6") (pin "25") (pinfunction "OUTB7_25") (pintype "bidirectional"))
    )
    (net (code "616") (name "unconnected-(IC6-OUTB8-Pad53)") (class "Default")
      (node (ref "IC6") (pin "53") (pinfunction "OUTB8_53") (pintype "bidirectional"))
    )
    (net (code "617") (name "unconnected-(IC6-OUTB9-Pad47)") (class "Default")
      (node (ref "IC6") (pin "47") (pinfunction "OUTB9_47") (pintype "bidirectional"))
    )
    (net (code "618") (name "unconnected-(IC6-OUTB10-Pad38)") (class "Default")
      (node (ref "IC6") (pin "38") (pinfunction "OUTB10_38") (pintype "bidirectional"))
    )
    (net (code "619") (name "unconnected-(IC6-OUTB11-Pad32)") (class "Default")
      (node (ref "IC6") (pin "32") (pinfunction "OUTB11_32") (pintype "bidirectional"))
    )
    (net (code "620") (name "unconnected-(IC6-OUTB12-Pad50)") (class "Default")
      (node (ref "IC6") (pin "50") (pinfunction "OUTB12_50") (pintype "bidirectional"))
    )
    (net (code "621") (name "unconnected-(IC6-OUTB13-Pad44)") (class "Default")
      (node (ref "IC6") (pin "44") (pinfunction "OUTB13_44") (pintype "bidirectional"))
    )
    (net (code "622") (name "unconnected-(IC6-OUTB14-Pad41)") (class "Default")
      (node (ref "IC6") (pin "41") (pinfunction "OUTB14_41") (pintype "bidirectional"))
    )
    (net (code "623") (name "unconnected-(IC6-OUTB15-Pad35)") (class "Default")
      (node (ref "IC6") (pin "35") (pinfunction "OUTB15_35") (pintype "bidirectional"))
    )
    (net (code "624") (name "unconnected-(IC6-OUTG0-Pad9)") (class "Default")
      (node (ref "IC6") (pin "9") (pinfunction "OUTG0_9") (pintype "bidirectional"))
    )
    (net (code "625") (name "unconnected-(IC6-OUTG1-Pad15)") (class "Default")
      (node (ref "IC6") (pin "15") (pinfunction "OUTG1_15") (pintype "bidirectional"))
    )
    (net (code "626") (name "unconnected-(IC6-OUTG2-Pad18)") (class "Default")
      (node (ref "IC6") (pin "18") (pinfunction "OUTG2_18") (pintype "bidirectional"))
    )
    (net (code "627") (name "unconnected-(IC6-OUTG3-Pad24)") (class "Default")
      (node (ref "IC6") (pin "24") (pinfunction "OUTG3_24") (pintype "bidirectional"))
    )
    (net (code "628") (name "unconnected-(IC6-OUTG4-Pad6)") (class "Default")
      (node (ref "IC6") (pin "6") (pinfunction "OUTG4_6") (pintype "bidirectional"))
    )
    (net (code "629") (name "unconnected-(IC6-OUTG5-Pad12)") (class "Default")
      (node (ref "IC6") (pin "12") (pinfunction "OUTG5_12") (pintype "bidirectional"))
    )
    (net (code "630") (name "unconnected-(IC6-OUTG6-Pad21)") (class "Default")
      (node (ref "IC6") (pin "21") (pinfunction "OUTG6_21") (pintype "bidirectional"))
    )
    (net (code "631") (name "unconnected-(IC6-OUTG7-Pad27)") (class "Default")
      (node (ref "IC6") (pin "27") (pinfunction "OUTG7_27") (pintype "bidirectional"))
    )
    (net (code "632") (name "unconnected-(IC6-OUTG8-Pad51)") (class "Default")
      (node (ref "IC6") (pin "51") (pinfunction "OUTG8_51") (pintype "bidirectional"))
    )
    (net (code "633") (name "unconnected-(IC6-OUTG9-Pad45)") (class "Default")
      (node (ref "IC6") (pin "45") (pinfunction "OUTG9_45") (pintype "bidirectional"))
    )
    (net (code "634") (name "unconnected-(IC6-OUTG10-Pad36)") (class "Default")
      (node (ref "IC6") (pin "36") (pinfunction "OUTG10_36") (pintype "bidirectional"))
    )
    (net (code "635") (name "unconnected-(IC6-OUTG11-Pad30)") (class "Default")
      (node (ref "IC6") (pin "30") (pinfunction "OUTG11_30") (pintype "bidirectional"))
    )
    (net (code "636") (name "unconnected-(IC6-OUTG12-Pad48)") (class "Default")
      (node (ref "IC6") (pin "48") (pinfunction "OUTG12_48") (pintype "bidirectional"))
    )
    (net (code "637") (name "unconnected-(IC6-OUTG13-Pad42)") (class "Default")
      (node (ref "IC6") (pin "42") (pinfunction "OUTG13_42") (pintype "bidirectional"))
    )
    (net (code "638") (name "unconnected-(IC6-OUTG14-Pad39)") (class "Default")
      (node (ref "IC6") (pin "39") (pinfunction "OUTG14_39") (pintype "bidirectional"))
    )
    (net (code "639") (name "unconnected-(IC6-OUTG15-Pad33)") (class "Default")
      (node (ref "IC6") (pin "33") (pinfunction "OUTG15_33") (pintype "bidirectional"))
    )
    (net (code "640") (name "unconnected-(IC6-OUTR0-Pad8)") (class "Default")
      (node (ref "IC6") (pin "8") (pinfunction "OUTR0_8") (pintype "bidirectional"))
    )
    (net (code "641") (name "unconnected-(IC6-OUTR1-Pad14)") (class "Default")
      (node (ref "IC6") (pin "14") (pinfunction "OUTR1_14") (pintype "bidirectional"))
    )
    (net (code "642") (name "unconnected-(IC6-OUTR2-Pad17)") (class "Default")
      (node (ref "IC6") (pin "17") (pinfunction "OUTR2_17") (pintype "bidirectional"))
    )
    (net (code "643") (name "unconnected-(IC6-OUTR3-Pad23)") (class "Default")
      (node (ref "IC6") (pin "23") (pinfunction "OUTR3_23") (pintype "bidirectional"))
    )
    (net (code "644") (name "unconnected-(IC6-OUTR4-Pad5)") (class "Default")
      (node (ref "IC6") (pin "5") (pinfunction "OUTR4_5") (pintype "bidirectional"))
    )
    (net (code "645") (name "unconnected-(IC6-OUTR5-Pad11)") (class "Default")
      (node (ref "IC6") (pin "11") (pinfunction "OUTR5_11") (pintype "bidirectional"))
    )
    (net (code "646") (name "unconnected-(IC6-OUTR6-Pad20)") (class "Default")
      (node (ref "IC6") (pin "20") (pinfunction "OUTR6_20") (pintype "bidirectional"))
    )
    (net (code "647") (name "unconnected-(IC6-OUTR7-Pad26)") (class "Default")
      (node (ref "IC6") (pin "26") (pinfunction "OUTR7_26") (pintype "bidirectional"))
    )
    (net (code "648") (name "unconnected-(IC6-OUTR8-Pad52)") (class "Default")
      (node (ref "IC6") (pin "52") (pinfunction "OUTR8_52") (pintype "bidirectional"))
    )
    (net (code "649") (name "unconnected-(IC6-OUTR9-Pad46)") (class "Default")
      (node (ref "IC6") (pin "46") (pinfunction "OUTR9_46") (pintype "bidirectional"))
    )
    (net (code "650") (name "unconnected-(IC6-OUTR10-Pad37)") (class "Default")
      (node (ref "IC6") (pin "37") (pinfunction "OUTR10_37") (pintype "bidirectional"))
    )
    (net (code "651") (name "unconnected-(IC6-OUTR11-Pad31)") (class "Default")
      (node (ref "IC6") (pin "31") (pinfunction "OUTR11_31") (pintype "bidirectional"))
    )
    (net (code "652") (name "unconnected-(IC6-OUTR12-Pad49)") (class "Default")
      (node (ref "IC6") (pin "49") (pinfunction "OUTR12_49") (pintype "bidirectional"))
    )
    (net (code "653") (name "unconnected-(IC6-OUTR13-Pad43)") (class "Default")
      (node (ref "IC6") (pin "43") (pinfunction "OUTR13_43") (pintype "bidirectional"))
    )
    (net (code "654") (name "unconnected-(IC6-OUTR14-Pad40)") (class "Default")
      (node (ref "IC6") (pin "40") (pinfunction "OUTR14_40") (pintype "bidirectional"))
    )
    (net (code "655") (name "unconnected-(IC6-OUTR15-Pad34)") (class "Default")
      (node (ref "IC6") (pin "34") (pinfunction "OUTR15_34") (pintype "bidirectional"))
    )
    (net (code "656") (name "unconnected-(IC7-OUTB0-Pad7)") (class "Default")
      (node (ref "IC7") (pin "7") (pinfunction "OUTB0_7") (pintype "bidirectional"))
    )
    (net (code "657") (name "unconnected-(IC7-OUTB1-Pad13)") (class "Default")
      (node (ref "IC7") (pin "13") (pinfunction "OUTB1_13") (pintype "bidirectional"))
    )
    (net (code "658") (name "unconnected-(IC7-OUTB2-Pad16)") (class "Default")
      (node (ref "IC7") (pin "16") (pinfunction "OUTB2_16") (pintype "bidirectional"))
    )
    (net (code "659") (name "unconnected-(IC7-OUTB3-Pad22)") (class "Default")
      (node (ref "IC7") (pin "22") (pinfunction "OUTB3_22") (pintype "bidirectional"))
    )
    (net (code "660") (name "unconnected-(IC7-OUTB4-Pad4)") (class "Default")
      (node (ref "IC7") (pin "4") (pinfunction "OUTB4_4") (pintype "bidirectional"))
    )
    (net (code "661") (name "unconnected-(IC7-OUTB5-Pad10)") (class "Default")
      (node (ref "IC7") (pin "10") (pinfunction "OUTB5_10") (pintype "bidirectional"))
    )
    (net (code "662") (name "unconnected-(IC7-OUTB6-Pad19)") (class "Default")
      (node (ref "IC7") (pin "19") (pinfunction "OUTB6_19") (pintype "bidirectional"))
    )
    (net (code "663") (name "unconnected-(IC7-OUTB7-Pad25)") (class "Default")
      (node (ref "IC7") (pin "25") (pinfunction "OUTB7_25") (pintype "bidirectional"))
    )
    (net (code "664") (name "unconnected-(IC7-OUTB8-Pad53)") (class "Default")
      (node (ref "IC7") (pin "53") (pinfunction "OUTB8_53") (pintype "bidirectional"))
    )
    (net (code "665") (name "unconnected-(IC7-OUTB9-Pad47)") (class "Default")
      (node (ref "IC7") (pin "47") (pinfunction "OUTB9_47") (pintype "bidirectional"))
    )
    (net (code "666") (name "unconnected-(IC7-OUTB10-Pad38)") (class "Default")
      (node (ref "IC7") (pin "38") (pinfunction "OUTB10_38") (pintype "bidirectional"))
    )
    (net (code "667") (name "unconnected-(IC7-OUTB11-Pad32)") (class "Default")
      (node (ref "IC7") (pin "32") (pinfunction "OUTB11_32") (pintype "bidirectional"))
    )
    (net (code "668") (name "unconnected-(IC7-OUTB12-Pad50)") (class "Default")
      (node (ref "IC7") (pin "50") (pinfunction "OUTB12_50") (pintype "bidirectional"))
    )
    (net (code "669") (name "unconnected-(IC7-OUTB13-Pad44)") (class "Default")
      (node (ref "IC7") (pin "44") (pinfunction "OUTB13_44") (pintype "bidirectional"))
    )
    (net (code "670") (name "unconnected-(IC7-OUTB14-Pad41)") (class "Default")
      (node (ref "IC7") (pin "41") (pinfunction "OUTB14_41") (pintype "bidirectional"))
    )
    (net (code "671") (name "unconnected-(IC7-OUTB15-Pad35)") (class "Default")
      (node (ref "IC7") (pin "35") (pinfunction "OUTB15_35") (pintype "bidirectional"))
    )
    (net (code "672") (name "unconnected-(IC7-OUTG0-Pad9)") (class "Default")
      (node (ref "IC7") (pin "9") (pinfunction "OUTG0_9") (pintype "bidirectional"))
    )
    (net (code "673") (name "unconnected-(IC7-OUTG1-Pad15)") (class "Default")
      (node (ref "IC7") (pin "15") (pinfunction "OUTG1_15") (pintype "bidirectional"))
    )
    (net (code "674") (name "unconnected-(IC7-OUTG2-Pad18)") (class "Default")
      (node (ref "IC7") (pin "18") (pinfunction "OUTG2_18") (pintype "bidirectional"))
    )
    (net (code "675") (name "unconnected-(IC7-OUTG3-Pad24)") (class "Default")
      (node (ref "IC7") (pin "24") (pinfunction "OUTG3_24") (pintype "bidirectional"))
    )
    (net (code "676") (name "unconnected-(IC7-OUTG4-Pad6)") (class "Default")
      (node (ref "IC7") (pin "6") (pinfunction "OUTG4_6") (pintype "bidirectional"))
    )
    (net (code "677") (name "unconnected-(IC7-OUTG5-Pad12)") (class "Default")
      (node (ref "IC7") (pin "12") (pinfunction "OUTG5_12") (pintype "bidirectional"))
    )
    (net (code "678") (name "unconnected-(IC7-OUTG6-Pad21)") (class "Default")
      (node (ref "IC7") (pin "21") (pinfunction "OUTG6_21") (pintype "bidirectional"))
    )
    (net (code "679") (name "unconnected-(IC7-OUTG7-Pad27)") (class "Default")
      (node (ref "IC7") (pin "27") (pinfunction "OUTG7_27") (pintype "bidirectional"))
    )
    (net (code "680") (name "unconnected-(IC7-OUTG8-Pad51)") (class "Default")
      (node (ref "IC7") (pin "51") (pinfunction "OUTG8_51") (pintype "bidirectional"))
    )
    (net (code "681") (name "unconnected-(IC7-OUTG9-Pad45)") (class "Default")
      (node (ref "IC7") (pin "45") (pinfunction "OUTG9_45") (pintype "bidirectional"))
    )
    (net (code "682") (name "unconnected-(IC7-OUTG10-Pad36)") (class "Default")
      (node (ref "IC7") (pin "36") (pinfunction "OUTG10_36") (pintype "bidirectional"))
    )
    (net (code "683") (name "unconnected-(IC7-OUTG11-Pad30)") (class "Default")
      (node (ref "IC7") (pin "30") (pinfunction "OUTG11_30") (pintype "bidirectional"))
    )
    (net (code "684") (name "unconnected-(IC7-OUTG12-Pad48)") (class "Default")
      (node (ref "IC7") (pin "48") (pinfunction "OUTG12_48") (pintype "bidirectional"))
    )
    (net (code "685") (name "unconnected-(IC7-OUTG13-Pad42)") (class "Default")
      (node (ref "IC7") (pin "42") (pinfunction "OUTG13_42") (pintype "bidirectional"))
    )
    (net (code "686") (name "unconnected-(IC7-OUTG14-Pad39)") (class "Default")
      (node (ref "IC7") (pin "39") (pinfunction "OUTG14_39") (pintype "bidirectional"))
    )
    (net (code "687") (name "unconnected-(IC7-OUTG15-Pad33)") (class "Default")
      (node (ref "IC7") (pin "33") (pinfunction "OUTG15_33") (pintype "bidirectional"))
    )
    (net (code "688") (name "unconnected-(IC7-OUTR0-Pad8)") (class "Default")
      (node (ref "IC7") (pin "8") (pinfunction "OUTR0_8") (pintype "bidirectional"))
    )
    (net (code "689") (name "unconnected-(IC7-OUTR1-Pad14)") (class "Default")
      (node (ref "IC7") (pin "14") (pinfunction "OUTR1_14") (pintype "bidirectional"))
    )
    (net (code "690") (name "unconnected-(IC7-OUTR2-Pad17)") (class "Default")
      (node (ref "IC7") (pin "17") (pinfunction "OUTR2_17") (pintype "bidirectional"))
    )
    (net (code "691") (name "unconnected-(IC7-OUTR3-Pad23)") (class "Default")
      (node (ref "IC7") (pin "23") (pinfunction "OUTR3_23") (pintype "bidirectional"))
    )
    (net (code "692") (name "unconnected-(IC7-OUTR4-Pad5)") (class "Default")
      (node (ref "IC7") (pin "5") (pinfunction "OUTR4_5") (pintype "bidirectional"))
    )
    (net (code "693") (name "unconnected-(IC7-OUTR5-Pad11)") (class "Default")
      (node (ref "IC7") (pin "11") (pinfunction "OUTR5_11") (pintype "bidirectional"))
    )
    (net (code "694") (name "unconnected-(IC7-OUTR6-Pad20)") (class "Default")
      (node (ref "IC7") (pin "20") (pinfunction "OUTR6_20") (pintype "bidirectional"))
    )
    (net (code "695") (name "unconnected-(IC7-OUTR7-Pad26)") (class "Default")
      (node (ref "IC7") (pin "26") (pinfunction "OUTR7_26") (pintype "bidirectional"))
    )
    (net (code "696") (name "unconnected-(IC7-OUTR8-Pad52)") (class "Default")
      (node (ref "IC7") (pin "52") (pinfunction "OUTR8_52") (pintype "bidirectional"))
    )
    (net (code "697") (name "unconnected-(IC7-OUTR9-Pad46)") (class "Default")
      (node (ref "IC7") (pin "46") (pinfunction "OUTR9_46") (pintype "bidirectional"))
    )
    (net (code "698") (name "unconnected-(IC7-OUTR10-Pad37)") (class "Default")
      (node (ref "IC7") (pin "37") (pinfunction "OUTR10_37") (pintype "bidirectional"))
    )
    (net (code "699") (name "unconnected-(IC7-OUTR11-Pad31)") (class "Default")
      (node (ref "IC7") (pin "31") (pinfunction "OUTR11_31") (pintype "bidirectional"))
    )
    (net (code "700") (name "unconnected-(IC7-OUTR12-Pad49)") (class "Default")
      (node (ref "IC7") (pin "49") (pinfunction "OUTR12_49") (pintype "bidirectional"))
    )
    (net (code "701") (name "unconnected-(IC7-OUTR13-Pad43)") (class "Default")
      (node (ref "IC7") (pin "43") (pinfunction "OUTR13_43") (pintype "bidirectional"))
    )
    (net (code "702") (name "unconnected-(IC7-OUTR14-Pad40)") (class "Default")
      (node (ref "IC7") (pin "40") (pinfunction "OUTR14_40") (pintype "bidirectional"))
    )
    (net (code "703") (name "unconnected-(IC7-OUTR15-Pad34)") (class "Default")
      (node (ref "IC7") (pin "34") (pinfunction "OUTR15_34") (pintype "bidirectional"))
    )
    (net (code "704") (name "unconnected-(IC8-OUTB0-Pad7)") (class "Default")
      (node (ref "IC8") (pin "7") (pinfunction "OUTB0_7") (pintype "bidirectional"))
    )
    (net (code "705") (name "unconnected-(IC8-OUTB1-Pad13)") (class "Default")
      (node (ref "IC8") (pin "13") (pinfunction "OUTB1_13") (pintype "bidirectional"))
    )
    (net (code "706") (name "unconnected-(IC8-OUTB2-Pad16)") (class "Default")
      (node (ref "IC8") (pin "16") (pinfunction "OUTB2_16") (pintype "bidirectional"))
    )
    (net (code "707") (name "unconnected-(IC8-OUTB3-Pad22)") (class "Default")
      (node (ref "IC8") (pin "22") (pinfunction "OUTB3_22") (pintype "bidirectional"))
    )
    (net (code "708") (name "unconnected-(IC8-OUTB4-Pad4)") (class "Default")
      (node (ref "IC8") (pin "4") (pinfunction "OUTB4_4") (pintype "bidirectional"))
    )
    (net (code "709") (name "unconnected-(IC8-OUTB5-Pad10)") (class "Default")
      (node (ref "IC8") (pin "10") (pinfunction "OUTB5_10") (pintype "bidirectional"))
    )
    (net (code "710") (name "unconnected-(IC8-OUTB6-Pad19)") (class "Default")
      (node (ref "IC8") (pin "19") (pinfunction "OUTB6_19") (pintype "bidirectional"))
    )
    (net (code "711") (name "unconnected-(IC8-OUTB7-Pad25)") (class "Default")
      (node (ref "IC8") (pin "25") (pinfunction "OUTB7_25") (pintype "bidirectional"))
    )
    (net (code "712") (name "unconnected-(IC8-OUTB8-Pad53)") (class "Default")
      (node (ref "IC8") (pin "53") (pinfunction "OUTB8_53") (pintype "bidirectional"))
    )
    (net (code "713") (name "unconnected-(IC8-OUTB9-Pad47)") (class "Default")
      (node (ref "IC8") (pin "47") (pinfunction "OUTB9_47") (pintype "bidirectional"))
    )
    (net (code "714") (name "unconnected-(IC8-OUTB10-Pad38)") (class "Default")
      (node (ref "IC8") (pin "38") (pinfunction "OUTB10_38") (pintype "bidirectional"))
    )
    (net (code "715") (name "unconnected-(IC8-OUTB11-Pad32)") (class "Default")
      (node (ref "IC8") (pin "32") (pinfunction "OUTB11_32") (pintype "bidirectional"))
    )
    (net (code "716") (name "unconnected-(IC8-OUTB12-Pad50)") (class "Default")
      (node (ref "IC8") (pin "50") (pinfunction "OUTB12_50") (pintype "bidirectional"))
    )
    (net (code "717") (name "unconnected-(IC8-OUTB13-Pad44)") (class "Default")
      (node (ref "IC8") (pin "44") (pinfunction "OUTB13_44") (pintype "bidirectional"))
    )
    (net (code "718") (name "unconnected-(IC8-OUTB14-Pad41)") (class "Default")
      (node (ref "IC8") (pin "41") (pinfunction "OUTB14_41") (pintype "bidirectional"))
    )
    (net (code "719") (name "unconnected-(IC8-OUTB15-Pad35)") (class "Default")
      (node (ref "IC8") (pin "35") (pinfunction "OUTB15_35") (pintype "bidirectional"))
    )
    (net (code "720") (name "unconnected-(IC8-OUTG0-Pad9)") (class "Default")
      (node (ref "IC8") (pin "9") (pinfunction "OUTG0_9") (pintype "bidirectional"))
    )
    (net (code "721") (name "unconnected-(IC8-OUTG1-Pad15)") (class "Default")
      (node (ref "IC8") (pin "15") (pinfunction "OUTG1_15") (pintype "bidirectional"))
    )
    (net (code "722") (name "unconnected-(IC8-OUTG2-Pad18)") (class "Default")
      (node (ref "IC8") (pin "18") (pinfunction "OUTG2_18") (pintype "bidirectional"))
    )
    (net (code "723") (name "unconnected-(IC8-OUTG3-Pad24)") (class "Default")
      (node (ref "IC8") (pin "24") (pinfunction "OUTG3_24") (pintype "bidirectional"))
    )
    (net (code "724") (name "unconnected-(IC8-OUTG4-Pad6)") (class "Default")
      (node (ref "IC8") (pin "6") (pinfunction "OUTG4_6") (pintype "bidirectional"))
    )
    (net (code "725") (name "unconnected-(IC8-OUTG5-Pad12)") (class "Default")
      (node (ref "IC8") (pin "12") (pinfunction "OUTG5_12") (pintype "bidirectional"))
    )
    (net (code "726") (name "unconnected-(IC8-OUTG6-Pad21)") (class "Default")
      (node (ref "IC8") (pin "21") (pinfunction "OUTG6_21") (pintype "bidirectional"))
    )
    (net (code "727") (name "unconnected-(IC8-OUTG7-Pad27)") (class "Default")
      (node (ref "IC8") (pin "27") (pinfunction "OUTG7_27") (pintype "bidirectional"))
    )
    (net (code "728") (name "unconnected-(IC8-OUTG8-Pad51)") (class "Default")
      (node (ref "IC8") (pin "51") (pinfunction "OUTG8_51") (pintype "bidirectional"))
    )
    (net (code "729") (name "unconnected-(IC8-OUTG9-Pad45)") (class "Default")
      (node (ref "IC8") (pin "45") (pinfunction "OUTG9_45") (pintype "bidirectional"))
    )
    (net (code "730") (name "unconnected-(IC8-OUTG10-Pad36)") (class "Default")
      (node (ref "IC8") (pin "36") (pinfunction "OUTG10_36") (pintype "bidirectional"))
    )
    (net (code "731") (name "unconnected-(IC8-OUTG11-Pad30)") (class "Default")
      (node (ref "IC8") (pin "30") (pinfunction "OUTG11_30") (pintype "bidirectional"))
    )
    (net (code "732") (name "unconnected-(IC8-OUTG12-Pad48)") (class "Default")
      (node (ref "IC8") (pin "48") (pinfunction "OUTG12_48") (pintype "bidirectional"))
    )
    (net (code "733") (name "unconnected-(IC8-OUTG13-Pad42)") (class "Default")
      (node (ref "IC8") (pin "42") (pinfunction "OUTG13_42") (pintype "bidirectional"))
    )
    (net (code "734") (name "unconnected-(IC8-OUTG14-Pad39)") (class "Default")
      (node (ref "IC8") (pin "39") (pinfunction "OUTG14_39") (pintype "bidirectional"))
    )
    (net (code "735") (name "unconnected-(IC8-OUTG15-Pad33)") (class "Default")
      (node (ref "IC8") (pin "33") (pinfunction "OUTG15_33") (pintype "bidirectional"))
    )
    (net (code "736") (name "unconnected-(IC8-OUTR0-Pad8)") (class "Default")
      (node (ref "IC8") (pin "8") (pinfunction "OUTR0_8") (pintype "bidirectional"))
    )
    (net (code "737") (name "unconnected-(IC8-OUTR1-Pad14)") (class "Default")
      (node (ref "IC8") (pin "14") (pinfunction "OUTR1_14") (pintype "bidirectional"))
    )
    (net (code "738") (name "unconnected-(IC8-OUTR2-Pad17)") (class "Default")
      (node (ref "IC8") (pin "17") (pinfunction "OUTR2_17") (pintype "bidirectional"))
    )
    (net (code "739") (name "unconnected-(IC8-OUTR3-Pad23)") (class "Default")
      (node (ref "IC8") (pin "23") (pinfunction "OUTR3_23") (pintype "bidirectional"))
    )
    (net (code "740") (name "unconnected-(IC8-OUTR4-Pad5)") (class "Default")
      (node (ref "IC8") (pin "5") (pinfunction "OUTR4_5") (pintype "bidirectional"))
    )
    (net (code "741") (name "unconnected-(IC8-OUTR5-Pad11)") (class "Default")
      (node (ref "IC8") (pin "11") (pinfunction "OUTR5_11") (pintype "bidirectional"))
    )
    (net (code "742") (name "unconnected-(IC8-OUTR6-Pad20)") (class "Default")
      (node (ref "IC8") (pin "20") (pinfunction "OUTR6_20") (pintype "bidirectional"))
    )
    (net (code "743") (name "unconnected-(IC8-OUTR7-Pad26)") (class "Default")
      (node (ref "IC8") (pin "26") (pinfunction "OUTR7_26") (pintype "bidirectional"))
    )
    (net (code "744") (name "unconnected-(IC8-OUTR8-Pad52)") (class "Default")
      (node (ref "IC8") (pin "52") (pinfunction "OUTR8_52") (pintype "bidirectional"))
    )
    (net (code "745") (name "unconnected-(IC8-OUTR9-Pad46)") (class "Default")
      (node (ref "IC8") (pin "46") (pinfunction "OUTR9_46") (pintype "bidirectional"))
    )
    (net (code "746") (name "unconnected-(IC8-OUTR10-Pad37)") (class "Default")
      (node (ref "IC8") (pin "37") (pinfunction "OUTR10_37") (pintype "bidirectional"))
    )
    (net (code "747") (name "unconnected-(IC8-OUTR11-Pad31)") (class "Default")
      (node (ref "IC8") (pin "31") (pinfunction "OUTR11_31") (pintype "bidirectional"))
    )
    (net (code "748") (name "unconnected-(IC8-OUTR12-Pad49)") (class "Default")
      (node (ref "IC8") (pin "49") (pinfunction "OUTR12_49") (pintype "bidirectional"))
    )
    (net (code "749") (name "unconnected-(IC8-OUTR13-Pad43)") (class "Default")
      (node (ref "IC8") (pin "43") (pinfunction "OUTR13_43") (pintype "bidirectional"))
    )
    (net (code "750") (name "unconnected-(IC8-OUTR14-Pad40)") (class "Default")
      (node (ref "IC8") (pin "40") (pinfunction "OUTR14_40") (pintype "bidirectional"))
    )
    (net (code "751") (name "unconnected-(IC8-OUTR15-Pad34)") (class "Default")
      (node (ref "IC8") (pin "34") (pinfunction "OUTR15_34") (pintype "bidirectional"))
    )
  )
)
